# Server_CPU_DDR4.net
KiCad netlist of a schematic drawn in Altium Designer
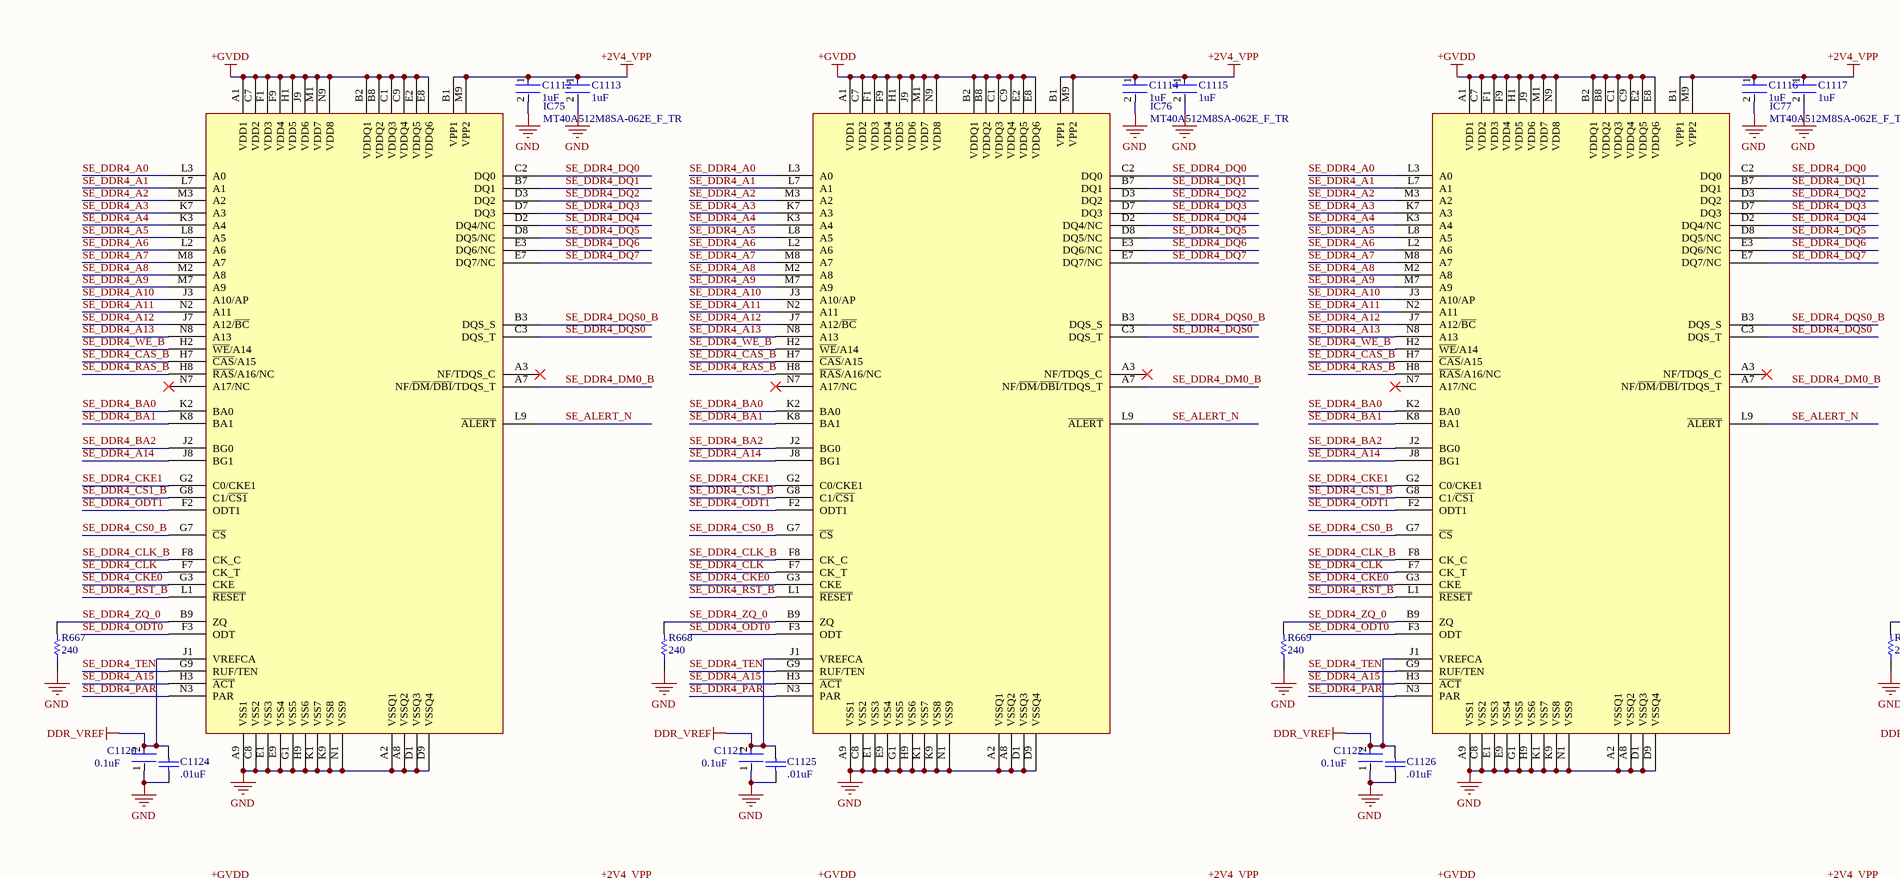
[diagram p0: Server_CPU_DDR4.SchDoc, top left]
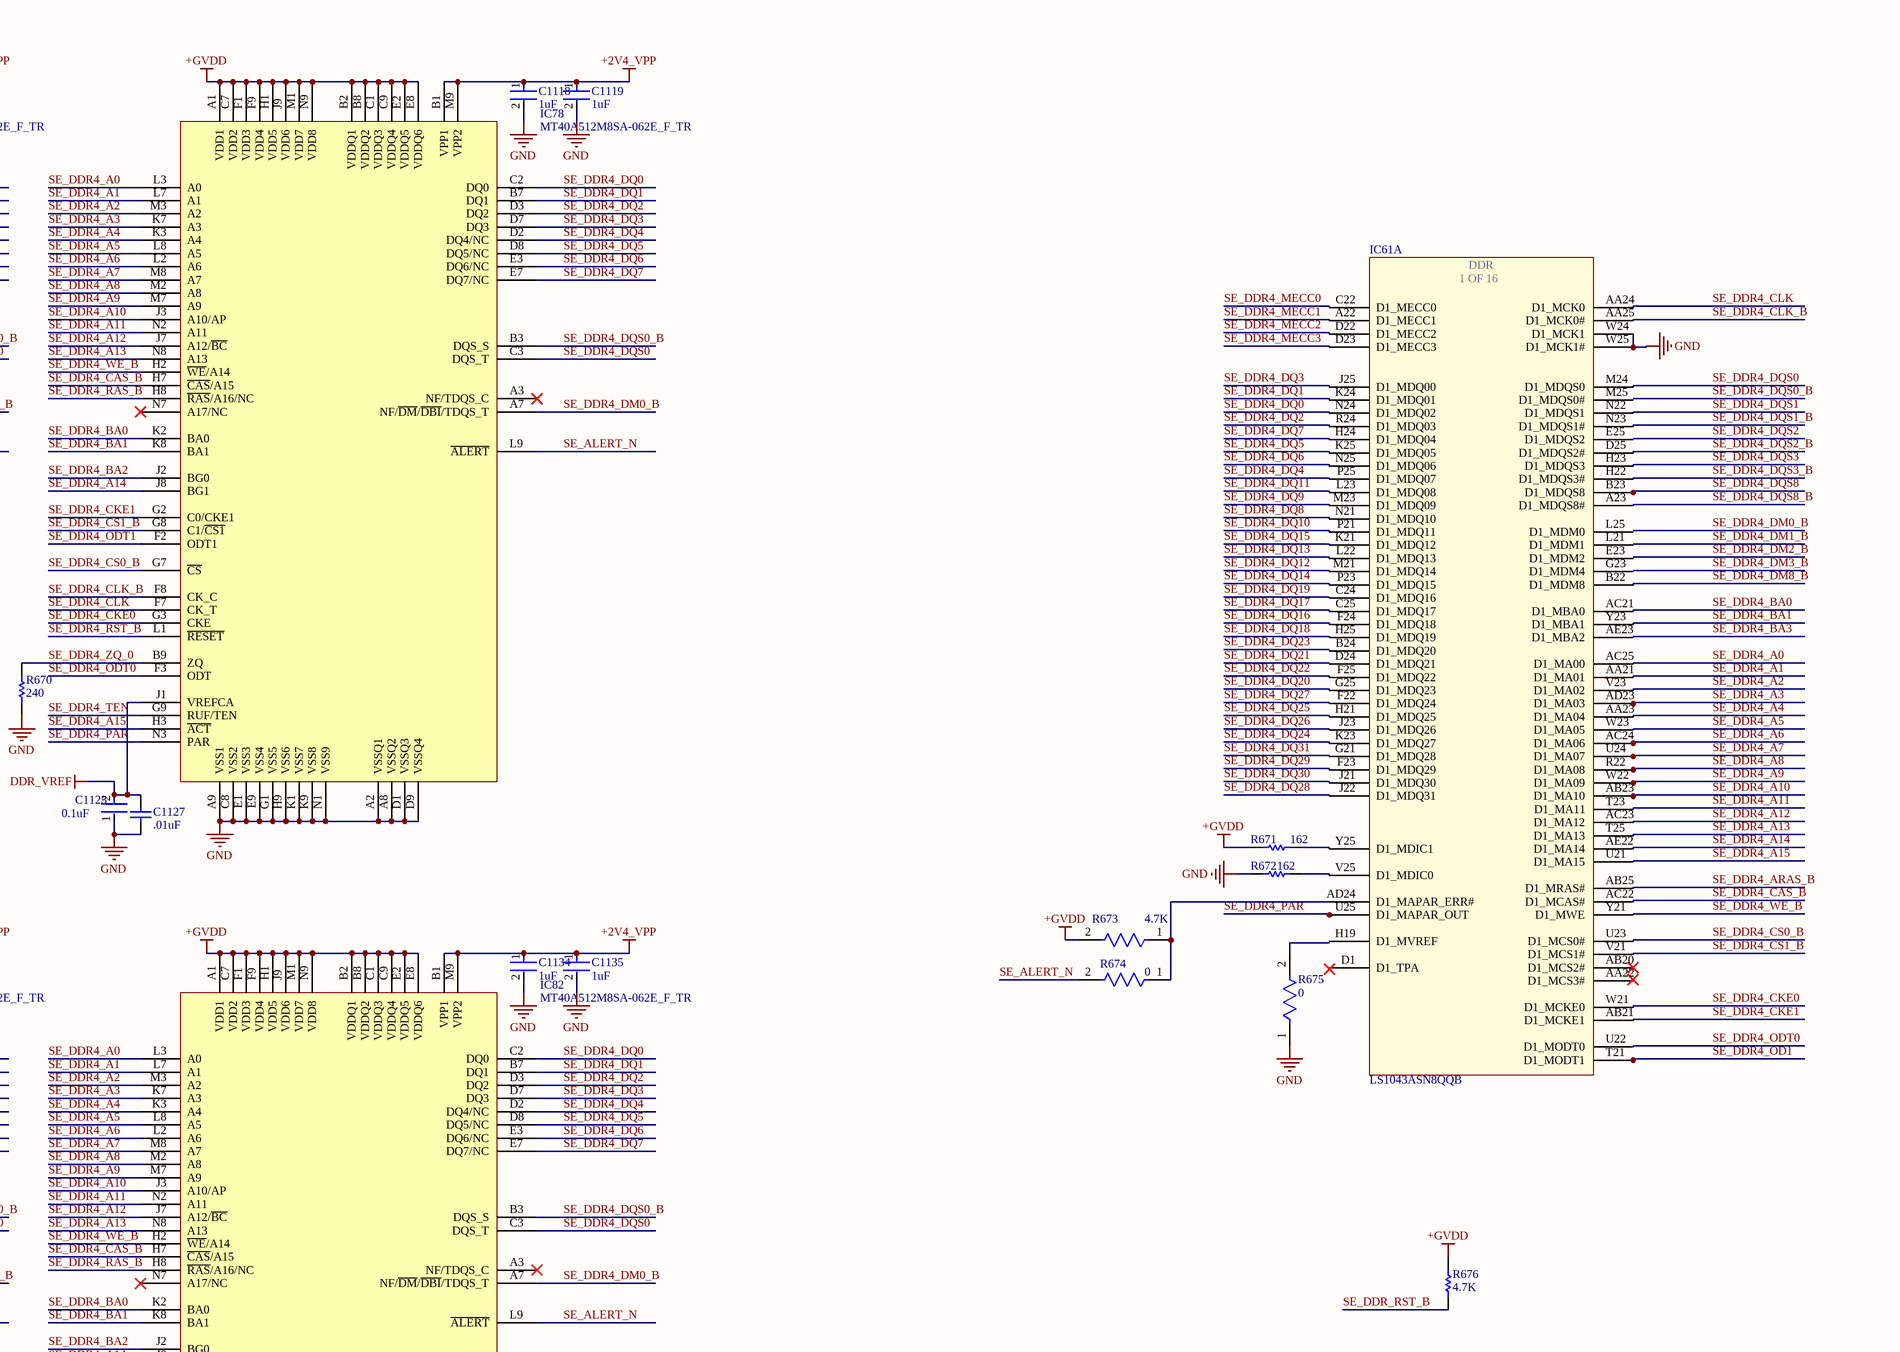
[diagram p1: Server_CPU_DDR4.SchDoc, top right]
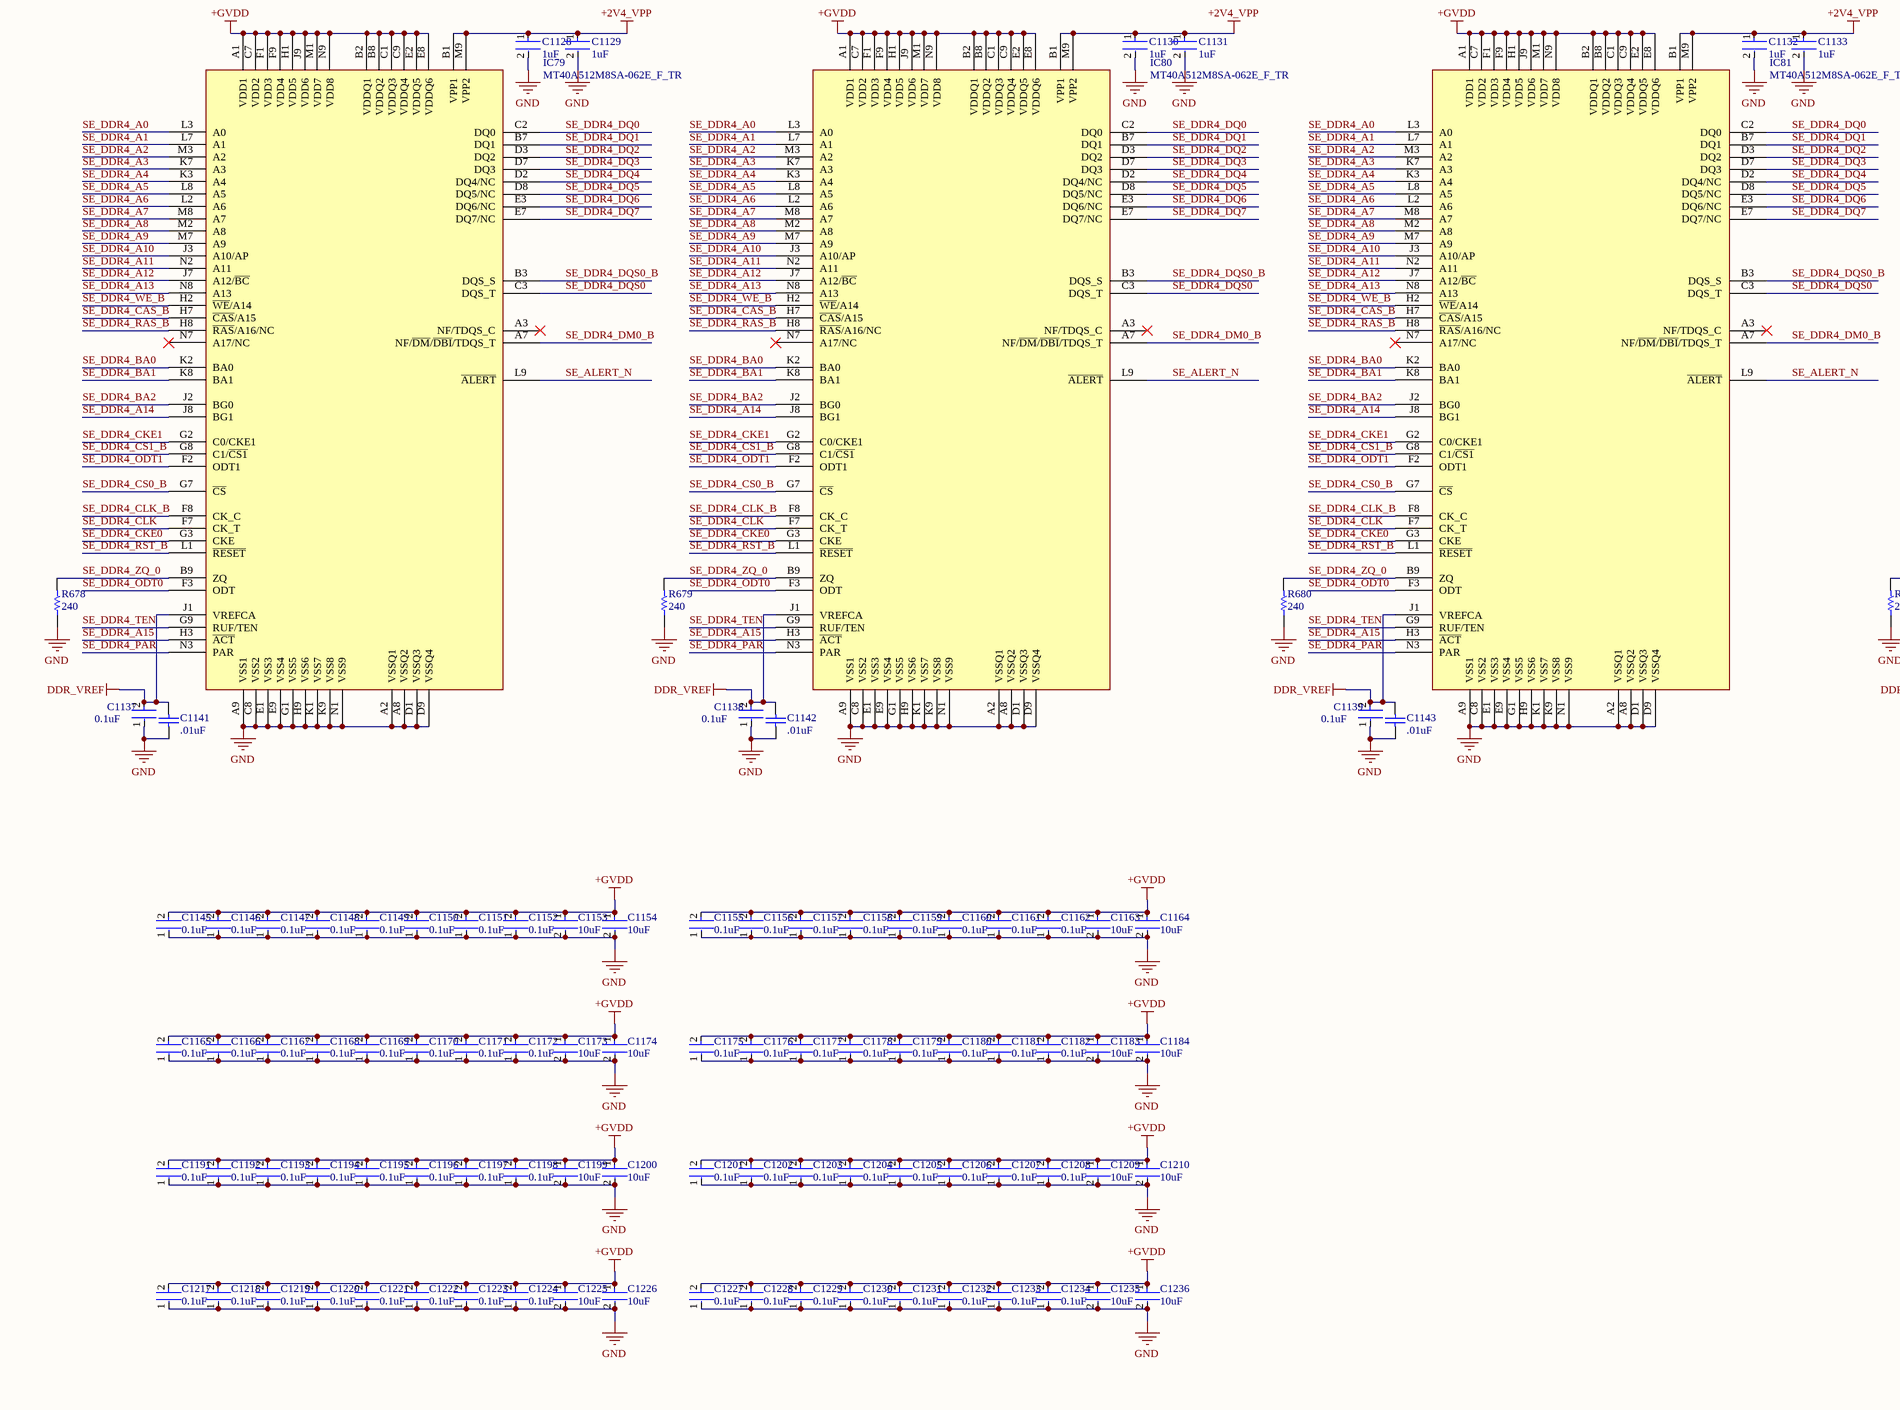
[diagram p2: Server_CPU_DDR4.SchDoc, bottom left]
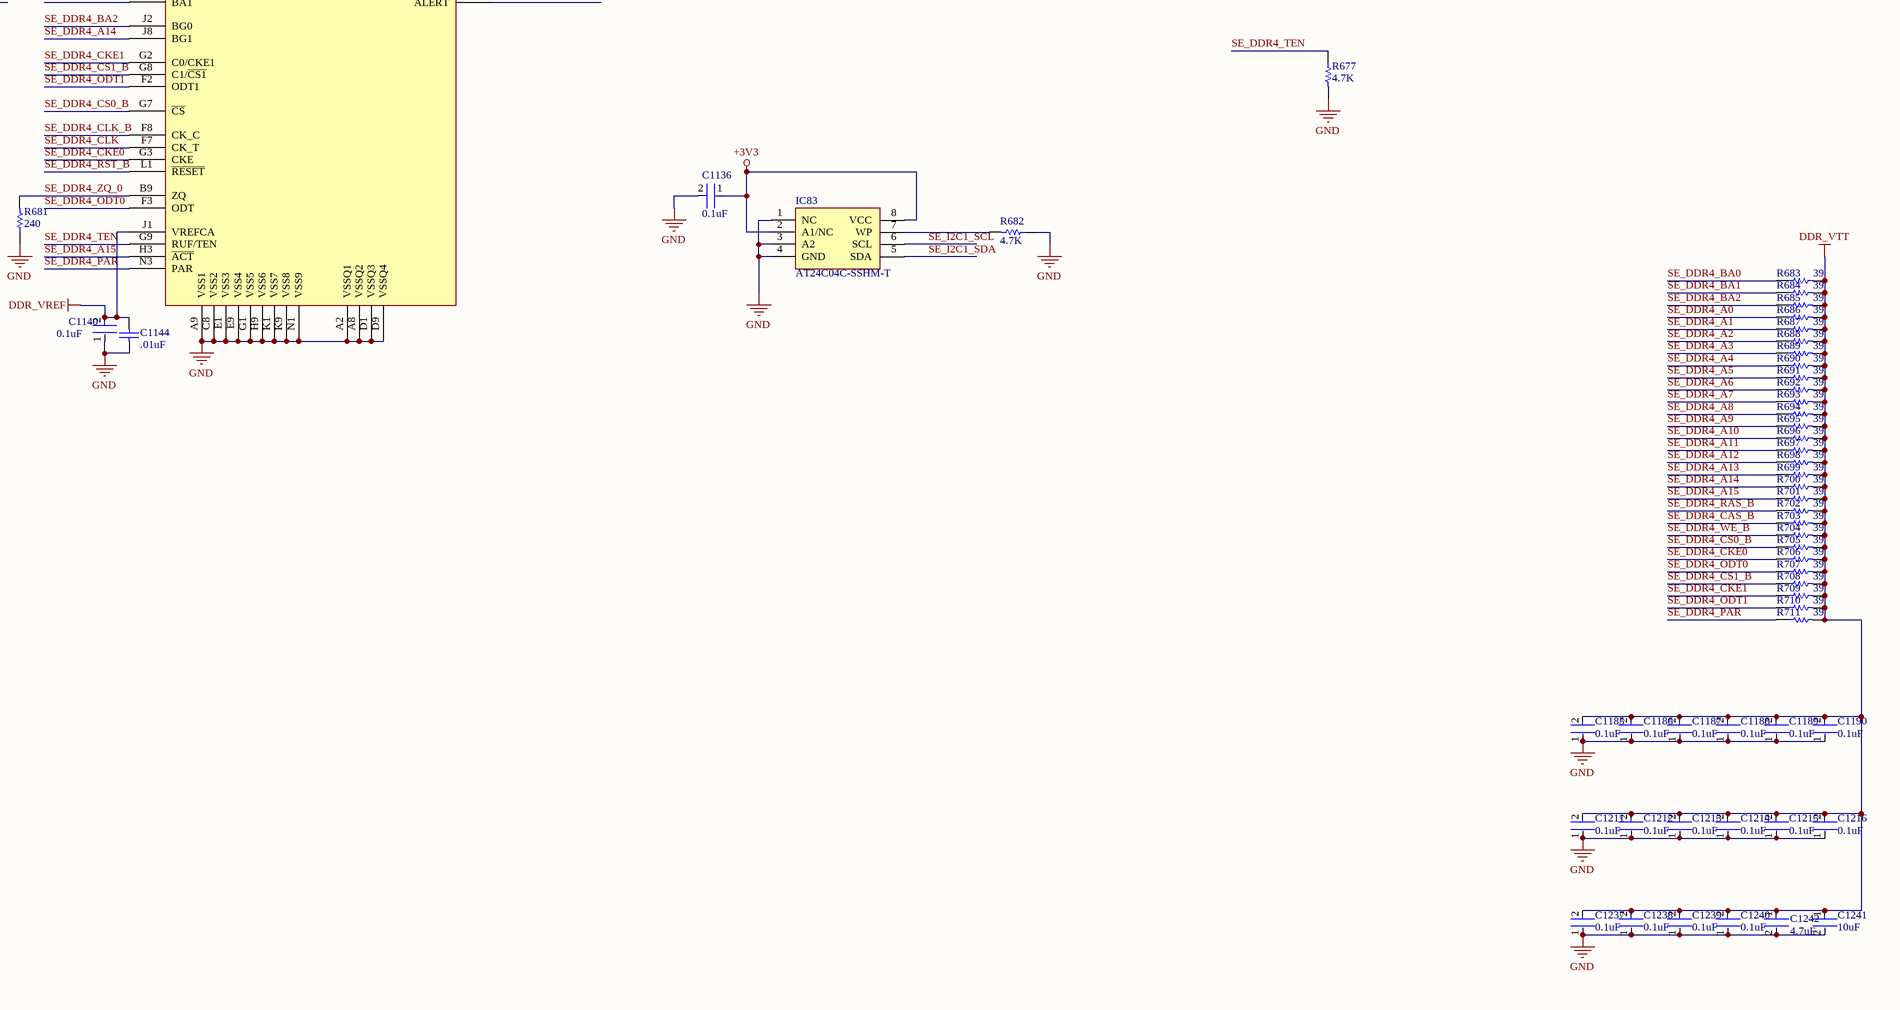
[diagram p3: Server_CPU_DDR4.SchDoc, bottom right]

(export (version "E")
  (design (tool "Eeschema 10.0.6"))
  (components
    (comp (ref "C1112")
      (value "1uF")
      (footprint "FP-GRM15-0_1-MFG")
      (description "CAP CER 1UF 10V X5R 0402")
      (fields
        (field (name "OCTOPART") "https://octopart.com/grm155r61a105ke15d-murata-197442")
        (field (name "MANUFACTURER PART NUMBER") "GRM155R61A105KE15D")
      )
      (libsource (lib "Altium Content Vault") (part "02cd4be3c70576c341d710602a673aa"))
    )
    (comp (ref "C1113")
      (value "1uF")
      (footprint "FP-GRM15-0_1-MFG")
      (description "CAP CER 1UF 10V X5R 0402")
      (fields
        (field (name "OCTOPART") "https://octopart.com/grm155r61a105ke15d-murata-197442")
        (field (name "MANUFACTURER PART NUMBER") "GRM155R61A105KE15D")
      )
      (libsource (lib "Altium Content Vault") (part "02cd4be3c70576c341d710602a673aa"))
    )
    (comp (ref "C1114")
      (value "1uF")
      (footprint "FP-GRM15-0_1-MFG")
      (description "CAP CER 1UF 10V X5R 0402")
      (fields
        (field (name "OCTOPART") "https://octopart.com/grm155r61a105ke15d-murata-197442")
        (field (name "MANUFACTURER PART NUMBER") "GRM155R61A105KE15D")
      )
      (libsource (lib "Altium Content Vault") (part "02cd4be3c70576c341d710602a673aa"))
    )
    (comp (ref "C1115")
      (value "1uF")
      (footprint "FP-GRM15-0_1-MFG")
      (description "CAP CER 1UF 10V X5R 0402")
      (fields
        (field (name "OCTOPART") "https://octopart.com/grm155r61a105ke15d-murata-197442")
        (field (name "MANUFACTURER PART NUMBER") "GRM155R61A105KE15D")
      )
      (libsource (lib "Altium Content Vault") (part "02cd4be3c70576c341d710602a673aa"))
    )
    (comp (ref "C1116")
      (value "1uF")
      (footprint "FP-GRM15-0_1-MFG")
      (description "CAP CER 1UF 10V X5R 0402")
      (fields
        (field (name "OCTOPART") "https://octopart.com/grm155r61a105ke15d-murata-197442")
        (field (name "MANUFACTURER PART NUMBER") "GRM155R61A105KE15D")
      )
      (libsource (lib "Altium Content Vault") (part "02cd4be3c70576c341d710602a673aa"))
    )
    (comp (ref "C1117")
      (value "1uF")
      (footprint "FP-GRM15-0_1-MFG")
      (description "CAP CER 1UF 10V X5R 0402")
      (fields
        (field (name "OCTOPART") "https://octopart.com/grm155r61a105ke15d-murata-197442")
        (field (name "MANUFACTURER PART NUMBER") "GRM155R61A105KE15D")
      )
      (libsource (lib "Altium Content Vault") (part "02cd4be3c70576c341d710602a673aa"))
    )
    (comp (ref "C1118")
      (value "1uF")
      (footprint "FP-GRM15-0_1-MFG")
      (description "CAP CER 1UF 10V X5R 0402")
      (fields
        (field (name "OCTOPART") "https://octopart.com/grm155r61a105ke15d-murata-197442")
        (field (name "MANUFACTURER PART NUMBER") "GRM155R61A105KE15D")
      )
      (libsource (lib "Altium Content Vault") (part "02cd4be3c70576c341d710602a673aa"))
    )
    (comp (ref "C1119")
      (value "1uF")
      (footprint "FP-GRM15-0_1-MFG")
      (description "CAP CER 1UF 10V X5R 0402")
      (fields
        (field (name "OCTOPART") "https://octopart.com/grm155r61a105ke15d-murata-197442")
        (field (name "MANUFACTURER PART NUMBER") "GRM155R61A105KE15D")
      )
      (libsource (lib "Altium Content Vault") (part "02cd4be3c70576c341d710602a673aa"))
    )
    (comp (ref "C1120")
      (value "0.1uF")
      (footprint "FP-GRM15-MFG")
      (description "CAP CER 0.1UF 16V X7R 0402")
      (fields (field (name "MANUFACTURER PART NUMBER") "GRM155R71C104KA88D") (field (name "TOLERANCE") "10%"))
      (libsource (lib "Altium Content Vault") (part "236180d848d6139a670b325ea6854c9"))
    )
    (comp (ref "C1121")
      (value "0.1uF")
      (footprint "FP-GRM15-MFG")
      (description "CAP CER 0.1UF 16V X7R 0402")
      (fields (field (name "MANUFACTURER PART NUMBER") "GRM155R71C104KA88D") (field (name "TOLERANCE") "10%"))
      (libsource (lib "Altium Content Vault") (part "236180d848d6139a670b325ea6854c9"))
    )
    (comp (ref "C1122")
      (value "0.1uF")
      (footprint "FP-GRM15-MFG")
      (description "CAP CER 0.1UF 16V X7R 0402")
      (fields (field (name "MANUFACTURER PART NUMBER") "GRM155R71C104KA88D") (field (name "TOLERANCE") "10%"))
      (libsource (lib "Altium Content Vault") (part "236180d848d6139a670b325ea6854c9"))
    )
    (comp (ref "C1123")
      (value "0.1uF")
      (footprint "FP-GRM15-MFG")
      (description "CAP CER 0.1UF 16V X7R 0402")
      (fields (field (name "MANUFACTURER PART NUMBER") "GRM155R71C104KA88D") (field (name "TOLERANCE") "10%"))
      (libsource (lib "Altium Content Vault") (part "236180d848d6139a670b325ea6854c9"))
    )
    (comp (ref "C1124")
      (value ".01uF")
      (footprint "CAPC1005X56X25LL10T15")
      (fields
        (field (name "MANUFACTURER") "AVX Interconnect / Elco")
        (field (name "PART NUMBER") "0402YC103JAT2A")
      )
      (libsource (lib "Altium Content Vault") (part "CAP"))
    )
    (comp (ref "C1125")
      (value ".01uF")
      (footprint "CAPC1005X56X25LL10T15")
      (fields
        (field (name "MANUFACTURER") "AVX Interconnect / Elco")
        (field (name "PART NUMBER") "0402YC103JAT2A")
      )
      (libsource (lib "Altium Content Vault") (part "CAP"))
    )
    (comp (ref "C1126")
      (value ".01uF")
      (footprint "CAPC1005X56X25LL10T15")
      (fields
        (field (name "MANUFACTURER") "AVX Interconnect / Elco")
        (field (name "PART NUMBER") "0402YC103JAT2A")
      )
      (libsource (lib "Altium Content Vault") (part "CAP"))
    )
    (comp (ref "C1127")
      (value ".01uF")
      (footprint "CAPC1005X56X25LL10T15")
      (fields
        (field (name "MANUFACTURER") "AVX Interconnect / Elco")
        (field (name "PART NUMBER") "0402YC103JAT2A")
      )
      (libsource (lib "Altium Content Vault") (part "CAP"))
    )
    (comp (ref "C1128")
      (value "1uF")
      (footprint "FP-GRM15-0_1-MFG")
      (description "CAP CER 1UF 10V X5R 0402")
      (fields
        (field (name "OCTOPART") "https://octopart.com/grm155r61a105ke15d-murata-197442")
        (field (name "MANUFACTURER PART NUMBER") "GRM155R61A105KE15D")
      )
      (libsource (lib "Altium Content Vault") (part "02cd4be3c70576c341d710602a673aa"))
    )
    (comp (ref "C1129")
      (value "1uF")
      (footprint "FP-GRM15-0_1-MFG")
      (description "CAP CER 1UF 10V X5R 0402")
      (fields
        (field (name "OCTOPART") "https://octopart.com/grm155r61a105ke15d-murata-197442")
        (field (name "MANUFACTURER PART NUMBER") "GRM155R61A105KE15D")
      )
      (libsource (lib "Altium Content Vault") (part "02cd4be3c70576c341d710602a673aa"))
    )
    (comp (ref "C1130")
      (value "1uF")
      (footprint "FP-GRM15-0_1-MFG")
      (description "CAP CER 1UF 10V X5R 0402")
      (fields
        (field (name "OCTOPART") "https://octopart.com/grm155r61a105ke15d-murata-197442")
        (field (name "MANUFACTURER PART NUMBER") "GRM155R61A105KE15D")
      )
      (libsource (lib "Altium Content Vault") (part "02cd4be3c70576c341d710602a673aa"))
    )
    (comp (ref "C1131")
      (value "1uF")
      (footprint "FP-GRM15-0_1-MFG")
      (description "CAP CER 1UF 10V X5R 0402")
      (fields
        (field (name "OCTOPART") "https://octopart.com/grm155r61a105ke15d-murata-197442")
        (field (name "MANUFACTURER PART NUMBER") "GRM155R61A105KE15D")
      )
      (libsource (lib "Altium Content Vault") (part "02cd4be3c70576c341d710602a673aa"))
    )
    (comp (ref "C1132")
      (value "1uF")
      (footprint "FP-GRM15-0_1-MFG")
      (description "CAP CER 1UF 10V X5R 0402")
      (fields
        (field (name "OCTOPART") "https://octopart.com/grm155r61a105ke15d-murata-197442")
        (field (name "MANUFACTURER PART NUMBER") "GRM155R61A105KE15D")
      )
      (libsource (lib "Altium Content Vault") (part "02cd4be3c70576c341d710602a673aa"))
    )
    (comp (ref "C1133")
      (value "1uF")
      (footprint "FP-GRM15-0_1-MFG")
      (description "CAP CER 1UF 10V X5R 0402")
      (fields
        (field (name "OCTOPART") "https://octopart.com/grm155r61a105ke15d-murata-197442")
        (field (name "MANUFACTURER PART NUMBER") "GRM155R61A105KE15D")
      )
      (libsource (lib "Altium Content Vault") (part "02cd4be3c70576c341d710602a673aa"))
    )
    (comp (ref "C1134")
      (value "1uF")
      (footprint "FP-GRM15-0_1-MFG")
      (description "CAP CER 1UF 10V X5R 0402")
      (fields
        (field (name "OCTOPART") "https://octopart.com/grm155r61a105ke15d-murata-197442")
        (field (name "MANUFACTURER PART NUMBER") "GRM155R61A105KE15D")
      )
      (libsource (lib "Altium Content Vault") (part "02cd4be3c70576c341d710602a673aa"))
    )
    (comp (ref "C1135")
      (value "1uF")
      (footprint "FP-GRM15-0_1-MFG")
      (description "CAP CER 1UF 10V X5R 0402")
      (fields
        (field (name "OCTOPART") "https://octopart.com/grm155r61a105ke15d-murata-197442")
        (field (name "MANUFACTURER PART NUMBER") "GRM155R61A105KE15D")
      )
      (libsource (lib "Altium Content Vault") (part "02cd4be3c70576c341d710602a673aa"))
    )
    (comp (ref "C1136")
      (value "0.1uF")
      (footprint "FP-GRM15-MFG")
      (description "CAP CER 0.1UF 16V X7R 0402")
      (fields (field (name "MANUFACTURER PART NUMBER") "GRM155R71C104KA88D") (field (name "TOLERANCE") "10%"))
      (libsource (lib "Altium Content Vault") (part "236180d848d6139a670b325ea6854c9"))
    )
    (comp (ref "C1137")
      (value "0.1uF")
      (footprint "FP-GRM15-MFG")
      (description "CAP CER 0.1UF 16V X7R 0402")
      (fields (field (name "MANUFACTURER PART NUMBER") "GRM155R71C104KA88D") (field (name "TOLERANCE") "10%"))
      (libsource (lib "Altium Content Vault") (part "236180d848d6139a670b325ea6854c9"))
    )
    (comp (ref "C1138")
      (value "0.1uF")
      (footprint "FP-GRM15-MFG")
      (description "CAP CER 0.1UF 16V X7R 0402")
      (fields (field (name "MANUFACTURER PART NUMBER") "GRM155R71C104KA88D") (field (name "TOLERANCE") "10%"))
      (libsource (lib "Altium Content Vault") (part "236180d848d6139a670b325ea6854c9"))
    )
    (comp (ref "C1139")
      (value "0.1uF")
      (footprint "FP-GRM15-MFG")
      (description "CAP CER 0.1UF 16V X7R 0402")
      (fields (field (name "MANUFACTURER PART NUMBER") "GRM155R71C104KA88D") (field (name "TOLERANCE") "10%"))
      (libsource (lib "Altium Content Vault") (part "236180d848d6139a670b325ea6854c9"))
    )
    (comp (ref "C1140")
      (value "0.1uF")
      (footprint "FP-GRM15-MFG")
      (description "CAP CER 0.1UF 16V X7R 0402")
      (fields (field (name "MANUFACTURER PART NUMBER") "GRM155R71C104KA88D") (field (name "TOLERANCE") "10%"))
      (libsource (lib "Altium Content Vault") (part "236180d848d6139a670b325ea6854c9"))
    )
    (comp (ref "C1141")
      (value ".01uF")
      (footprint "CAPC1005X56X25LL10T15")
      (fields
        (field (name "MANUFACTURER") "AVX Interconnect / Elco")
        (field (name "PART NUMBER") "0402YC103JAT2A")
      )
      (libsource (lib "Altium Content Vault") (part "CAP"))
    )
    (comp (ref "C1142")
      (value ".01uF")
      (footprint "CAPC1005X56X25LL10T15")
      (fields
        (field (name "MANUFACTURER") "AVX Interconnect / Elco")
        (field (name "PART NUMBER") "0402YC103JAT2A")
      )
      (libsource (lib "Altium Content Vault") (part "CAP"))
    )
    (comp (ref "C1143")
      (value ".01uF")
      (footprint "CAPC1005X56X25LL10T15")
      (fields
        (field (name "MANUFACTURER") "AVX Interconnect / Elco")
        (field (name "PART NUMBER") "0402YC103JAT2A")
      )
      (libsource (lib "Altium Content Vault") (part "CAP"))
    )
    (comp (ref "C1144")
      (value ".01uF")
      (footprint "CAPC1005X56X25LL10T15")
      (fields
        (field (name "MANUFACTURER") "AVX Interconnect / Elco")
        (field (name "PART NUMBER") "0402YC103JAT2A")
      )
      (libsource (lib "Altium Content Vault") (part "CAP"))
    )
    (comp (ref "C1145")
      (value "0.1uF")
      (footprint "FP-GRM15-MFG")
      (description "CAP CER 0.1UF 16V X7R 0402")
      (fields (field (name "MANUFACTURER PART NUMBER") "GRM155R71C104KA88D") (field (name "TOLERANCE") "10%"))
      (libsource (lib "Altium Content Vault") (part "236180d848d6139a670b325ea6854c9"))
    )
    (comp (ref "C1146")
      (value "0.1uF")
      (footprint "FP-GRM15-MFG")
      (description "CAP CER 0.1UF 16V X7R 0402")
      (fields (field (name "MANUFACTURER PART NUMBER") "GRM155R71C104KA88D") (field (name "TOLERANCE") "10%"))
      (libsource (lib "Altium Content Vault") (part "236180d848d6139a670b325ea6854c9"))
    )
    (comp (ref "C1147")
      (value "0.1uF")
      (footprint "FP-GRM15-MFG")
      (description "CAP CER 0.1UF 16V X7R 0402")
      (fields (field (name "MANUFACTURER PART NUMBER") "GRM155R71C104KA88D") (field (name "TOLERANCE") "10%"))
      (libsource (lib "Altium Content Vault") (part "236180d848d6139a670b325ea6854c9"))
    )
    (comp (ref "C1148")
      (value "0.1uF")
      (footprint "FP-GRM15-MFG")
      (description "CAP CER 0.1UF 16V X7R 0402")
      (fields (field (name "MANUFACTURER PART NUMBER") "GRM155R71C104KA88D") (field (name "TOLERANCE") "10%"))
      (libsource (lib "Altium Content Vault") (part "236180d848d6139a670b325ea6854c9"))
    )
    (comp (ref "C1149")
      (value "0.1uF")
      (footprint "FP-GRM15-MFG")
      (description "CAP CER 0.1UF 16V X7R 0402")
      (fields (field (name "MANUFACTURER PART NUMBER") "GRM155R71C104KA88D") (field (name "TOLERANCE") "10%"))
      (libsource (lib "Altium Content Vault") (part "236180d848d6139a670b325ea6854c9"))
    )
    (comp (ref "C1150")
      (value "0.1uF")
      (footprint "FP-GRM15-MFG")
      (description "CAP CER 0.1UF 16V X7R 0402")
      (fields (field (name "MANUFACTURER PART NUMBER") "GRM155R71C104KA88D") (field (name "TOLERANCE") "10%"))
      (libsource (lib "Altium Content Vault") (part "236180d848d6139a670b325ea6854c9"))
    )
    (comp (ref "C1151")
      (value "0.1uF")
      (footprint "FP-GRM15-MFG")
      (description "CAP CER 0.1UF 16V X7R 0402")
      (fields (field (name "MANUFACTURER PART NUMBER") "GRM155R71C104KA88D") (field (name "TOLERANCE") "10%"))
      (libsource (lib "Altium Content Vault") (part "236180d848d6139a670b325ea6854c9"))
    )
    (comp (ref "C1152")
      (value "0.1uF")
      (footprint "FP-GRM15-MFG")
      (description "CAP CER 0.1UF 16V X7R 0402")
      (fields (field (name "MANUFACTURER PART NUMBER") "GRM155R71C104KA88D") (field (name "TOLERANCE") "10%"))
      (libsource (lib "Altium Content Vault") (part "236180d848d6139a670b325ea6854c9"))
    )
    (comp (ref "C1153")
      (value "10uF")
      (footprint "FP-GRM21B-0_1-IPC_C")
      (description "Chip Multilayer Ceramic Capacitors for General Purpose, 0805, 10uF, X5R, 15%, 10%, 16V")
      (fields (field (name "TOLERANCE") "10%") (field (name "VOLTAGE") "16V"))
      (libsource (lib "Altium Content Vault") (part "b4654b650e69147ec39a6b967a45e02"))
    )
    (comp (ref "C1154")
      (value "10uF")
      (footprint "FP-GRM21B-0_1-IPC_C")
      (description "Chip Multilayer Ceramic Capacitors for General Purpose, 0805, 10uF, X5R, 15%, 10%, 16V")
      (fields (field (name "TOLERANCE") "10%") (field (name "VOLTAGE") "16V"))
      (libsource (lib "Altium Content Vault") (part "b4654b650e69147ec39a6b967a45e02"))
    )
    (comp (ref "C1155")
      (value "0.1uF")
      (footprint "FP-GRM15-MFG")
      (description "CAP CER 0.1UF 16V X7R 0402")
      (fields (field (name "MANUFACTURER PART NUMBER") "GRM155R71C104KA88D") (field (name "TOLERANCE") "10%"))
      (libsource (lib "Altium Content Vault") (part "236180d848d6139a670b325ea6854c9"))
    )
    (comp (ref "C1156")
      (value "0.1uF")
      (footprint "FP-GRM15-MFG")
      (description "CAP CER 0.1UF 16V X7R 0402")
      (fields (field (name "MANUFACTURER PART NUMBER") "GRM155R71C104KA88D") (field (name "TOLERANCE") "10%"))
      (libsource (lib "Altium Content Vault") (part "236180d848d6139a670b325ea6854c9"))
    )
    (comp (ref "C1157")
      (value "0.1uF")
      (footprint "FP-GRM15-MFG")
      (description "CAP CER 0.1UF 16V X7R 0402")
      (fields (field (name "MANUFACTURER PART NUMBER") "GRM155R71C104KA88D") (field (name "TOLERANCE") "10%"))
      (libsource (lib "Altium Content Vault") (part "236180d848d6139a670b325ea6854c9"))
    )
    (comp (ref "C1158")
      (value "0.1uF")
      (footprint "FP-GRM15-MFG")
      (description "CAP CER 0.1UF 16V X7R 0402")
      (fields (field (name "MANUFACTURER PART NUMBER") "GRM155R71C104KA88D") (field (name "TOLERANCE") "10%"))
      (libsource (lib "Altium Content Vault") (part "236180d848d6139a670b325ea6854c9"))
    )
    (comp (ref "C1159")
      (value "0.1uF")
      (footprint "FP-GRM15-MFG")
      (description "CAP CER 0.1UF 16V X7R 0402")
      (fields (field (name "MANUFACTURER PART NUMBER") "GRM155R71C104KA88D") (field (name "TOLERANCE") "10%"))
      (libsource (lib "Altium Content Vault") (part "236180d848d6139a670b325ea6854c9"))
    )
    (comp (ref "C1160")
      (value "0.1uF")
      (footprint "FP-GRM15-MFG")
      (description "CAP CER 0.1UF 16V X7R 0402")
      (fields (field (name "MANUFACTURER PART NUMBER") "GRM155R71C104KA88D") (field (name "TOLERANCE") "10%"))
      (libsource (lib "Altium Content Vault") (part "236180d848d6139a670b325ea6854c9"))
    )
    (comp (ref "C1161")
      (value "0.1uF")
      (footprint "FP-GRM15-MFG")
      (description "CAP CER 0.1UF 16V X7R 0402")
      (fields (field (name "MANUFACTURER PART NUMBER") "GRM155R71C104KA88D") (field (name "TOLERANCE") "10%"))
      (libsource (lib "Altium Content Vault") (part "236180d848d6139a670b325ea6854c9"))
    )
    (comp (ref "C1162")
      (value "0.1uF")
      (footprint "FP-GRM15-MFG")
      (description "CAP CER 0.1UF 16V X7R 0402")
      (fields (field (name "MANUFACTURER PART NUMBER") "GRM155R71C104KA88D") (field (name "TOLERANCE") "10%"))
      (libsource (lib "Altium Content Vault") (part "236180d848d6139a670b325ea6854c9"))
    )
    (comp (ref "C1163")
      (value "10uF")
      (footprint "FP-GRM21B-0_1-IPC_C")
      (description "Chip Multilayer Ceramic Capacitors for General Purpose, 0805, 10uF, X5R, 15%, 10%, 16V")
      (fields (field (name "TOLERANCE") "10%") (field (name "VOLTAGE") "16V"))
      (libsource (lib "Altium Content Vault") (part "b4654b650e69147ec39a6b967a45e02"))
    )
    (comp (ref "C1164")
      (value "10uF")
      (footprint "FP-GRM21B-0_1-IPC_C")
      (description "Chip Multilayer Ceramic Capacitors for General Purpose, 0805, 10uF, X5R, 15%, 10%, 16V")
      (fields (field (name "TOLERANCE") "10%") (field (name "VOLTAGE") "16V"))
      (libsource (lib "Altium Content Vault") (part "b4654b650e69147ec39a6b967a45e02"))
    )
    (comp (ref "C1165")
      (value "0.1uF")
      (footprint "FP-GRM15-MFG")
      (description "CAP CER 0.1UF 16V X7R 0402")
      (fields (field (name "MANUFACTURER PART NUMBER") "GRM155R71C104KA88D") (field (name "TOLERANCE") "10%"))
      (libsource (lib "Altium Content Vault") (part "236180d848d6139a670b325ea6854c9"))
    )
    (comp (ref "C1166")
      (value "0.1uF")
      (footprint "FP-GRM15-MFG")
      (description "CAP CER 0.1UF 16V X7R 0402")
      (fields (field (name "MANUFACTURER PART NUMBER") "GRM155R71C104KA88D") (field (name "TOLERANCE") "10%"))
      (libsource (lib "Altium Content Vault") (part "236180d848d6139a670b325ea6854c9"))
    )
    (comp (ref "C1167")
      (value "0.1uF")
      (footprint "FP-GRM15-MFG")
      (description "CAP CER 0.1UF 16V X7R 0402")
      (fields (field (name "MANUFACTURER PART NUMBER") "GRM155R71C104KA88D") (field (name "TOLERANCE") "10%"))
      (libsource (lib "Altium Content Vault") (part "236180d848d6139a670b325ea6854c9"))
    )
    (comp (ref "C1168")
      (value "0.1uF")
      (footprint "FP-GRM15-MFG")
      (description "CAP CER 0.1UF 16V X7R 0402")
      (fields (field (name "MANUFACTURER PART NUMBER") "GRM155R71C104KA88D") (field (name "TOLERANCE") "10%"))
      (libsource (lib "Altium Content Vault") (part "236180d848d6139a670b325ea6854c9"))
    )
    (comp (ref "C1169")
      (value "0.1uF")
      (footprint "FP-GRM15-MFG")
      (description "CAP CER 0.1UF 16V X7R 0402")
      (fields (field (name "MANUFACTURER PART NUMBER") "GRM155R71C104KA88D") (field (name "TOLERANCE") "10%"))
      (libsource (lib "Altium Content Vault") (part "236180d848d6139a670b325ea6854c9"))
    )
    (comp (ref "C1170")
      (value "0.1uF")
      (footprint "FP-GRM15-MFG")
      (description "CAP CER 0.1UF 16V X7R 0402")
      (fields (field (name "MANUFACTURER PART NUMBER") "GRM155R71C104KA88D") (field (name "TOLERANCE") "10%"))
      (libsource (lib "Altium Content Vault") (part "236180d848d6139a670b325ea6854c9"))
    )
    (comp (ref "C1171")
      (value "0.1uF")
      (footprint "FP-GRM15-MFG")
      (description "CAP CER 0.1UF 16V X7R 0402")
      (fields (field (name "MANUFACTURER PART NUMBER") "GRM155R71C104KA88D") (field (name "TOLERANCE") "10%"))
      (libsource (lib "Altium Content Vault") (part "236180d848d6139a670b325ea6854c9"))
    )
    (comp (ref "C1172")
      (value "0.1uF")
      (footprint "FP-GRM15-MFG")
      (description "CAP CER 0.1UF 16V X7R 0402")
      (fields (field (name "MANUFACTURER PART NUMBER") "GRM155R71C104KA88D") (field (name "TOLERANCE") "10%"))
      (libsource (lib "Altium Content Vault") (part "236180d848d6139a670b325ea6854c9"))
    )
    (comp (ref "C1173")
      (value "10uF")
      (footprint "FP-GRM21B-0_1-IPC_C")
      (description "Chip Multilayer Ceramic Capacitors for General Purpose, 0805, 10uF, X5R, 15%, 10%, 16V")
      (fields (field (name "TOLERANCE") "10%") (field (name "VOLTAGE") "16V"))
      (libsource (lib "Altium Content Vault") (part "b4654b650e69147ec39a6b967a45e02"))
    )
    (comp (ref "C1174")
      (value "10uF")
      (footprint "FP-GRM21B-0_1-IPC_C")
      (description "Chip Multilayer Ceramic Capacitors for General Purpose, 0805, 10uF, X5R, 15%, 10%, 16V")
      (fields (field (name "TOLERANCE") "10%") (field (name "VOLTAGE") "16V"))
      (libsource (lib "Altium Content Vault") (part "b4654b650e69147ec39a6b967a45e02"))
    )
    (comp (ref "C1175")
      (value "0.1uF")
      (footprint "FP-GRM15-MFG")
      (description "CAP CER 0.1UF 16V X7R 0402")
      (fields (field (name "MANUFACTURER PART NUMBER") "GRM155R71C104KA88D") (field (name "TOLERANCE") "10%"))
      (libsource (lib "Altium Content Vault") (part "236180d848d6139a670b325ea6854c9"))
    )
    (comp (ref "C1176")
      (value "0.1uF")
      (footprint "FP-GRM15-MFG")
      (description "CAP CER 0.1UF 16V X7R 0402")
      (fields (field (name "MANUFACTURER PART NUMBER") "GRM155R71C104KA88D") (field (name "TOLERANCE") "10%"))
      (libsource (lib "Altium Content Vault") (part "236180d848d6139a670b325ea6854c9"))
    )
    (comp (ref "C1177")
      (value "0.1uF")
      (footprint "FP-GRM15-MFG")
      (description "CAP CER 0.1UF 16V X7R 0402")
      (fields (field (name "MANUFACTURER PART NUMBER") "GRM155R71C104KA88D") (field (name "TOLERANCE") "10%"))
      (libsource (lib "Altium Content Vault") (part "236180d848d6139a670b325ea6854c9"))
    )
    (comp (ref "C1178")
      (value "0.1uF")
      (footprint "FP-GRM15-MFG")
      (description "CAP CER 0.1UF 16V X7R 0402")
      (fields (field (name "MANUFACTURER PART NUMBER") "GRM155R71C104KA88D") (field (name "TOLERANCE") "10%"))
      (libsource (lib "Altium Content Vault") (part "236180d848d6139a670b325ea6854c9"))
    )
    (comp (ref "C1179")
      (value "0.1uF")
      (footprint "FP-GRM15-MFG")
      (description "CAP CER 0.1UF 16V X7R 0402")
      (fields (field (name "MANUFACTURER PART NUMBER") "GRM155R71C104KA88D") (field (name "TOLERANCE") "10%"))
      (libsource (lib "Altium Content Vault") (part "236180d848d6139a670b325ea6854c9"))
    )
    (comp (ref "C1180")
      (value "0.1uF")
      (footprint "FP-GRM15-MFG")
      (description "CAP CER 0.1UF 16V X7R 0402")
      (fields (field (name "MANUFACTURER PART NUMBER") "GRM155R71C104KA88D") (field (name "TOLERANCE") "10%"))
      (libsource (lib "Altium Content Vault") (part "236180d848d6139a670b325ea6854c9"))
    )
    (comp (ref "C1181")
      (value "0.1uF")
      (footprint "FP-GRM15-MFG")
      (description "CAP CER 0.1UF 16V X7R 0402")
      (fields (field (name "MANUFACTURER PART NUMBER") "GRM155R71C104KA88D") (field (name "TOLERANCE") "10%"))
      (libsource (lib "Altium Content Vault") (part "236180d848d6139a670b325ea6854c9"))
    )
    (comp (ref "C1182")
      (value "0.1uF")
      (footprint "FP-GRM15-MFG")
      (description "CAP CER 0.1UF 16V X7R 0402")
      (fields (field (name "MANUFACTURER PART NUMBER") "GRM155R71C104KA88D") (field (name "TOLERANCE") "10%"))
      (libsource (lib "Altium Content Vault") (part "236180d848d6139a670b325ea6854c9"))
    )
    (comp (ref "C1183")
      (value "10uF")
      (footprint "FP-GRM21B-0_1-IPC_C")
      (description "Chip Multilayer Ceramic Capacitors for General Purpose, 0805, 10uF, X5R, 15%, 10%, 16V")
      (fields (field (name "TOLERANCE") "10%") (field (name "VOLTAGE") "16V"))
      (libsource (lib "Altium Content Vault") (part "b4654b650e69147ec39a6b967a45e02"))
    )
    (comp (ref "C1184")
      (value "10uF")
      (footprint "FP-GRM21B-0_1-IPC_C")
      (description "Chip Multilayer Ceramic Capacitors for General Purpose, 0805, 10uF, X5R, 15%, 10%, 16V")
      (fields (field (name "TOLERANCE") "10%") (field (name "VOLTAGE") "16V"))
      (libsource (lib "Altium Content Vault") (part "b4654b650e69147ec39a6b967a45e02"))
    )
    (comp (ref "C1185")
      (value "0.1uF")
      (footprint "FP-GRM15-MFG")
      (description "CAP CER 0.1UF 16V X7R 0402")
      (fields (field (name "MANUFACTURER PART NUMBER") "GRM155R71C104KA88D") (field (name "TOLERANCE") "10%"))
      (libsource (lib "Altium Content Vault") (part "236180d848d6139a670b325ea6854c9"))
    )
    (comp (ref "C1186")
      (value "0.1uF")
      (footprint "FP-GRM15-MFG")
      (description "CAP CER 0.1UF 16V X7R 0402")
      (fields (field (name "MANUFACTURER PART NUMBER") "GRM155R71C104KA88D") (field (name "TOLERANCE") "10%"))
      (libsource (lib "Altium Content Vault") (part "236180d848d6139a670b325ea6854c9"))
    )
    (comp (ref "C1187")
      (value "0.1uF")
      (footprint "FP-GRM15-MFG")
      (description "CAP CER 0.1UF 16V X7R 0402")
      (fields (field (name "MANUFACTURER PART NUMBER") "GRM155R71C104KA88D") (field (name "TOLERANCE") "10%"))
      (libsource (lib "Altium Content Vault") (part "236180d848d6139a670b325ea6854c9"))
    )
    (comp (ref "C1188")
      (value "0.1uF")
      (footprint "FP-GRM15-MFG")
      (description "CAP CER 0.1UF 16V X7R 0402")
      (fields (field (name "MANUFACTURER PART NUMBER") "GRM155R71C104KA88D") (field (name "TOLERANCE") "10%"))
      (libsource (lib "Altium Content Vault") (part "236180d848d6139a670b325ea6854c9"))
    )
    (comp (ref "C1189")
      (value "0.1uF")
      (footprint "FP-GRM15-MFG")
      (description "CAP CER 0.1UF 16V X7R 0402")
      (fields (field (name "MANUFACTURER PART NUMBER") "GRM155R71C104KA88D") (field (name "TOLERANCE") "10%"))
      (libsource (lib "Altium Content Vault") (part "236180d848d6139a670b325ea6854c9"))
    )
    (comp (ref "C1190")
      (value "0.1uF")
      (footprint "FP-GRM15-MFG")
      (description "CAP CER 0.1UF 16V X7R 0402")
      (fields (field (name "MANUFACTURER PART NUMBER") "GRM155R71C104KA88D") (field (name "TOLERANCE") "10%"))
      (libsource (lib "Altium Content Vault") (part "236180d848d6139a670b325ea6854c9"))
    )
    (comp (ref "C1191")
      (value "0.1uF")
      (footprint "FP-GRM15-MFG")
      (description "CAP CER 0.1UF 16V X7R 0402")
      (fields (field (name "MANUFACTURER PART NUMBER") "GRM155R71C104KA88D") (field (name "TOLERANCE") "10%"))
      (libsource (lib "Altium Content Vault") (part "236180d848d6139a670b325ea6854c9"))
    )
    (comp (ref "C1192")
      (value "0.1uF")
      (footprint "FP-GRM15-MFG")
      (description "CAP CER 0.1UF 16V X7R 0402")
      (fields (field (name "MANUFACTURER PART NUMBER") "GRM155R71C104KA88D") (field (name "TOLERANCE") "10%"))
      (libsource (lib "Altium Content Vault") (part "236180d848d6139a670b325ea6854c9"))
    )
    (comp (ref "C1193")
      (value "0.1uF")
      (footprint "FP-GRM15-MFG")
      (description "CAP CER 0.1UF 16V X7R 0402")
      (fields (field (name "MANUFACTURER PART NUMBER") "GRM155R71C104KA88D") (field (name "TOLERANCE") "10%"))
      (libsource (lib "Altium Content Vault") (part "236180d848d6139a670b325ea6854c9"))
    )
    (comp (ref "C1194")
      (value "0.1uF")
      (footprint "FP-GRM15-MFG")
      (description "CAP CER 0.1UF 16V X7R 0402")
      (fields (field (name "MANUFACTURER PART NUMBER") "GRM155R71C104KA88D") (field (name "TOLERANCE") "10%"))
      (libsource (lib "Altium Content Vault") (part "236180d848d6139a670b325ea6854c9"))
    )
    (comp (ref "C1195")
      (value "0.1uF")
      (footprint "FP-GRM15-MFG")
      (description "CAP CER 0.1UF 16V X7R 0402")
      (fields (field (name "MANUFACTURER PART NUMBER") "GRM155R71C104KA88D") (field (name "TOLERANCE") "10%"))
      (libsource (lib "Altium Content Vault") (part "236180d848d6139a670b325ea6854c9"))
    )
    (comp (ref "C1196")
      (value "0.1uF")
      (footprint "FP-GRM15-MFG")
      (description "CAP CER 0.1UF 16V X7R 0402")
      (fields (field (name "MANUFACTURER PART NUMBER") "GRM155R71C104KA88D") (field (name "TOLERANCE") "10%"))
      (libsource (lib "Altium Content Vault") (part "236180d848d6139a670b325ea6854c9"))
    )
    (comp (ref "C1197")
      (value "0.1uF")
      (footprint "FP-GRM15-MFG")
      (description "CAP CER 0.1UF 16V X7R 0402")
      (fields (field (name "MANUFACTURER PART NUMBER") "GRM155R71C104KA88D") (field (name "TOLERANCE") "10%"))
      (libsource (lib "Altium Content Vault") (part "236180d848d6139a670b325ea6854c9"))
    )
    (comp (ref "C1198")
      (value "0.1uF")
      (footprint "FP-GRM15-MFG")
      (description "CAP CER 0.1UF 16V X7R 0402")
      (fields (field (name "MANUFACTURER PART NUMBER") "GRM155R71C104KA88D") (field (name "TOLERANCE") "10%"))
      (libsource (lib "Altium Content Vault") (part "236180d848d6139a670b325ea6854c9"))
    )
    (comp (ref "C1199")
      (value "10uF")
      (footprint "FP-GRM21B-0_1-IPC_C")
      (description "Chip Multilayer Ceramic Capacitors for General Purpose, 0805, 10uF, X5R, 15%, 10%, 16V")
      (fields (field (name "TOLERANCE") "10%") (field (name "VOLTAGE") "16V"))
      (libsource (lib "Altium Content Vault") (part "b4654b650e69147ec39a6b967a45e02"))
    )
    (comp (ref "C1200")
      (value "10uF")
      (footprint "FP-GRM21B-0_1-IPC_C")
      (description "Chip Multilayer Ceramic Capacitors for General Purpose, 0805, 10uF, X5R, 15%, 10%, 16V")
      (fields (field (name "TOLERANCE") "10%") (field (name "VOLTAGE") "16V"))
      (libsource (lib "Altium Content Vault") (part "b4654b650e69147ec39a6b967a45e02"))
    )
    (comp (ref "C1201")
      (value "0.1uF")
      (footprint "FP-GRM15-MFG")
      (description "CAP CER 0.1UF 16V X7R 0402")
      (fields (field (name "MANUFACTURER PART NUMBER") "GRM155R71C104KA88D") (field (name "TOLERANCE") "10%"))
      (libsource (lib "Altium Content Vault") (part "236180d848d6139a670b325ea6854c9"))
    )
    (comp (ref "C1202")
      (value "0.1uF")
      (footprint "FP-GRM15-MFG")
      (description "CAP CER 0.1UF 16V X7R 0402")
      (fields (field (name "MANUFACTURER PART NUMBER") "GRM155R71C104KA88D") (field (name "TOLERANCE") "10%"))
      (libsource (lib "Altium Content Vault") (part "236180d848d6139a670b325ea6854c9"))
    )
    (comp (ref "C1203")
      (value "0.1uF")
      (footprint "FP-GRM15-MFG")
      (description "CAP CER 0.1UF 16V X7R 0402")
      (fields (field (name "MANUFACTURER PART NUMBER") "GRM155R71C104KA88D") (field (name "TOLERANCE") "10%"))
      (libsource (lib "Altium Content Vault") (part "236180d848d6139a670b325ea6854c9"))
    )
    (comp (ref "C1204")
      (value "0.1uF")
      (footprint "FP-GRM15-MFG")
      (description "CAP CER 0.1UF 16V X7R 0402")
      (fields (field (name "MANUFACTURER PART NUMBER") "GRM155R71C104KA88D") (field (name "TOLERANCE") "10%"))
      (libsource (lib "Altium Content Vault") (part "236180d848d6139a670b325ea6854c9"))
    )
    (comp (ref "C1205")
      (value "0.1uF")
      (footprint "FP-GRM15-MFG")
      (description "CAP CER 0.1UF 16V X7R 0402")
      (fields (field (name "MANUFACTURER PART NUMBER") "GRM155R71C104KA88D") (field (name "TOLERANCE") "10%"))
      (libsource (lib "Altium Content Vault") (part "236180d848d6139a670b325ea6854c9"))
    )
    (comp (ref "C1206")
      (value "0.1uF")
      (footprint "FP-GRM15-MFG")
      (description "CAP CER 0.1UF 16V X7R 0402")
      (fields (field (name "MANUFACTURER PART NUMBER") "GRM155R71C104KA88D") (field (name "TOLERANCE") "10%"))
      (libsource (lib "Altium Content Vault") (part "236180d848d6139a670b325ea6854c9"))
    )
    (comp (ref "C1207")
      (value "0.1uF")
      (footprint "FP-GRM15-MFG")
      (description "CAP CER 0.1UF 16V X7R 0402")
      (fields (field (name "MANUFACTURER PART NUMBER") "GRM155R71C104KA88D") (field (name "TOLERANCE") "10%"))
      (libsource (lib "Altium Content Vault") (part "236180d848d6139a670b325ea6854c9"))
    )
    (comp (ref "C1208")
      (value "0.1uF")
      (footprint "FP-GRM15-MFG")
      (description "CAP CER 0.1UF 16V X7R 0402")
      (fields (field (name "MANUFACTURER PART NUMBER") "GRM155R71C104KA88D") (field (name "TOLERANCE") "10%"))
      (libsource (lib "Altium Content Vault") (part "236180d848d6139a670b325ea6854c9"))
    )
    (comp (ref "C1209")
      (value "10uF")
      (footprint "FP-GRM21B-0_1-IPC_C")
      (description "Chip Multilayer Ceramic Capacitors for General Purpose, 0805, 10uF, X5R, 15%, 10%, 16V")
      (fields (field (name "TOLERANCE") "10%") (field (name "VOLTAGE") "16V"))
      (libsource (lib "Altium Content Vault") (part "b4654b650e69147ec39a6b967a45e02"))
    )
    (comp (ref "C1210")
      (value "10uF")
      (footprint "FP-GRM21B-0_1-IPC_C")
      (description "Chip Multilayer Ceramic Capacitors for General Purpose, 0805, 10uF, X5R, 15%, 10%, 16V")
      (fields (field (name "TOLERANCE") "10%") (field (name "VOLTAGE") "16V"))
      (libsource (lib "Altium Content Vault") (part "b4654b650e69147ec39a6b967a45e02"))
    )
    (comp (ref "C1211")
      (value "0.1uF")
      (footprint "FP-GRM15-MFG")
      (description "CAP CER 0.1UF 16V X7R 0402")
      (fields (field (name "MANUFACTURER PART NUMBER") "GRM155R71C104KA88D") (field (name "TOLERANCE") "10%"))
      (libsource (lib "Altium Content Vault") (part "236180d848d6139a670b325ea6854c9"))
    )
    (comp (ref "C1212")
      (value "0.1uF")
      (footprint "FP-GRM15-MFG")
      (description "CAP CER 0.1UF 16V X7R 0402")
      (fields (field (name "MANUFACTURER PART NUMBER") "GRM155R71C104KA88D") (field (name "TOLERANCE") "10%"))
      (libsource (lib "Altium Content Vault") (part "236180d848d6139a670b325ea6854c9"))
    )
    (comp (ref "C1213")
      (value "0.1uF")
      (footprint "FP-GRM15-MFG")
      (description "CAP CER 0.1UF 16V X7R 0402")
      (fields (field (name "MANUFACTURER PART NUMBER") "GRM155R71C104KA88D") (field (name "TOLERANCE") "10%"))
      (libsource (lib "Altium Content Vault") (part "236180d848d6139a670b325ea6854c9"))
    )
    (comp (ref "C1214")
      (value "0.1uF")
      (footprint "FP-GRM15-MFG")
      (description "CAP CER 0.1UF 16V X7R 0402")
      (fields (field (name "MANUFACTURER PART NUMBER") "GRM155R71C104KA88D") (field (name "TOLERANCE") "10%"))
      (libsource (lib "Altium Content Vault") (part "236180d848d6139a670b325ea6854c9"))
    )
    (comp (ref "C1215")
      (value "0.1uF")
      (footprint "FP-GRM15-MFG")
      (description "CAP CER 0.1UF 16V X7R 0402")
      (fields (field (name "MANUFACTURER PART NUMBER") "GRM155R71C104KA88D") (field (name "TOLERANCE") "10%"))
      (libsource (lib "Altium Content Vault") (part "236180d848d6139a670b325ea6854c9"))
    )
    (comp (ref "C1216")
      (value "0.1uF")
      (footprint "FP-GRM15-MFG")
      (description "CAP CER 0.1UF 16V X7R 0402")
      (fields (field (name "MANUFACTURER PART NUMBER") "GRM155R71C104KA88D") (field (name "TOLERANCE") "10%"))
      (libsource (lib "Altium Content Vault") (part "236180d848d6139a670b325ea6854c9"))
    )
    (comp (ref "C1217")
      (value "0.1uF")
      (footprint "FP-GRM15-MFG")
      (description "CAP CER 0.1UF 16V X7R 0402")
      (fields (field (name "MANUFACTURER PART NUMBER") "GRM155R71C104KA88D") (field (name "TOLERANCE") "10%"))
      (libsource (lib "Altium Content Vault") (part "236180d848d6139a670b325ea6854c9"))
    )
    (comp (ref "C1218")
      (value "0.1uF")
      (footprint "FP-GRM15-MFG")
      (description "CAP CER 0.1UF 16V X7R 0402")
      (fields (field (name "MANUFACTURER PART NUMBER") "GRM155R71C104KA88D") (field (name "TOLERANCE") "10%"))
      (libsource (lib "Altium Content Vault") (part "236180d848d6139a670b325ea6854c9"))
    )
    (comp (ref "C1219")
      (value "0.1uF")
      (footprint "FP-GRM15-MFG")
      (description "CAP CER 0.1UF 16V X7R 0402")
      (fields (field (name "MANUFACTURER PART NUMBER") "GRM155R71C104KA88D") (field (name "TOLERANCE") "10%"))
      (libsource (lib "Altium Content Vault") (part "236180d848d6139a670b325ea6854c9"))
    )
    (comp (ref "C1220")
      (value "0.1uF")
      (footprint "FP-GRM15-MFG")
      (description "CAP CER 0.1UF 16V X7R 0402")
      (fields (field (name "MANUFACTURER PART NUMBER") "GRM155R71C104KA88D") (field (name "TOLERANCE") "10%"))
      (libsource (lib "Altium Content Vault") (part "236180d848d6139a670b325ea6854c9"))
    )
    (comp (ref "C1221")
      (value "0.1uF")
      (footprint "FP-GRM15-MFG")
      (description "CAP CER 0.1UF 16V X7R 0402")
      (fields (field (name "MANUFACTURER PART NUMBER") "GRM155R71C104KA88D") (field (name "TOLERANCE") "10%"))
      (libsource (lib "Altium Content Vault") (part "236180d848d6139a670b325ea6854c9"))
    )
    (comp (ref "C1222")
      (value "0.1uF")
      (footprint "FP-GRM15-MFG")
      (description "CAP CER 0.1UF 16V X7R 0402")
      (fields (field (name "MANUFACTURER PART NUMBER") "GRM155R71C104KA88D") (field (name "TOLERANCE") "10%"))
      (libsource (lib "Altium Content Vault") (part "236180d848d6139a670b325ea6854c9"))
    )
    (comp (ref "C1223")
      (value "0.1uF")
      (footprint "FP-GRM15-MFG")
      (description "CAP CER 0.1UF 16V X7R 0402")
      (fields (field (name "MANUFACTURER PART NUMBER") "GRM155R71C104KA88D") (field (name "TOLERANCE") "10%"))
      (libsource (lib "Altium Content Vault") (part "236180d848d6139a670b325ea6854c9"))
    )
    (comp (ref "C1224")
      (value "0.1uF")
      (footprint "FP-GRM15-MFG")
      (description "CAP CER 0.1UF 16V X7R 0402")
      (fields (field (name "MANUFACTURER PART NUMBER") "GRM155R71C104KA88D") (field (name "TOLERANCE") "10%"))
      (libsource (lib "Altium Content Vault") (part "236180d848d6139a670b325ea6854c9"))
    )
    (comp (ref "C1225")
      (value "10uF")
      (footprint "FP-GRM21B-0_1-IPC_C")
      (description "Chip Multilayer Ceramic Capacitors for General Purpose, 0805, 10uF, X5R, 15%, 10%, 16V")
      (fields (field (name "TOLERANCE") "10%") (field (name "VOLTAGE") "16V"))
      (libsource (lib "Altium Content Vault") (part "b4654b650e69147ec39a6b967a45e02"))
    )
    (comp (ref "C1226")
      (value "10uF")
      (footprint "FP-GRM21B-0_1-IPC_C")
      (description "Chip Multilayer Ceramic Capacitors for General Purpose, 0805, 10uF, X5R, 15%, 10%, 16V")
      (fields (field (name "TOLERANCE") "10%") (field (name "VOLTAGE") "16V"))
      (libsource (lib "Altium Content Vault") (part "b4654b650e69147ec39a6b967a45e02"))
    )
    (comp (ref "C1227")
      (value "0.1uF")
      (footprint "FP-GRM15-MFG")
      (description "CAP CER 0.1UF 16V X7R 0402")
      (fields (field (name "MANUFACTURER PART NUMBER") "GRM155R71C104KA88D") (field (name "TOLERANCE") "10%"))
      (libsource (lib "Altium Content Vault") (part "236180d848d6139a670b325ea6854c9"))
    )
    (comp (ref "C1228")
      (value "0.1uF")
      (footprint "FP-GRM15-MFG")
      (description "CAP CER 0.1UF 16V X7R 0402")
      (fields (field (name "MANUFACTURER PART NUMBER") "GRM155R71C104KA88D") (field (name "TOLERANCE") "10%"))
      (libsource (lib "Altium Content Vault") (part "236180d848d6139a670b325ea6854c9"))
    )
    (comp (ref "C1229")
      (value "0.1uF")
      (footprint "FP-GRM15-MFG")
      (description "CAP CER 0.1UF 16V X7R 0402")
      (fields (field (name "MANUFACTURER PART NUMBER") "GRM155R71C104KA88D") (field (name "TOLERANCE") "10%"))
      (libsource (lib "Altium Content Vault") (part "236180d848d6139a670b325ea6854c9"))
    )
    (comp (ref "C1230")
      (value "0.1uF")
      (footprint "FP-GRM15-MFG")
      (description "CAP CER 0.1UF 16V X7R 0402")
      (fields (field (name "MANUFACTURER PART NUMBER") "GRM155R71C104KA88D") (field (name "TOLERANCE") "10%"))
      (libsource (lib "Altium Content Vault") (part "236180d848d6139a670b325ea6854c9"))
    )
    (comp (ref "C1231")
      (value "0.1uF")
      (footprint "FP-GRM15-MFG")
      (description "CAP CER 0.1UF 16V X7R 0402")
      (fields (field (name "MANUFACTURER PART NUMBER") "GRM155R71C104KA88D") (field (name "TOLERANCE") "10%"))
      (libsource (lib "Altium Content Vault") (part "236180d848d6139a670b325ea6854c9"))
    )
    (comp (ref "C1232")
      (value "0.1uF")
      (footprint "FP-GRM15-MFG")
      (description "CAP CER 0.1UF 16V X7R 0402")
      (fields (field (name "MANUFACTURER PART NUMBER") "GRM155R71C104KA88D") (field (name "TOLERANCE") "10%"))
      (libsource (lib "Altium Content Vault") (part "236180d848d6139a670b325ea6854c9"))
    )
    (comp (ref "C1233")
      (value "0.1uF")
      (footprint "FP-GRM15-MFG")
      (description "CAP CER 0.1UF 16V X7R 0402")
      (fields (field (name "MANUFACTURER PART NUMBER") "GRM155R71C104KA88D") (field (name "TOLERANCE") "10%"))
      (libsource (lib "Altium Content Vault") (part "236180d848d6139a670b325ea6854c9"))
    )
    (comp (ref "C1234")
      (value "0.1uF")
      (footprint "FP-GRM15-MFG")
      (description "CAP CER 0.1UF 16V X7R 0402")
      (fields (field (name "MANUFACTURER PART NUMBER") "GRM155R71C104KA88D") (field (name "TOLERANCE") "10%"))
      (libsource (lib "Altium Content Vault") (part "236180d848d6139a670b325ea6854c9"))
    )
    (comp (ref "C1235")
      (value "10uF")
      (footprint "FP-GRM21B-0_1-IPC_C")
      (description "Chip Multilayer Ceramic Capacitors for General Purpose, 0805, 10uF, X5R, 15%, 10%, 16V")
      (fields (field (name "TOLERANCE") "10%") (field (name "VOLTAGE") "16V"))
      (libsource (lib "Altium Content Vault") (part "b4654b650e69147ec39a6b967a45e02"))
    )
    (comp (ref "C1236")
      (value "10uF")
      (footprint "FP-GRM21B-0_1-IPC_C")
      (description "Chip Multilayer Ceramic Capacitors for General Purpose, 0805, 10uF, X5R, 15%, 10%, 16V")
      (fields (field (name "TOLERANCE") "10%") (field (name "VOLTAGE") "16V"))
      (libsource (lib "Altium Content Vault") (part "b4654b650e69147ec39a6b967a45e02"))
    )
    (comp (ref "C1237")
      (value "0.1uF")
      (footprint "FP-GRM15-MFG")
      (description "CAP CER 0.1UF 16V X7R 0402")
      (fields (field (name "MANUFACTURER PART NUMBER") "GRM155R71C104KA88D") (field (name "TOLERANCE") "10%"))
      (libsource (lib "Altium Content Vault") (part "236180d848d6139a670b325ea6854c9"))
    )
    (comp (ref "C1238")
      (value "0.1uF")
      (footprint "FP-GRM15-MFG")
      (description "CAP CER 0.1UF 16V X7R 0402")
      (fields (field (name "MANUFACTURER PART NUMBER") "GRM155R71C104KA88D") (field (name "TOLERANCE") "10%"))
      (libsource (lib "Altium Content Vault") (part "236180d848d6139a670b325ea6854c9"))
    )
    (comp (ref "C1239")
      (value "0.1uF")
      (footprint "FP-GRM15-MFG")
      (description "CAP CER 0.1UF 16V X7R 0402")
      (fields (field (name "MANUFACTURER PART NUMBER") "GRM155R71C104KA88D") (field (name "TOLERANCE") "10%"))
      (libsource (lib "Altium Content Vault") (part "236180d848d6139a670b325ea6854c9"))
    )
    (comp (ref "C1240")
      (value "0.1uF")
      (footprint "FP-GRM15-MFG")
      (description "CAP CER 0.1UF 16V X7R 0402")
      (fields (field (name "MANUFACTURER PART NUMBER") "GRM155R71C104KA88D") (field (name "TOLERANCE") "10%"))
      (libsource (lib "Altium Content Vault") (part "236180d848d6139a670b325ea6854c9"))
    )
    (comp (ref "C1241")
      (value "10uF")
      (footprint "FP-GRM21B-0_1-IPC_C")
      (description "Chip Multilayer Ceramic Capacitors for General Purpose, 0805, 10uF, X5R, 15%, 10%, 16V")
      (fields (field (name "TOLERANCE") "10%") (field (name "VOLTAGE") "16V"))
      (libsource (lib "Altium Content Vault") (part "b4654b650e69147ec39a6b967a45e02"))
    )
    (comp (ref "C1242")
      (value "4.7uF")
      (footprint "FP-GRM155-0_1-IPC_B")
      (description "Chip Multilayer Ceramic Capacitors for General Purpose, 0402, 4.7uF, X5R, 15%, 20%, 6.3V")
      (fields (field (name "VOLTAGE") "6.3V") (field (name "TOLERANCE") "20%"))
      (libsource (lib "Altium Content Vault") (part "11868f565c42a9108669ba33697ecf6"))
    )
    (comp (ref "IC61")
      (value "LS1043ASN8QQB")
      (footprint "SamacSys:BGA780C80P28X28_2300X2300X261")
      (description "Integrated Circuit")
      (fields (field (name "MOUSER PART NUMBER") "771-LS1043ASN8QQB"))
      (libsource (lib "SamacSys") (part "LS1043ASN8QQB"))
    )
    (comp (ref "IC75")
      (value "MT40A512M8SA-062E_F_TR")
      (footprint "SamacSys:BGA78C80P9X13_750X1100X120")
      (description "Integrated Circuit")
      (fields
        (field (name "MANUFACTURER_PART_NUMBER") "MT40A512M8SA-062E:F TR")
        (field (name "MOUSER PART NUMBER") "340-402508-REEL")
      )
      (libsource (lib "SamacSys") (part "MT40A512M8SA-062E_F_TR"))
    )
    (comp (ref "IC76")
      (value "MT40A512M8SA-062E_F_TR")
      (footprint "SamacSys:BGA78C80P9X13_750X1100X120")
      (description "Integrated Circuit")
      (fields
        (field (name "MANUFACTURER_PART_NUMBER") "MT40A512M8SA-062E:F TR")
        (field (name "MOUSER PART NUMBER") "340-402508-REEL")
      )
      (libsource (lib "SamacSys") (part "MT40A512M8SA-062E_F_TR"))
    )
    (comp (ref "IC77")
      (value "MT40A512M8SA-062E_F_TR")
      (footprint "SamacSys:BGA78C80P9X13_750X1100X120")
      (description "Integrated Circuit")
      (fields
        (field (name "MANUFACTURER_PART_NUMBER") "MT40A512M8SA-062E:F TR")
        (field (name "MOUSER PART NUMBER") "340-402508-REEL")
      )
      (libsource (lib "SamacSys") (part "MT40A512M8SA-062E_F_TR"))
    )
    (comp (ref "IC78")
      (value "MT40A512M8SA-062E_F_TR")
      (footprint "SamacSys:BGA78C80P9X13_750X1100X120")
      (description "Integrated Circuit")
      (fields
        (field (name "MANUFACTURER_PART_NUMBER") "MT40A512M8SA-062E:F TR")
        (field (name "MOUSER PART NUMBER") "340-402508-REEL")
      )
      (libsource (lib "SamacSys") (part "MT40A512M8SA-062E_F_TR"))
    )
    (comp (ref "IC79")
      (value "MT40A512M8SA-062E_F_TR")
      (footprint "SamacSys:BGA78C80P9X13_750X1100X120")
      (description "Integrated Circuit")
      (fields
        (field (name "MANUFACTURER_PART_NUMBER") "MT40A512M8SA-062E:F TR")
        (field (name "MOUSER PART NUMBER") "340-402508-REEL")
      )
      (libsource (lib "SamacSys") (part "MT40A512M8SA-062E_F_TR"))
    )
    (comp (ref "IC80")
      (value "MT40A512M8SA-062E_F_TR")
      (footprint "SamacSys:BGA78C80P9X13_750X1100X120")
      (description "Integrated Circuit")
      (fields
        (field (name "MANUFACTURER_PART_NUMBER") "MT40A512M8SA-062E:F TR")
        (field (name "MOUSER PART NUMBER") "340-402508-REEL")
      )
      (libsource (lib "SamacSys") (part "MT40A512M8SA-062E_F_TR"))
    )
    (comp (ref "IC81")
      (value "MT40A512M8SA-062E_F_TR")
      (footprint "SamacSys:BGA78C80P9X13_750X1100X120")
      (description "Integrated Circuit")
      (fields
        (field (name "MANUFACTURER_PART_NUMBER") "MT40A512M8SA-062E:F TR")
        (field (name "MOUSER PART NUMBER") "340-402508-REEL")
      )
      (libsource (lib "SamacSys") (part "MT40A512M8SA-062E_F_TR"))
    )
    (comp (ref "IC82")
      (value "MT40A512M8SA-062E_F_TR")
      (footprint "SamacSys:BGA78C80P9X13_750X1100X120")
      (description "Integrated Circuit")
      (fields
        (field (name "MANUFACTURER_PART_NUMBER") "MT40A512M8SA-062E:F TR")
        (field (name "MOUSER PART NUMBER") "340-402508-REEL")
      )
      (libsource (lib "SamacSys") (part "MT40A512M8SA-062E_F_TR"))
    )
    (comp (ref "IC83")
      (value "AT24C04C-SSHM-T")
      (footprint "SamacSys:SOIC127P600X175-8N")
      (description "Integrated Circuit")
      (fields (field (name "MOUSER PART NUMBER") "556-AT24C04C-SSHM-T"))
      (libsource (lib "*") (part "AT24C04C-SSHM-T"))
    )
    (comp (ref "R667")
      (value "240")
      (footprint "RESC1005X40X25ML05T05")
      (fields (field (name "MANUFACTURER") "Vishay Dale") (field (name "PART NUMBER") "CRCW0402240RFKED"))
      (libsource (lib "Altium Content Vault") (part "RES"))
    )
    (comp (ref "R668")
      (value "240")
      (footprint "RESC1005X40X25ML05T05")
      (fields (field (name "MANUFACTURER") "Vishay Dale") (field (name "PART NUMBER") "CRCW0402240RFKED"))
      (libsource (lib "Altium Content Vault") (part "RES"))
    )
    (comp (ref "R669")
      (value "240")
      (footprint "RESC1005X40X25ML05T05")
      (fields (field (name "MANUFACTURER") "Vishay Dale") (field (name "PART NUMBER") "CRCW0402240RFKED"))
      (libsource (lib "Altium Content Vault") (part "RES"))
    )
    (comp (ref "R670")
      (value "240")
      (footprint "RESC1005X40X25ML05T05")
      (fields (field (name "MANUFACTURER") "Vishay Dale") (field (name "PART NUMBER") "CRCW0402240RFKED"))
      (libsource (lib "Altium Content Vault") (part "RES"))
    )
    (comp (ref "R671")
      (value "162")
      (footprint "RESC1005X40X25LL05T05")
      (fields (field (name "PART NUMBER") "CRCW0402162RFKED") (field (name "MANUFACTURER") "Vishay Dale"))
      (libsource (lib "Altium Content Vault") (part "RES"))
    )
    (comp (ref "R672")
      (value "162")
      (footprint "RESC1005X40X25LL05T05")
      (fields (field (name "PART NUMBER") "CRCW0402162RFKED") (field (name "MANUFACTURER") "Vishay Dale"))
      (libsource (lib "Altium Content Vault") (part "RES"))
    )
    (comp (ref "R673")
      (value "4.7K")
      (footprint "FP-CRCW0402-e3-IPC_B")
      (description "RES Thick Film, 4.7kΩ, 1%, 0.063W, 100ppm/°C, 0402")
      (fields (field (name "TOLERANCE") "1%"))
      (libsource (lib "Altium Content Vault") (part "1029c3af85768c4190bb7ad29bc67b5"))
    )
    (comp (ref "R674")
      (value "0")
      (footprint "FP-CRCW0402-e3-IPC_C")
      (description "RES Thick Film, 0Ω, 0.063W, 0402")
      (fields (field (name "TOLERANCE") "5%"))
      (libsource (lib "Altium Content Vault") (part "1029c3af85768c4190bb7ad29bc67b5"))
    )
    (comp (ref "R675")
      (value "0")
      (footprint "FP-CRCW0402-e3-IPC_C")
      (description "RES Thick Film, 0Ω, 0.063W, 0402")
      (fields (field (name "TOLERANCE") "5%"))
      (libsource (lib "Altium Content Vault") (part "1029c3af85768c4190bb7ad29bc67b5"))
    )
    (comp (ref "R676")
      (value "4.7K")
      (footprint "RESC1005X40X25LL05T05")
      (description "Chip Resistor, 4.7 KOhm, +/- 1%, 0.1 W, -55 to 155 degC, 0402 (1005 Metric), RoHS, Tape and Reel")
      (fields (field (name "TOLERANCE") "1%") (field (name "PARTNUMBER") "ERJ-2RKF4701X"))
      (libsource (lib "Altium Content Vault") (part "RES-2"))
    )
    (comp (ref "R677")
      (value "4.7K")
      (footprint "RESC1005X40X25LL05T05")
      (description "Chip Resistor, 4.7 KOhm, +/- 1%, 0.1 W, -55 to 155 degC, 0402 (1005 Metric), RoHS, Tape and Reel")
      (fields (field (name "TOLERANCE") "1%") (field (name "PARTNUMBER") "ERJ-2RKF4701X"))
      (libsource (lib "Altium Content Vault") (part "RES-2"))
    )
    (comp (ref "R678")
      (value "240")
      (footprint "RESC1005X40X25ML05T05")
      (fields (field (name "MANUFACTURER") "Vishay Dale") (field (name "PART NUMBER") "CRCW0402240RFKED"))
      (libsource (lib "Altium Content Vault") (part "RES"))
    )
    (comp (ref "R679")
      (value "240")
      (footprint "RESC1005X40X25ML05T05")
      (fields (field (name "MANUFACTURER") "Vishay Dale") (field (name "PART NUMBER") "CRCW0402240RFKED"))
      (libsource (lib "Altium Content Vault") (part "RES"))
    )
    (comp (ref "R680")
      (value "240")
      (footprint "RESC1005X40X25ML05T05")
      (fields (field (name "MANUFACTURER") "Vishay Dale") (field (name "PART NUMBER") "CRCW0402240RFKED"))
      (libsource (lib "Altium Content Vault") (part "RES"))
    )
    (comp (ref "R681")
      (value "240")
      (footprint "RESC1005X40X25ML05T05")
      (fields (field (name "MANUFACTURER") "Vishay Dale") (field (name "PART NUMBER") "CRCW0402240RFKED"))
      (libsource (lib "Altium Content Vault") (part "RES"))
    )
    (comp (ref "R682")
      (value "4.7K")
      (footprint "RESC1005X40X25LL05T05")
      (description "Chip Resistor, 4.7 KOhm, +/- 1%, 0.1 W, -55 to 155 degC, 0402 (1005 Metric), RoHS, Tape and Reel")
      (fields (field (name "TOLERANCE") "1%") (field (name "PARTNUMBER") "ERJ-2RKF4701X"))
      (libsource (lib "Altium Content Vault") (part "RES-2"))
    )
    (comp (ref "R683")
      (value "39")
      (footprint "RESC1005X40X25LL05T05")
      (fields (field (name "PART NUMBER") "ERJ2RKF39R0X") (field (name "MANUFACTURER") "Panasonic"))
      (libsource (lib "Altium Content Vault") (part "RES"))
    )
    (comp (ref "R684")
      (value "39")
      (footprint "RESC1005X40X25LL05T05")
      (fields (field (name "PART NUMBER") "ERJ2RKF39R0X") (field (name "MANUFACTURER") "Panasonic"))
      (libsource (lib "Altium Content Vault") (part "RES"))
    )
    (comp (ref "R685")
      (value "39")
      (footprint "RESC1005X40X25LL05T05")
      (fields (field (name "PART NUMBER") "ERJ2RKF39R0X") (field (name "MANUFACTURER") "Panasonic"))
      (libsource (lib "Altium Content Vault") (part "RES"))
    )
    (comp (ref "R686")
      (value "39")
      (footprint "RESC1005X40X25LL05T05")
      (fields (field (name "PART NUMBER") "ERJ2RKF39R0X") (field (name "MANUFACTURER") "Panasonic"))
      (libsource (lib "Altium Content Vault") (part "RES"))
    )
    (comp (ref "R687")
      (value "39")
      (footprint "RESC1005X40X25LL05T05")
      (fields (field (name "PART NUMBER") "ERJ2RKF39R0X") (field (name "MANUFACTURER") "Panasonic"))
      (libsource (lib "Altium Content Vault") (part "RES"))
    )
    (comp (ref "R688")
      (value "39")
      (footprint "RESC1005X40X25LL05T05")
      (fields (field (name "PART NUMBER") "ERJ2RKF39R0X") (field (name "MANUFACTURER") "Panasonic"))
      (libsource (lib "Altium Content Vault") (part "RES"))
    )
    (comp (ref "R689")
      (value "39")
      (footprint "RESC1005X40X25LL05T05")
      (fields (field (name "PART NUMBER") "ERJ2RKF39R0X") (field (name "MANUFACTURER") "Panasonic"))
      (libsource (lib "Altium Content Vault") (part "RES"))
    )
    (comp (ref "R690")
      (value "39")
      (footprint "RESC1005X40X25LL05T05")
      (fields (field (name "PART NUMBER") "ERJ2RKF39R0X") (field (name "MANUFACTURER") "Panasonic"))
      (libsource (lib "Altium Content Vault") (part "RES"))
    )
    (comp (ref "R691")
      (value "39")
      (footprint "RESC1005X40X25LL05T05")
      (fields (field (name "PART NUMBER") "ERJ2RKF39R0X") (field (name "MANUFACTURER") "Panasonic"))
      (libsource (lib "Altium Content Vault") (part "RES"))
    )
    (comp (ref "R692")
      (value "39")
      (footprint "RESC1005X40X25LL05T05")
      (fields (field (name "PART NUMBER") "ERJ2RKF39R0X") (field (name "MANUFACTURER") "Panasonic"))
      (libsource (lib "Altium Content Vault") (part "RES"))
    )
    (comp (ref "R693")
      (value "39")
      (footprint "RESC1005X40X25LL05T05")
      (fields (field (name "PART NUMBER") "ERJ2RKF39R0X") (field (name "MANUFACTURER") "Panasonic"))
      (libsource (lib "Altium Content Vault") (part "RES"))
    )
    (comp (ref "R694")
      (value "39")
      (footprint "RESC1005X40X25LL05T05")
      (fields (field (name "PART NUMBER") "ERJ2RKF39R0X") (field (name "MANUFACTURER") "Panasonic"))
      (libsource (lib "Altium Content Vault") (part "RES"))
    )
    (comp (ref "R695")
      (value "39")
      (footprint "RESC1005X40X25LL05T05")
      (fields (field (name "PART NUMBER") "ERJ2RKF39R0X") (field (name "MANUFACTURER") "Panasonic"))
      (libsource (lib "Altium Content Vault") (part "RES"))
    )
    (comp (ref "R696")
      (value "39")
      (footprint "RESC1005X40X25LL05T05")
      (fields (field (name "PART NUMBER") "ERJ2RKF39R0X") (field (name "MANUFACTURER") "Panasonic"))
      (libsource (lib "Altium Content Vault") (part "RES"))
    )
    (comp (ref "R697")
      (value "39")
      (footprint "RESC1005X40X25LL05T05")
      (fields (field (name "PART NUMBER") "ERJ2RKF39R0X") (field (name "MANUFACTURER") "Panasonic"))
      (libsource (lib "Altium Content Vault") (part "RES"))
    )
    (comp (ref "R698")
      (value "39")
      (footprint "RESC1005X40X25LL05T05")
      (fields (field (name "PART NUMBER") "ERJ2RKF39R0X") (field (name "MANUFACTURER") "Panasonic"))
      (libsource (lib "Altium Content Vault") (part "RES"))
    )
    (comp (ref "R699")
      (value "39")
      (footprint "RESC1005X40X25LL05T05")
      (fields (field (name "PART NUMBER") "ERJ2RKF39R0X") (field (name "MANUFACTURER") "Panasonic"))
      (libsource (lib "Altium Content Vault") (part "RES"))
    )
    (comp (ref "R700")
      (value "39")
      (footprint "RESC1005X40X25LL05T05")
      (fields (field (name "PART NUMBER") "ERJ2RKF39R0X") (field (name "MANUFACTURER") "Panasonic"))
      (libsource (lib "Altium Content Vault") (part "RES"))
    )
    (comp (ref "R701")
      (value "39")
      (footprint "RESC1005X40X25LL05T05")
      (fields (field (name "PART NUMBER") "ERJ2RKF39R0X") (field (name "MANUFACTURER") "Panasonic"))
      (libsource (lib "Altium Content Vault") (part "RES"))
    )
    (comp (ref "R702")
      (value "39")
      (footprint "RESC1005X40X25LL05T05")
      (fields (field (name "PART NUMBER") "ERJ2RKF39R0X") (field (name "MANUFACTURER") "Panasonic"))
      (libsource (lib "Altium Content Vault") (part "RES"))
    )
    (comp (ref "R703")
      (value "39")
      (footprint "RESC1005X40X25LL05T05")
      (fields (field (name "PART NUMBER") "ERJ2RKF39R0X") (field (name "MANUFACTURER") "Panasonic"))
      (libsource (lib "Altium Content Vault") (part "RES"))
    )
    (comp (ref "R704")
      (value "39")
      (footprint "RESC1005X40X25LL05T05")
      (fields (field (name "PART NUMBER") "ERJ2RKF39R0X") (field (name "MANUFACTURER") "Panasonic"))
      (libsource (lib "Altium Content Vault") (part "RES"))
    )
    (comp (ref "R705")
      (value "39")
      (footprint "RESC1005X40X25LL05T05")
      (fields (field (name "PART NUMBER") "ERJ2RKF39R0X") (field (name "MANUFACTURER") "Panasonic"))
      (libsource (lib "Altium Content Vault") (part "RES"))
    )
    (comp (ref "R706")
      (value "39")
      (footprint "RESC1005X40X25LL05T05")
      (fields (field (name "PART NUMBER") "ERJ2RKF39R0X") (field (name "MANUFACTURER") "Panasonic"))
      (libsource (lib "Altium Content Vault") (part "RES"))
    )
    (comp (ref "R707")
      (value "39")
      (footprint "RESC1005X40X25LL05T05")
      (fields (field (name "PART NUMBER") "ERJ2RKF39R0X") (field (name "MANUFACTURER") "Panasonic"))
      (libsource (lib "Altium Content Vault") (part "RES"))
    )
    (comp (ref "R708")
      (value "39")
      (footprint "RESC1005X40X25LL05T05")
      (fields (field (name "PART NUMBER") "ERJ2RKF39R0X") (field (name "MANUFACTURER") "Panasonic"))
      (libsource (lib "Altium Content Vault") (part "RES"))
    )
    (comp (ref "R709")
      (value "39")
      (footprint "RESC1005X40X25LL05T05")
      (fields (field (name "PART NUMBER") "ERJ2RKF39R0X") (field (name "MANUFACTURER") "Panasonic"))
      (libsource (lib "Altium Content Vault") (part "RES"))
    )
    (comp (ref "R710")
      (value "39")
      (footprint "RESC1005X40X25LL05T05")
      (fields (field (name "PART NUMBER") "ERJ2RKF39R0X") (field (name "MANUFACTURER") "Panasonic"))
      (libsource (lib "Altium Content Vault") (part "RES"))
    )
    (comp (ref "R711")
      (value "39")
      (footprint "RESC1005X40X25LL05T05")
      (fields (field (name "PART NUMBER") "ERJ2RKF39R0X") (field (name "MANUFACTURER") "Panasonic"))
      (libsource (lib "Altium Content Vault") (part "RES"))
    )
  )
  (nets
    (net (code "1") (name "+2V4_VPP") (class "Default")
      (node (ref "C1112") (pin "1") (pinfunction "1_1") (pintype "passive"))
      (node (ref "C1113") (pin "1") (pinfunction "1_1") (pintype "passive"))
      (node (ref "C1114") (pin "1") (pinfunction "1_1") (pintype "passive"))
      (node (ref "C1115") (pin "1") (pinfunction "1_1") (pintype "passive"))
      (node (ref "C1116") (pin "1") (pinfunction "1_1") (pintype "passive"))
      (node (ref "C1117") (pin "1") (pinfunction "1_1") (pintype "passive"))
      (node (ref "C1118") (pin "1") (pinfunction "1_1") (pintype "passive"))
      (node (ref "C1119") (pin "1") (pinfunction "1_1") (pintype "passive"))
      (node (ref "C1128") (pin "1") (pinfunction "1_1") (pintype "passive"))
      (node (ref "C1129") (pin "1") (pinfunction "1_1") (pintype "passive"))
      (node (ref "C1130") (pin "1") (pinfunction "1_1") (pintype "passive"))
      (node (ref "C1131") (pin "1") (pinfunction "1_1") (pintype "passive"))
      (node (ref "C1132") (pin "1") (pinfunction "1_1") (pintype "passive"))
      (node (ref "C1133") (pin "1") (pinfunction "1_1") (pintype "passive"))
      (node (ref "C1134") (pin "1") (pinfunction "1_1") (pintype "passive"))
      (node (ref "C1135") (pin "1") (pinfunction "1_1") (pintype "passive"))
      (node (ref "IC75") (pin "B1") (pinfunction "VPP1_B1") (pintype "passive"))
      (node (ref "IC75") (pin "M9") (pinfunction "VPP2_M9") (pintype "passive"))
      (node (ref "IC76") (pin "B1") (pinfunction "VPP1_B1") (pintype "passive"))
      (node (ref "IC76") (pin "M9") (pinfunction "VPP2_M9") (pintype "passive"))
      (node (ref "IC77") (pin "B1") (pinfunction "VPP1_B1") (pintype "passive"))
      (node (ref "IC77") (pin "M9") (pinfunction "VPP2_M9") (pintype "passive"))
      (node (ref "IC78") (pin "B1") (pinfunction "VPP1_B1") (pintype "passive"))
      (node (ref "IC78") (pin "M9") (pinfunction "VPP2_M9") (pintype "passive"))
      (node (ref "IC79") (pin "B1") (pinfunction "VPP1_B1") (pintype "passive"))
      (node (ref "IC79") (pin "M9") (pinfunction "VPP2_M9") (pintype "passive"))
      (node (ref "IC80") (pin "B1") (pinfunction "VPP1_B1") (pintype "passive"))
      (node (ref "IC80") (pin "M9") (pinfunction "VPP2_M9") (pintype "passive"))
      (node (ref "IC81") (pin "B1") (pinfunction "VPP1_B1") (pintype "passive"))
      (node (ref "IC81") (pin "M9") (pinfunction "VPP2_M9") (pintype "passive"))
      (node (ref "IC82") (pin "B1") (pinfunction "VPP1_B1") (pintype "passive"))
      (node (ref "IC82") (pin "M9") (pinfunction "VPP2_M9") (pintype "passive"))
    )
    (net (code "2") (name "+3V3") (class "Default")
      (node (ref "C1136") (pin "1") (pinfunction "1_1") (pintype "passive"))
      (node (ref "IC83") (pin "2") (pinfunction "A1/NC_2") (pintype "passive"))
      (node (ref "IC83") (pin "8") (pinfunction "VCC_8") (pintype "passive"))
    )
    (net (code "3") (name "+GVDD") (class "Default")
      (node (ref "C1145") (pin "2") (pinfunction "2_2") (pintype "passive"))
      (node (ref "C1146") (pin "2") (pinfunction "2_2") (pintype "passive"))
      (node (ref "C1147") (pin "2") (pinfunction "2_2") (pintype "passive"))
      (node (ref "C1148") (pin "2") (pinfunction "2_2") (pintype "passive"))
      (node (ref "C1149") (pin "2") (pinfunction "2_2") (pintype "passive"))
      (node (ref "C1150") (pin "2") (pinfunction "2_2") (pintype "passive"))
      (node (ref "C1151") (pin "2") (pinfunction "2_2") (pintype "passive"))
      (node (ref "C1152") (pin "2") (pinfunction "2_2") (pintype "passive"))
      (node (ref "C1153") (pin "1") (pinfunction "1_1") (pintype "passive"))
      (node (ref "C1154") (pin "1") (pinfunction "1_1") (pintype "passive"))
      (node (ref "C1155") (pin "2") (pinfunction "2_2") (pintype "passive"))
      (node (ref "C1156") (pin "2") (pinfunction "2_2") (pintype "passive"))
      (node (ref "C1157") (pin "2") (pinfunction "2_2") (pintype "passive"))
      (node (ref "C1158") (pin "2") (pinfunction "2_2") (pintype "passive"))
      (node (ref "C1159") (pin "2") (pinfunction "2_2") (pintype "passive"))
      (node (ref "C1160") (pin "2") (pinfunction "2_2") (pintype "passive"))
      (node (ref "C1161") (pin "2") (pinfunction "2_2") (pintype "passive"))
      (node (ref "C1162") (pin "2") (pinfunction "2_2") (pintype "passive"))
      (node (ref "C1163") (pin "1") (pinfunction "1_1") (pintype "passive"))
      (node (ref "C1164") (pin "1") (pinfunction "1_1") (pintype "passive"))
      (node (ref "C1165") (pin "2") (pinfunction "2_2") (pintype "passive"))
      (node (ref "C1166") (pin "2") (pinfunction "2_2") (pintype "passive"))
      (node (ref "C1167") (pin "2") (pinfunction "2_2") (pintype "passive"))
      (node (ref "C1168") (pin "2") (pinfunction "2_2") (pintype "passive"))
      (node (ref "C1169") (pin "2") (pinfunction "2_2") (pintype "passive"))
      (node (ref "C1170") (pin "2") (pinfunction "2_2") (pintype "passive"))
      (node (ref "C1171") (pin "2") (pinfunction "2_2") (pintype "passive"))
      (node (ref "C1172") (pin "2") (pinfunction "2_2") (pintype "passive"))
      (node (ref "C1173") (pin "1") (pinfunction "1_1") (pintype "passive"))
      (node (ref "C1174") (pin "1") (pinfunction "1_1") (pintype "passive"))
      (node (ref "C1175") (pin "2") (pinfunction "2_2") (pintype "passive"))
      (node (ref "C1176") (pin "2") (pinfunction "2_2") (pintype "passive"))
      (node (ref "C1177") (pin "2") (pinfunction "2_2") (pintype "passive"))
      (node (ref "C1178") (pin "2") (pinfunction "2_2") (pintype "passive"))
      (node (ref "C1179") (pin "2") (pinfunction "2_2") (pintype "passive"))
      (node (ref "C1180") (pin "2") (pinfunction "2_2") (pintype "passive"))
      (node (ref "C1181") (pin "2") (pinfunction "2_2") (pintype "passive"))
      (node (ref "C1182") (pin "2") (pinfunction "2_2") (pintype "passive"))
      (node (ref "C1183") (pin "1") (pinfunction "1_1") (pintype "passive"))
      (node (ref "C1184") (pin "1") (pinfunction "1_1") (pintype "passive"))
      (node (ref "C1191") (pin "2") (pinfunction "2_2") (pintype "passive"))
      (node (ref "C1192") (pin "2") (pinfunction "2_2") (pintype "passive"))
      (node (ref "C1193") (pin "2") (pinfunction "2_2") (pintype "passive"))
      (node (ref "C1194") (pin "2") (pinfunction "2_2") (pintype "passive"))
      (node (ref "C1195") (pin "2") (pinfunction "2_2") (pintype "passive"))
      (node (ref "C1196") (pin "2") (pinfunction "2_2") (pintype "passive"))
      (node (ref "C1197") (pin "2") (pinfunction "2_2") (pintype "passive"))
      (node (ref "C1198") (pin "2") (pinfunction "2_2") (pintype "passive"))
      (node (ref "C1199") (pin "1") (pinfunction "1_1") (pintype "passive"))
      (node (ref "C1200") (pin "1") (pinfunction "1_1") (pintype "passive"))
      (node (ref "C1201") (pin "2") (pinfunction "2_2") (pintype "passive"))
      (node (ref "C1202") (pin "2") (pinfunction "2_2") (pintype "passive"))
      (node (ref "C1203") (pin "2") (pinfunction "2_2") (pintype "passive"))
      (node (ref "C1204") (pin "2") (pinfunction "2_2") (pintype "passive"))
      (node (ref "C1205") (pin "2") (pinfunction "2_2") (pintype "passive"))
      (node (ref "C1206") (pin "2") (pinfunction "2_2") (pintype "passive"))
      (node (ref "C1207") (pin "2") (pinfunction "2_2") (pintype "passive"))
      (node (ref "C1208") (pin "2") (pinfunction "2_2") (pintype "passive"))
      (node (ref "C1209") (pin "1") (pinfunction "1_1") (pintype "passive"))
      (node (ref "C1210") (pin "1") (pinfunction "1_1") (pintype "passive"))
      (node (ref "C1217") (pin "2") (pinfunction "2_2") (pintype "passive"))
      (node (ref "C1218") (pin "2") (pinfunction "2_2") (pintype "passive"))
      (node (ref "C1219") (pin "2") (pinfunction "2_2") (pintype "passive"))
      (node (ref "C1220") (pin "2") (pinfunction "2_2") (pintype "passive"))
      (node (ref "C1221") (pin "2") (pinfunction "2_2") (pintype "passive"))
      (node (ref "C1222") (pin "2") (pinfunction "2_2") (pintype "passive"))
      (node (ref "C1223") (pin "2") (pinfunction "2_2") (pintype "passive"))
      (node (ref "C1224") (pin "2") (pinfunction "2_2") (pintype "passive"))
      (node (ref "C1225") (pin "1") (pinfunction "1_1") (pintype "passive"))
      (node (ref "C1226") (pin "1") (pinfunction "1_1") (pintype "passive"))
      (node (ref "C1227") (pin "2") (pinfunction "2_2") (pintype "passive"))
      (node (ref "C1228") (pin "2") (pinfunction "2_2") (pintype "passive"))
      (node (ref "C1229") (pin "2") (pinfunction "2_2") (pintype "passive"))
      (node (ref "C1230") (pin "2") (pinfunction "2_2") (pintype "passive"))
      (node (ref "C1231") (pin "2") (pinfunction "2_2") (pintype "passive"))
      (node (ref "C1232") (pin "2") (pinfunction "2_2") (pintype "passive"))
      (node (ref "C1233") (pin "2") (pinfunction "2_2") (pintype "passive"))
      (node (ref "C1234") (pin "2") (pinfunction "2_2") (pintype "passive"))
      (node (ref "C1235") (pin "1") (pinfunction "1_1") (pintype "passive"))
      (node (ref "C1236") (pin "1") (pinfunction "1_1") (pintype "passive"))
      (node (ref "IC75") (pin "A1") (pinfunction "VDD1_A1") (pintype "passive"))
      (node (ref "IC75") (pin "B2") (pinfunction "VDDQ1_B2") (pintype "passive"))
      (node (ref "IC75") (pin "B8") (pinfunction "VDDQ2_B8") (pintype "passive"))
      (node (ref "IC75") (pin "C1") (pinfunction "VDDQ3_C1") (pintype "passive"))
      (node (ref "IC75") (pin "C7") (pinfunction "VDD2_C7") (pintype "passive"))
      (node (ref "IC75") (pin "C9") (pinfunction "VDDQ4_C9") (pintype "passive"))
      (node (ref "IC75") (pin "E2") (pinfunction "VDDQ5_E2") (pintype "passive"))
      (node (ref "IC75") (pin "E8") (pinfunction "VDDQ6_E8") (pintype "passive"))
      (node (ref "IC75") (pin "F1") (pinfunction "VDD3_F1") (pintype "passive"))
      (node (ref "IC75") (pin "F9") (pinfunction "VDD4_F9") (pintype "passive"))
      (node (ref "IC75") (pin "H1") (pinfunction "VDD5_H1") (pintype "passive"))
      (node (ref "IC75") (pin "J9") (pinfunction "VDD6_J9") (pintype "passive"))
      (node (ref "IC75") (pin "M1") (pinfunction "VDD7_M1") (pintype "passive"))
      (node (ref "IC75") (pin "N9") (pinfunction "VDD8_N9") (pintype "passive"))
      (node (ref "IC76") (pin "A1") (pinfunction "VDD1_A1") (pintype "passive"))
      (node (ref "IC76") (pin "B2") (pinfunction "VDDQ1_B2") (pintype "passive"))
      (node (ref "IC76") (pin "B8") (pinfunction "VDDQ2_B8") (pintype "passive"))
      (node (ref "IC76") (pin "C1") (pinfunction "VDDQ3_C1") (pintype "passive"))
      (node (ref "IC76") (pin "C7") (pinfunction "VDD2_C7") (pintype "passive"))
      (node (ref "IC76") (pin "C9") (pinfunction "VDDQ4_C9") (pintype "passive"))
      (node (ref "IC76") (pin "E2") (pinfunction "VDDQ5_E2") (pintype "passive"))
      (node (ref "IC76") (pin "E8") (pinfunction "VDDQ6_E8") (pintype "passive"))
      (node (ref "IC76") (pin "F1") (pinfunction "VDD3_F1") (pintype "passive"))
      (node (ref "IC76") (pin "F9") (pinfunction "VDD4_F9") (pintype "passive"))
      (node (ref "IC76") (pin "H1") (pinfunction "VDD5_H1") (pintype "passive"))
      (node (ref "IC76") (pin "J9") (pinfunction "VDD6_J9") (pintype "passive"))
      (node (ref "IC76") (pin "M1") (pinfunction "VDD7_M1") (pintype "passive"))
      (node (ref "IC76") (pin "N9") (pinfunction "VDD8_N9") (pintype "passive"))
      (node (ref "IC77") (pin "A1") (pinfunction "VDD1_A1") (pintype "passive"))
      (node (ref "IC77") (pin "B2") (pinfunction "VDDQ1_B2") (pintype "passive"))
      (node (ref "IC77") (pin "B8") (pinfunction "VDDQ2_B8") (pintype "passive"))
      (node (ref "IC77") (pin "C1") (pinfunction "VDDQ3_C1") (pintype "passive"))
      (node (ref "IC77") (pin "C7") (pinfunction "VDD2_C7") (pintype "passive"))
      (node (ref "IC77") (pin "C9") (pinfunction "VDDQ4_C9") (pintype "passive"))
      (node (ref "IC77") (pin "E2") (pinfunction "VDDQ5_E2") (pintype "passive"))
      (node (ref "IC77") (pin "E8") (pinfunction "VDDQ6_E8") (pintype "passive"))
      (node (ref "IC77") (pin "F1") (pinfunction "VDD3_F1") (pintype "passive"))
      (node (ref "IC77") (pin "F9") (pinfunction "VDD4_F9") (pintype "passive"))
      (node (ref "IC77") (pin "H1") (pinfunction "VDD5_H1") (pintype "passive"))
      (node (ref "IC77") (pin "J9") (pinfunction "VDD6_J9") (pintype "passive"))
      (node (ref "IC77") (pin "M1") (pinfunction "VDD7_M1") (pintype "passive"))
      (node (ref "IC77") (pin "N9") (pinfunction "VDD8_N9") (pintype "passive"))
      (node (ref "IC78") (pin "A1") (pinfunction "VDD1_A1") (pintype "passive"))
      (node (ref "IC78") (pin "B2") (pinfunction "VDDQ1_B2") (pintype "passive"))
      (node (ref "IC78") (pin "B8") (pinfunction "VDDQ2_B8") (pintype "passive"))
      (node (ref "IC78") (pin "C1") (pinfunction "VDDQ3_C1") (pintype "passive"))
      (node (ref "IC78") (pin "C7") (pinfunction "VDD2_C7") (pintype "passive"))
      (node (ref "IC78") (pin "C9") (pinfunction "VDDQ4_C9") (pintype "passive"))
      (node (ref "IC78") (pin "E2") (pinfunction "VDDQ5_E2") (pintype "passive"))
      (node (ref "IC78") (pin "E8") (pinfunction "VDDQ6_E8") (pintype "passive"))
      (node (ref "IC78") (pin "F1") (pinfunction "VDD3_F1") (pintype "passive"))
      (node (ref "IC78") (pin "F9") (pinfunction "VDD4_F9") (pintype "passive"))
      (node (ref "IC78") (pin "H1") (pinfunction "VDD5_H1") (pintype "passive"))
      (node (ref "IC78") (pin "J9") (pinfunction "VDD6_J9") (pintype "passive"))
      (node (ref "IC78") (pin "M1") (pinfunction "VDD7_M1") (pintype "passive"))
      (node (ref "IC78") (pin "N9") (pinfunction "VDD8_N9") (pintype "passive"))
      (node (ref "IC79") (pin "A1") (pinfunction "VDD1_A1") (pintype "passive"))
      (node (ref "IC79") (pin "B2") (pinfunction "VDDQ1_B2") (pintype "passive"))
      (node (ref "IC79") (pin "B8") (pinfunction "VDDQ2_B8") (pintype "passive"))
      (node (ref "IC79") (pin "C1") (pinfunction "VDDQ3_C1") (pintype "passive"))
      (node (ref "IC79") (pin "C7") (pinfunction "VDD2_C7") (pintype "passive"))
      (node (ref "IC79") (pin "C9") (pinfunction "VDDQ4_C9") (pintype "passive"))
      (node (ref "IC79") (pin "E2") (pinfunction "VDDQ5_E2") (pintype "passive"))
      (node (ref "IC79") (pin "E8") (pinfunction "VDDQ6_E8") (pintype "passive"))
      (node (ref "IC79") (pin "F1") (pinfunction "VDD3_F1") (pintype "passive"))
      (node (ref "IC79") (pin "F9") (pinfunction "VDD4_F9") (pintype "passive"))
      (node (ref "IC79") (pin "H1") (pinfunction "VDD5_H1") (pintype "passive"))
      (node (ref "IC79") (pin "J9") (pinfunction "VDD6_J9") (pintype "passive"))
      (node (ref "IC79") (pin "M1") (pinfunction "VDD7_M1") (pintype "passive"))
      (node (ref "IC79") (pin "N9") (pinfunction "VDD8_N9") (pintype "passive"))
      (node (ref "IC80") (pin "A1") (pinfunction "VDD1_A1") (pintype "passive"))
      (node (ref "IC80") (pin "B2") (pinfunction "VDDQ1_B2") (pintype "passive"))
      (node (ref "IC80") (pin "B8") (pinfunction "VDDQ2_B8") (pintype "passive"))
      (node (ref "IC80") (pin "C1") (pinfunction "VDDQ3_C1") (pintype "passive"))
      (node (ref "IC80") (pin "C7") (pinfunction "VDD2_C7") (pintype "passive"))
      (node (ref "IC80") (pin "C9") (pinfunction "VDDQ4_C9") (pintype "passive"))
      (node (ref "IC80") (pin "E2") (pinfunction "VDDQ5_E2") (pintype "passive"))
      (node (ref "IC80") (pin "E8") (pinfunction "VDDQ6_E8") (pintype "passive"))
      (node (ref "IC80") (pin "F1") (pinfunction "VDD3_F1") (pintype "passive"))
      (node (ref "IC80") (pin "F9") (pinfunction "VDD4_F9") (pintype "passive"))
      (node (ref "IC80") (pin "H1") (pinfunction "VDD5_H1") (pintype "passive"))
      (node (ref "IC80") (pin "J9") (pinfunction "VDD6_J9") (pintype "passive"))
      (node (ref "IC80") (pin "M1") (pinfunction "VDD7_M1") (pintype "passive"))
      (node (ref "IC80") (pin "N9") (pinfunction "VDD8_N9") (pintype "passive"))
      (node (ref "IC81") (pin "A1") (pinfunction "VDD1_A1") (pintype "passive"))
      (node (ref "IC81") (pin "B2") (pinfunction "VDDQ1_B2") (pintype "passive"))
      (node (ref "IC81") (pin "B8") (pinfunction "VDDQ2_B8") (pintype "passive"))
      (node (ref "IC81") (pin "C1") (pinfunction "VDDQ3_C1") (pintype "passive"))
      (node (ref "IC81") (pin "C7") (pinfunction "VDD2_C7") (pintype "passive"))
      (node (ref "IC81") (pin "C9") (pinfunction "VDDQ4_C9") (pintype "passive"))
      (node (ref "IC81") (pin "E2") (pinfunction "VDDQ5_E2") (pintype "passive"))
      (node (ref "IC81") (pin "E8") (pinfunction "VDDQ6_E8") (pintype "passive"))
      (node (ref "IC81") (pin "F1") (pinfunction "VDD3_F1") (pintype "passive"))
      (node (ref "IC81") (pin "F9") (pinfunction "VDD4_F9") (pintype "passive"))
      (node (ref "IC81") (pin "H1") (pinfunction "VDD5_H1") (pintype "passive"))
      (node (ref "IC81") (pin "J9") (pinfunction "VDD6_J9") (pintype "passive"))
      (node (ref "IC81") (pin "M1") (pinfunction "VDD7_M1") (pintype "passive"))
      (node (ref "IC81") (pin "N9") (pinfunction "VDD8_N9") (pintype "passive"))
      (node (ref "IC82") (pin "A1") (pinfunction "VDD1_A1") (pintype "passive"))
      (node (ref "IC82") (pin "B2") (pinfunction "VDDQ1_B2") (pintype "passive"))
      (node (ref "IC82") (pin "B8") (pinfunction "VDDQ2_B8") (pintype "passive"))
      (node (ref "IC82") (pin "C1") (pinfunction "VDDQ3_C1") (pintype "passive"))
      (node (ref "IC82") (pin "C7") (pinfunction "VDD2_C7") (pintype "passive"))
      (node (ref "IC82") (pin "C9") (pinfunction "VDDQ4_C9") (pintype "passive"))
      (node (ref "IC82") (pin "E2") (pinfunction "VDDQ5_E2") (pintype "passive"))
      (node (ref "IC82") (pin "E8") (pinfunction "VDDQ6_E8") (pintype "passive"))
      (node (ref "IC82") (pin "F1") (pinfunction "VDD3_F1") (pintype "passive"))
      (node (ref "IC82") (pin "F9") (pinfunction "VDD4_F9") (pintype "passive"))
      (node (ref "IC82") (pin "H1") (pinfunction "VDD5_H1") (pintype "passive"))
      (node (ref "IC82") (pin "J9") (pinfunction "VDD6_J9") (pintype "passive"))
      (node (ref "IC82") (pin "M1") (pinfunction "VDD7_M1") (pintype "passive"))
      (node (ref "IC82") (pin "N9") (pinfunction "VDD8_N9") (pintype "passive"))
      (node (ref "R671") (pin "1") (pinfunction "1_1") (pintype "passive"))
      (node (ref "R673") (pin "2") (pinfunction "2_2") (pintype "passive"))
      (node (ref "R676") (pin "1") (pinfunction "1_1") (pintype "passive"))
    )
    (net (code "4") (name "/SE_ALERT_N") (class "Default")
      (node (ref "IC75") (pin "L9") (pinfunction "~{ALERT}_L9") (pintype "passive"))
      (node (ref "IC76") (pin "L9") (pinfunction "~{ALERT}_L9") (pintype "passive"))
      (node (ref "IC77") (pin "L9") (pinfunction "~{ALERT}_L9") (pintype "passive"))
      (node (ref "IC78") (pin "L9") (pinfunction "~{ALERT}_L9") (pintype "passive"))
      (node (ref "IC79") (pin "L9") (pinfunction "~{ALERT}_L9") (pintype "passive"))
      (node (ref "IC80") (pin "L9") (pinfunction "~{ALERT}_L9") (pintype "passive"))
      (node (ref "IC81") (pin "L9") (pinfunction "~{ALERT}_L9") (pintype "passive"))
      (node (ref "IC82") (pin "L9") (pinfunction "~{ALERT}_L9") (pintype "passive"))
      (node (ref "R674") (pin "2") (pinfunction "2_2") (pintype "passive"))
    )
    (net (code "5") (name "/SE_DDR4_A0") (class "Default")
      (node (ref "IC75") (pin "L3") (pinfunction "A0_L3") (pintype "passive"))
      (node (ref "IC76") (pin "L3") (pinfunction "A0_L3") (pintype "passive"))
      (node (ref "IC77") (pin "L3") (pinfunction "A0_L3") (pintype "passive"))
      (node (ref "IC78") (pin "L3") (pinfunction "A0_L3") (pintype "passive"))
      (node (ref "IC79") (pin "L3") (pinfunction "A0_L3") (pintype "passive"))
      (node (ref "IC80") (pin "L3") (pinfunction "A0_L3") (pintype "passive"))
      (node (ref "IC81") (pin "L3") (pinfunction "A0_L3") (pintype "passive"))
      (node (ref "IC82") (pin "L3") (pinfunction "A0_L3") (pintype "passive"))
      (node (ref "R686") (pin "1") (pinfunction "1_1") (pintype "passive"))
    )
    (net (code "6") (name "/SE_DDR4_A1") (class "Default")
      (node (ref "IC61") (pin "AA21") (pinfunction "D1_MA01_AA21") (pintype "passive"))
      (node (ref "IC75") (pin "L7") (pinfunction "A1_L7") (pintype "passive"))
      (node (ref "IC76") (pin "L7") (pinfunction "A1_L7") (pintype "passive"))
      (node (ref "IC77") (pin "L7") (pinfunction "A1_L7") (pintype "passive"))
      (node (ref "IC78") (pin "L7") (pinfunction "A1_L7") (pintype "passive"))
      (node (ref "IC79") (pin "L7") (pinfunction "A1_L7") (pintype "passive"))
      (node (ref "IC80") (pin "L7") (pinfunction "A1_L7") (pintype "passive"))
      (node (ref "IC81") (pin "L7") (pinfunction "A1_L7") (pintype "passive"))
      (node (ref "IC82") (pin "L7") (pinfunction "A1_L7") (pintype "passive"))
      (node (ref "R687") (pin "1") (pinfunction "1_1") (pintype "passive"))
    )
    (net (code "7") (name "/SE_DDR4_A2") (class "Default")
      (node (ref "IC61") (pin "V23") (pinfunction "D1_MA02_V23") (pintype "passive"))
      (node (ref "IC75") (pin "M3") (pinfunction "A2_M3") (pintype "passive"))
      (node (ref "IC76") (pin "M3") (pinfunction "A2_M3") (pintype "passive"))
      (node (ref "IC77") (pin "M3") (pinfunction "A2_M3") (pintype "passive"))
      (node (ref "IC78") (pin "M3") (pinfunction "A2_M3") (pintype "passive"))
      (node (ref "IC79") (pin "M3") (pinfunction "A2_M3") (pintype "passive"))
      (node (ref "IC80") (pin "M3") (pinfunction "A2_M3") (pintype "passive"))
      (node (ref "IC81") (pin "M3") (pinfunction "A2_M3") (pintype "passive"))
      (node (ref "IC82") (pin "M3") (pinfunction "A2_M3") (pintype "passive"))
      (node (ref "R688") (pin "1") (pinfunction "1_1") (pintype "passive"))
    )
    (net (code "8") (name "/SE_DDR4_A3") (class "Default")
      (node (ref "IC61") (pin "AD23") (pinfunction "D1_MA03_AD23") (pintype "passive"))
      (node (ref "IC75") (pin "K7") (pinfunction "A3_K7") (pintype "passive"))
      (node (ref "IC76") (pin "K7") (pinfunction "A3_K7") (pintype "passive"))
      (node (ref "IC77") (pin "K7") (pinfunction "A3_K7") (pintype "passive"))
      (node (ref "IC78") (pin "K7") (pinfunction "A3_K7") (pintype "passive"))
      (node (ref "IC79") (pin "K7") (pinfunction "A3_K7") (pintype "passive"))
      (node (ref "IC80") (pin "K7") (pinfunction "A3_K7") (pintype "passive"))
      (node (ref "IC81") (pin "K7") (pinfunction "A3_K7") (pintype "passive"))
      (node (ref "IC82") (pin "K7") (pinfunction "A3_K7") (pintype "passive"))
      (node (ref "R689") (pin "1") (pinfunction "1_1") (pintype "passive"))
    )
    (net (code "9") (name "/SE_DDR4_A4") (class "Default")
      (node (ref "IC61") (pin "AA23") (pinfunction "D1_MA04_AA23") (pintype "passive"))
      (node (ref "IC75") (pin "K3") (pinfunction "A4_K3") (pintype "passive"))
      (node (ref "IC76") (pin "K3") (pinfunction "A4_K3") (pintype "passive"))
      (node (ref "IC77") (pin "K3") (pinfunction "A4_K3") (pintype "passive"))
      (node (ref "IC78") (pin "K3") (pinfunction "A4_K3") (pintype "passive"))
      (node (ref "IC79") (pin "K3") (pinfunction "A4_K3") (pintype "passive"))
      (node (ref "IC80") (pin "K3") (pinfunction "A4_K3") (pintype "passive"))
      (node (ref "IC81") (pin "K3") (pinfunction "A4_K3") (pintype "passive"))
      (node (ref "IC82") (pin "K3") (pinfunction "A4_K3") (pintype "passive"))
      (node (ref "R690") (pin "1") (pinfunction "1_1") (pintype "passive"))
    )
    (net (code "10") (name "/SE_DDR4_A5") (class "Default")
      (node (ref "IC61") (pin "W23") (pinfunction "D1_MA05_W23") (pintype "passive"))
      (node (ref "IC75") (pin "L8") (pinfunction "A5_L8") (pintype "passive"))
      (node (ref "IC76") (pin "L8") (pinfunction "A5_L8") (pintype "passive"))
      (node (ref "IC77") (pin "L8") (pinfunction "A5_L8") (pintype "passive"))
      (node (ref "IC78") (pin "L8") (pinfunction "A5_L8") (pintype "passive"))
      (node (ref "IC79") (pin "L8") (pinfunction "A5_L8") (pintype "passive"))
      (node (ref "IC80") (pin "L8") (pinfunction "A5_L8") (pintype "passive"))
      (node (ref "IC81") (pin "L8") (pinfunction "A5_L8") (pintype "passive"))
      (node (ref "IC82") (pin "L8") (pinfunction "A5_L8") (pintype "passive"))
      (node (ref "R691") (pin "1") (pinfunction "1_1") (pintype "passive"))
    )
    (net (code "11") (name "/SE_DDR4_A6") (class "Default")
      (node (ref "IC61") (pin "AC24") (pinfunction "D1_MA06_AC24") (pintype "passive"))
      (node (ref "IC75") (pin "L2") (pinfunction "A6_L2") (pintype "passive"))
      (node (ref "IC76") (pin "L2") (pinfunction "A6_L2") (pintype "passive"))
      (node (ref "IC77") (pin "L2") (pinfunction "A6_L2") (pintype "passive"))
      (node (ref "IC78") (pin "L2") (pinfunction "A6_L2") (pintype "passive"))
      (node (ref "IC79") (pin "L2") (pinfunction "A6_L2") (pintype "passive"))
      (node (ref "IC80") (pin "L2") (pinfunction "A6_L2") (pintype "passive"))
      (node (ref "IC81") (pin "L2") (pinfunction "A6_L2") (pintype "passive"))
      (node (ref "IC82") (pin "L2") (pinfunction "A6_L2") (pintype "passive"))
      (node (ref "R692") (pin "1") (pinfunction "1_1") (pintype "passive"))
    )
    (net (code "12") (name "/SE_DDR4_A7") (class "Default")
      (node (ref "IC61") (pin "U24") (pinfunction "D1_MA07_U24") (pintype "passive"))
      (node (ref "IC75") (pin "M8") (pinfunction "A7_M8") (pintype "passive"))
      (node (ref "IC76") (pin "M8") (pinfunction "A7_M8") (pintype "passive"))
      (node (ref "IC77") (pin "M8") (pinfunction "A7_M8") (pintype "passive"))
      (node (ref "IC78") (pin "M8") (pinfunction "A7_M8") (pintype "passive"))
      (node (ref "IC79") (pin "M8") (pinfunction "A7_M8") (pintype "passive"))
      (node (ref "IC80") (pin "M8") (pinfunction "A7_M8") (pintype "passive"))
      (node (ref "IC81") (pin "M8") (pinfunction "A7_M8") (pintype "passive"))
      (node (ref "IC82") (pin "M8") (pinfunction "A7_M8") (pintype "passive"))
      (node (ref "R693") (pin "1") (pinfunction "1_1") (pintype "passive"))
    )
    (net (code "13") (name "/SE_DDR4_A8") (class "Default")
      (node (ref "IC61") (pin "R22") (pinfunction "D1_MA08_R22") (pintype "passive"))
      (node (ref "IC75") (pin "M2") (pinfunction "A8_M2") (pintype "passive"))
      (node (ref "IC76") (pin "M2") (pinfunction "A8_M2") (pintype "passive"))
      (node (ref "IC77") (pin "M2") (pinfunction "A8_M2") (pintype "passive"))
      (node (ref "IC78") (pin "M2") (pinfunction "A8_M2") (pintype "passive"))
      (node (ref "IC79") (pin "M2") (pinfunction "A8_M2") (pintype "passive"))
      (node (ref "IC80") (pin "M2") (pinfunction "A8_M2") (pintype "passive"))
      (node (ref "IC81") (pin "M2") (pinfunction "A8_M2") (pintype "passive"))
      (node (ref "IC82") (pin "M2") (pinfunction "A8_M2") (pintype "passive"))
      (node (ref "R694") (pin "1") (pinfunction "1_1") (pintype "passive"))
    )
    (net (code "14") (name "/SE_DDR4_A9") (class "Default")
      (node (ref "IC61") (pin "W22") (pinfunction "D1_MA09_W22") (pintype "passive"))
      (node (ref "IC75") (pin "M7") (pinfunction "A9_M7") (pintype "passive"))
      (node (ref "IC76") (pin "M7") (pinfunction "A9_M7") (pintype "passive"))
      (node (ref "IC77") (pin "M7") (pinfunction "A9_M7") (pintype "passive"))
      (node (ref "IC78") (pin "M7") (pinfunction "A9_M7") (pintype "passive"))
      (node (ref "IC79") (pin "M7") (pinfunction "A9_M7") (pintype "passive"))
      (node (ref "IC80") (pin "M7") (pinfunction "A9_M7") (pintype "passive"))
      (node (ref "IC81") (pin "M7") (pinfunction "A9_M7") (pintype "passive"))
      (node (ref "IC82") (pin "M7") (pinfunction "A9_M7") (pintype "passive"))
      (node (ref "R695") (pin "1") (pinfunction "1_1") (pintype "passive"))
    )
    (net (code "15") (name "/SE_DDR4_A10") (class "Default")
      (node (ref "IC61") (pin "AB23") (pinfunction "D1_MA10_AB23") (pintype "passive"))
      (node (ref "IC75") (pin "J3") (pinfunction "A10/AP_J3") (pintype "passive"))
      (node (ref "IC76") (pin "J3") (pinfunction "A10/AP_J3") (pintype "passive"))
      (node (ref "IC77") (pin "J3") (pinfunction "A10/AP_J3") (pintype "passive"))
      (node (ref "IC78") (pin "J3") (pinfunction "A10/AP_J3") (pintype "passive"))
      (node (ref "IC79") (pin "J3") (pinfunction "A10/AP_J3") (pintype "passive"))
      (node (ref "IC80") (pin "J3") (pinfunction "A10/AP_J3") (pintype "passive"))
      (node (ref "IC81") (pin "J3") (pinfunction "A10/AP_J3") (pintype "passive"))
      (node (ref "IC82") (pin "J3") (pinfunction "A10/AP_J3") (pintype "passive"))
      (node (ref "R696") (pin "1") (pinfunction "1_1") (pintype "passive"))
    )
    (net (code "16") (name "/SE_DDR4_A11") (class "Default")
      (node (ref "IC61") (pin "T23") (pinfunction "D1_MA11_T23") (pintype "passive"))
      (node (ref "IC75") (pin "N2") (pinfunction "A11_N2") (pintype "passive"))
      (node (ref "IC76") (pin "N2") (pinfunction "A11_N2") (pintype "passive"))
      (node (ref "IC77") (pin "N2") (pinfunction "A11_N2") (pintype "passive"))
      (node (ref "IC78") (pin "N2") (pinfunction "A11_N2") (pintype "passive"))
      (node (ref "IC79") (pin "N2") (pinfunction "A11_N2") (pintype "passive"))
      (node (ref "IC80") (pin "N2") (pinfunction "A11_N2") (pintype "passive"))
      (node (ref "IC81") (pin "N2") (pinfunction "A11_N2") (pintype "passive"))
      (node (ref "IC82") (pin "N2") (pinfunction "A11_N2") (pintype "passive"))
      (node (ref "R697") (pin "1") (pinfunction "1_1") (pintype "passive"))
    )
    (net (code "17") (name "/SE_DDR4_A12") (class "Default")
      (node (ref "IC61") (pin "AC23") (pinfunction "D1_MA12_AC23") (pintype "passive"))
      (node (ref "IC75") (pin "J7") (pinfunction "A12/~{BC}_J7") (pintype "passive"))
      (node (ref "IC76") (pin "J7") (pinfunction "A12/~{BC}_J7") (pintype "passive"))
      (node (ref "IC77") (pin "J7") (pinfunction "A12/~{BC}_J7") (pintype "passive"))
      (node (ref "IC78") (pin "J7") (pinfunction "A12/~{BC}_J7") (pintype "passive"))
      (node (ref "IC79") (pin "J7") (pinfunction "A12/~{BC}_J7") (pintype "passive"))
      (node (ref "IC80") (pin "J7") (pinfunction "A12/~{BC}_J7") (pintype "passive"))
      (node (ref "IC81") (pin "J7") (pinfunction "A12/~{BC}_J7") (pintype "passive"))
      (node (ref "IC82") (pin "J7") (pinfunction "A12/~{BC}_J7") (pintype "passive"))
      (node (ref "R698") (pin "1") (pinfunction "1_1") (pintype "passive"))
    )
    (net (code "18") (name "/SE_DDR4_A13") (class "Default")
      (node (ref "IC61") (pin "T25") (pinfunction "D1_MA13_T25") (pintype "passive"))
      (node (ref "IC75") (pin "N8") (pinfunction "A13_N8") (pintype "passive"))
      (node (ref "IC76") (pin "N8") (pinfunction "A13_N8") (pintype "passive"))
      (node (ref "IC77") (pin "N8") (pinfunction "A13_N8") (pintype "passive"))
      (node (ref "IC78") (pin "N8") (pinfunction "A13_N8") (pintype "passive"))
      (node (ref "IC79") (pin "N8") (pinfunction "A13_N8") (pintype "passive"))
      (node (ref "IC80") (pin "N8") (pinfunction "A13_N8") (pintype "passive"))
      (node (ref "IC81") (pin "N8") (pinfunction "A13_N8") (pintype "passive"))
      (node (ref "IC82") (pin "N8") (pinfunction "A13_N8") (pintype "passive"))
      (node (ref "R699") (pin "1") (pinfunction "1_1") (pintype "passive"))
    )
    (net (code "19") (name "/SE_DDR4_A14") (class "Default")
      (node (ref "IC61") (pin "AE22") (pinfunction "D1_MA14_AE22") (pintype "passive"))
      (node (ref "IC75") (pin "J8") (pinfunction "BG1_J8") (pintype "passive"))
      (node (ref "IC76") (pin "J8") (pinfunction "BG1_J8") (pintype "passive"))
      (node (ref "IC77") (pin "J8") (pinfunction "BG1_J8") (pintype "passive"))
      (node (ref "IC78") (pin "J8") (pinfunction "BG1_J8") (pintype "passive"))
      (node (ref "IC79") (pin "J8") (pinfunction "BG1_J8") (pintype "passive"))
      (node (ref "IC80") (pin "J8") (pinfunction "BG1_J8") (pintype "passive"))
      (node (ref "IC81") (pin "J8") (pinfunction "BG1_J8") (pintype "passive"))
      (node (ref "IC82") (pin "J8") (pinfunction "BG1_J8") (pintype "passive"))
      (node (ref "R700") (pin "1") (pinfunction "1_1") (pintype "passive"))
    )
    (net (code "20") (name "/SE_DDR4_A15") (class "Default")
      (node (ref "IC61") (pin "U21") (pinfunction "D1_MA15_U21") (pintype "passive"))
      (node (ref "IC75") (pin "H3") (pinfunction "~{ACT}_H3") (pintype "passive"))
      (node (ref "IC76") (pin "H3") (pinfunction "~{ACT}_H3") (pintype "passive"))
      (node (ref "IC77") (pin "H3") (pinfunction "~{ACT}_H3") (pintype "passive"))
      (node (ref "IC78") (pin "H3") (pinfunction "~{ACT}_H3") (pintype "passive"))
      (node (ref "IC79") (pin "H3") (pinfunction "~{ACT}_H3") (pintype "passive"))
      (node (ref "IC80") (pin "H3") (pinfunction "~{ACT}_H3") (pintype "passive"))
      (node (ref "IC81") (pin "H3") (pinfunction "~{ACT}_H3") (pintype "passive"))
      (node (ref "IC82") (pin "H3") (pinfunction "~{ACT}_H3") (pintype "passive"))
      (node (ref "R701") (pin "1") (pinfunction "1_1") (pintype "passive"))
    )
    (net (code "21") (name "/SE_DDR4_ARAS_B") (class "Default")
      (node (ref "IC61") (pin "AB25") (pinfunction "D1_MRAS#_AB25") (pintype "passive"))
    )
    (net (code "22") (name "/SE_DDR4_BA0") (class "Default")
      (node (ref "IC61") (pin "AC21") (pinfunction "D1_MBA0_AC21") (pintype "passive"))
      (node (ref "IC75") (pin "K2") (pinfunction "BA0_K2") (pintype "passive"))
      (node (ref "IC76") (pin "K2") (pinfunction "BA0_K2") (pintype "passive"))
      (node (ref "IC77") (pin "K2") (pinfunction "BA0_K2") (pintype "passive"))
      (node (ref "IC78") (pin "K2") (pinfunction "BA0_K2") (pintype "passive"))
      (node (ref "IC79") (pin "K2") (pinfunction "BA0_K2") (pintype "passive"))
      (node (ref "IC80") (pin "K2") (pinfunction "BA0_K2") (pintype "passive"))
      (node (ref "IC81") (pin "K2") (pinfunction "BA0_K2") (pintype "passive"))
      (node (ref "IC82") (pin "K2") (pinfunction "BA0_K2") (pintype "passive"))
      (node (ref "R683") (pin "1") (pinfunction "1_1") (pintype "passive"))
    )
    (net (code "23") (name "/SE_DDR4_BA1") (class "Default")
      (node (ref "IC61") (pin "Y23") (pinfunction "D1_MBA1_Y23") (pintype "passive"))
      (node (ref "IC75") (pin "K8") (pinfunction "BA1_K8") (pintype "passive"))
      (node (ref "IC76") (pin "K8") (pinfunction "BA1_K8") (pintype "passive"))
      (node (ref "IC77") (pin "K8") (pinfunction "BA1_K8") (pintype "passive"))
      (node (ref "IC78") (pin "K8") (pinfunction "BA1_K8") (pintype "passive"))
      (node (ref "IC79") (pin "K8") (pinfunction "BA1_K8") (pintype "passive"))
      (node (ref "IC80") (pin "K8") (pinfunction "BA1_K8") (pintype "passive"))
      (node (ref "IC81") (pin "K8") (pinfunction "BA1_K8") (pintype "passive"))
      (node (ref "IC82") (pin "K8") (pinfunction "BA1_K8") (pintype "passive"))
      (node (ref "R684") (pin "1") (pinfunction "1_1") (pintype "passive"))
    )
    (net (code "24") (name "/SE_DDR4_BA2") (class "Default")
      (node (ref "IC75") (pin "J2") (pinfunction "BG0_J2") (pintype "passive"))
      (node (ref "IC76") (pin "J2") (pinfunction "BG0_J2") (pintype "passive"))
      (node (ref "IC77") (pin "J2") (pinfunction "BG0_J2") (pintype "passive"))
      (node (ref "IC78") (pin "J2") (pinfunction "BG0_J2") (pintype "passive"))
      (node (ref "IC79") (pin "J2") (pinfunction "BG0_J2") (pintype "passive"))
      (node (ref "IC80") (pin "J2") (pinfunction "BG0_J2") (pintype "passive"))
      (node (ref "IC81") (pin "J2") (pinfunction "BG0_J2") (pintype "passive"))
      (node (ref "IC82") (pin "J2") (pinfunction "BG0_J2") (pintype "passive"))
      (node (ref "R685") (pin "1") (pinfunction "1_1") (pintype "passive"))
    )
    (net (code "26") (name "/SE_DDR4_CAS_B") (class "Default")
      (node (ref "IC61") (pin "AC22") (pinfunction "D1_MCAS#_AC22") (pintype "passive"))
      (node (ref "IC75") (pin "H7") (pinfunction "~{CAS}/A15_H7") (pintype "passive"))
      (node (ref "IC76") (pin "H7") (pinfunction "~{CAS}/A15_H7") (pintype "passive"))
      (node (ref "IC77") (pin "H7") (pinfunction "~{CAS}/A15_H7") (pintype "passive"))
      (node (ref "IC78") (pin "H7") (pinfunction "~{CAS}/A15_H7") (pintype "passive"))
      (node (ref "IC79") (pin "H7") (pinfunction "~{CAS}/A15_H7") (pintype "passive"))
      (node (ref "IC80") (pin "H7") (pinfunction "~{CAS}/A15_H7") (pintype "passive"))
      (node (ref "IC81") (pin "H7") (pinfunction "~{CAS}/A15_H7") (pintype "passive"))
      (node (ref "IC82") (pin "H7") (pinfunction "~{CAS}/A15_H7") (pintype "passive"))
      (node (ref "R703") (pin "1") (pinfunction "1_1") (pintype "passive"))
    )
    (net (code "27") (name "/SE_DDR4_CKE0") (class "Default")
      (node (ref "IC61") (pin "W21") (pinfunction "D1_MCKE0_W21") (pintype "passive"))
      (node (ref "IC75") (pin "G3") (pinfunction "CKE_G3") (pintype "passive"))
      (node (ref "IC76") (pin "G3") (pinfunction "CKE_G3") (pintype "passive"))
      (node (ref "IC77") (pin "G3") (pinfunction "CKE_G3") (pintype "passive"))
      (node (ref "IC78") (pin "G3") (pinfunction "CKE_G3") (pintype "passive"))
      (node (ref "IC79") (pin "G3") (pinfunction "CKE_G3") (pintype "passive"))
      (node (ref "IC80") (pin "G3") (pinfunction "CKE_G3") (pintype "passive"))
      (node (ref "IC81") (pin "G3") (pinfunction "CKE_G3") (pintype "passive"))
      (node (ref "IC82") (pin "G3") (pinfunction "CKE_G3") (pintype "passive"))
      (node (ref "R706") (pin "1") (pinfunction "1_1") (pintype "passive"))
    )
    (net (code "28") (name "/SE_DDR4_CKE1") (class "Default")
      (node (ref "IC61") (pin "AB21") (pinfunction "D1_MCKE1_AB21") (pintype "passive"))
      (node (ref "IC75") (pin "G2") (pinfunction "C0/CKE1_G2") (pintype "passive"))
      (node (ref "IC76") (pin "G2") (pinfunction "C0/CKE1_G2") (pintype "passive"))
      (node (ref "IC77") (pin "G2") (pinfunction "C0/CKE1_G2") (pintype "passive"))
      (node (ref "IC78") (pin "G2") (pinfunction "C0/CKE1_G2") (pintype "passive"))
      (node (ref "IC79") (pin "G2") (pinfunction "C0/CKE1_G2") (pintype "passive"))
      (node (ref "IC80") (pin "G2") (pinfunction "C0/CKE1_G2") (pintype "passive"))
      (node (ref "IC81") (pin "G2") (pinfunction "C0/CKE1_G2") (pintype "passive"))
      (node (ref "IC82") (pin "G2") (pinfunction "C0/CKE1_G2") (pintype "passive"))
      (node (ref "R709") (pin "1") (pinfunction "1_1") (pintype "passive"))
    )
    (net (code "29") (name "/SE_DDR4_CLK") (class "Default")
      (node (ref "IC61") (pin "AA24") (pinfunction "D1_MCK0_AA24") (pintype "passive"))
      (node (ref "IC75") (pin "F7") (pinfunction "CK_T_F7") (pintype "passive"))
      (node (ref "IC76") (pin "F7") (pinfunction "CK_T_F7") (pintype "passive"))
      (node (ref "IC77") (pin "F7") (pinfunction "CK_T_F7") (pintype "passive"))
      (node (ref "IC78") (pin "F7") (pinfunction "CK_T_F7") (pintype "passive"))
      (node (ref "IC79") (pin "F7") (pinfunction "CK_T_F7") (pintype "passive"))
      (node (ref "IC80") (pin "F7") (pinfunction "CK_T_F7") (pintype "passive"))
      (node (ref "IC81") (pin "F7") (pinfunction "CK_T_F7") (pintype "passive"))
      (node (ref "IC82") (pin "F7") (pinfunction "CK_T_F7") (pintype "passive"))
    )
    (net (code "30") (name "/SE_DDR4_CLK_B") (class "Default")
      (node (ref "IC61") (pin "AA25") (pinfunction "D1_MCK0#_AA25") (pintype "passive"))
      (node (ref "IC75") (pin "F8") (pinfunction "CK_C_F8") (pintype "passive"))
      (node (ref "IC76") (pin "F8") (pinfunction "CK_C_F8") (pintype "passive"))
      (node (ref "IC77") (pin "F8") (pinfunction "CK_C_F8") (pintype "passive"))
      (node (ref "IC78") (pin "F8") (pinfunction "CK_C_F8") (pintype "passive"))
      (node (ref "IC79") (pin "F8") (pinfunction "CK_C_F8") (pintype "passive"))
      (node (ref "IC80") (pin "F8") (pinfunction "CK_C_F8") (pintype "passive"))
      (node (ref "IC81") (pin "F8") (pinfunction "CK_C_F8") (pintype "passive"))
      (node (ref "IC82") (pin "F8") (pinfunction "CK_C_F8") (pintype "passive"))
    )
    (net (code "31") (name "/SE_DDR4_CS0_B") (class "Default")
      (node (ref "IC61") (pin "U23") (pinfunction "D1_MCS0#_U23") (pintype "passive"))
      (node (ref "IC75") (pin "G7") (pinfunction "~{CS}_G7") (pintype "passive"))
      (node (ref "IC76") (pin "G7") (pinfunction "~{CS}_G7") (pintype "passive"))
      (node (ref "IC77") (pin "G7") (pinfunction "~{CS}_G7") (pintype "passive"))
      (node (ref "IC78") (pin "G7") (pinfunction "~{CS}_G7") (pintype "passive"))
      (node (ref "IC79") (pin "G7") (pinfunction "~{CS}_G7") (pintype "passive"))
      (node (ref "IC80") (pin "G7") (pinfunction "~{CS}_G7") (pintype "passive"))
      (node (ref "IC81") (pin "G7") (pinfunction "~{CS}_G7") (pintype "passive"))
      (node (ref "IC82") (pin "G7") (pinfunction "~{CS}_G7") (pintype "passive"))
      (node (ref "R705") (pin "1") (pinfunction "1_1") (pintype "passive"))
    )
    (net (code "32") (name "/SE_DDR4_CS1_B") (class "Default")
      (node (ref "IC61") (pin "V21") (pinfunction "D1_MCS1#_V21") (pintype "passive"))
      (node (ref "IC75") (pin "G8") (pinfunction "C1/~{CS1}_G8") (pintype "passive"))
      (node (ref "IC76") (pin "G8") (pinfunction "C1/~{CS1}_G8") (pintype "passive"))
      (node (ref "IC77") (pin "G8") (pinfunction "C1/~{CS1}_G8") (pintype "passive"))
      (node (ref "IC78") (pin "G8") (pinfunction "C1/~{CS1}_G8") (pintype "passive"))
      (node (ref "IC79") (pin "G8") (pinfunction "C1/~{CS1}_G8") (pintype "passive"))
      (node (ref "IC80") (pin "G8") (pinfunction "C1/~{CS1}_G8") (pintype "passive"))
      (node (ref "IC81") (pin "G8") (pinfunction "C1/~{CS1}_G8") (pintype "passive"))
      (node (ref "IC82") (pin "G8") (pinfunction "C1/~{CS1}_G8") (pintype "passive"))
      (node (ref "R708") (pin "1") (pinfunction "1_1") (pintype "passive"))
    )
    (net (code "33") (name "/SE_DDR4_DM0_B") (class "Default")
      (node (ref "IC75") (pin "A7") (pinfunction "NF/~{DM}/~{DBI}/TDQS_T_A7") (pintype "passive"))
      (node (ref "IC76") (pin "A7") (pinfunction "NF/~{DM}/~{DBI}/TDQS_T_A7") (pintype "passive"))
      (node (ref "IC77") (pin "A7") (pinfunction "NF/~{DM}/~{DBI}/TDQS_T_A7") (pintype "passive"))
      (node (ref "IC78") (pin "A7") (pinfunction "NF/~{DM}/~{DBI}/TDQS_T_A7") (pintype "passive"))
      (node (ref "IC79") (pin "A7") (pinfunction "NF/~{DM}/~{DBI}/TDQS_T_A7") (pintype "passive"))
      (node (ref "IC80") (pin "A7") (pinfunction "NF/~{DM}/~{DBI}/TDQS_T_A7") (pintype "passive"))
      (node (ref "IC81") (pin "A7") (pinfunction "NF/~{DM}/~{DBI}/TDQS_T_A7") (pintype "passive"))
      (node (ref "IC82") (pin "A7") (pinfunction "NF/~{DM}/~{DBI}/TDQS_T_A7") (pintype "passive"))
    )
    (net (code "37") (name "/SE_DDR4_DM8_B") (class "Default")
      (node (ref "IC61") (pin "B22") (pinfunction "D1_MDM8_B22") (pintype "passive"))
    )
    (net (code "38") (name "/SE_DDR4_DQ0") (class "Default")
      (node (ref "IC61") (pin "N24") (pinfunction "D1_MDQ02_N24") (pintype "passive"))
      (node (ref "IC75") (pin "C2") (pinfunction "DQ0_C2") (pintype "passive"))
      (node (ref "IC76") (pin "C2") (pinfunction "DQ0_C2") (pintype "passive"))
      (node (ref "IC77") (pin "C2") (pinfunction "DQ0_C2") (pintype "passive"))
      (node (ref "IC78") (pin "C2") (pinfunction "DQ0_C2") (pintype "passive"))
      (node (ref "IC79") (pin "C2") (pinfunction "DQ0_C2") (pintype "passive"))
      (node (ref "IC80") (pin "C2") (pinfunction "DQ0_C2") (pintype "passive"))
      (node (ref "IC81") (pin "C2") (pinfunction "DQ0_C2") (pintype "passive"))
      (node (ref "IC82") (pin "C2") (pinfunction "DQ0_C2") (pintype "passive"))
    )
    (net (code "39") (name "/SE_DDR4_DQ1") (class "Default")
      (node (ref "IC61") (pin "K24") (pinfunction "D1_MDQ01_K24") (pintype "passive"))
      (node (ref "IC75") (pin "B7") (pinfunction "DQ1_B7") (pintype "passive"))
      (node (ref "IC76") (pin "B7") (pinfunction "DQ1_B7") (pintype "passive"))
      (node (ref "IC77") (pin "B7") (pinfunction "DQ1_B7") (pintype "passive"))
      (node (ref "IC78") (pin "B7") (pinfunction "DQ1_B7") (pintype "passive"))
      (node (ref "IC79") (pin "B7") (pinfunction "DQ1_B7") (pintype "passive"))
      (node (ref "IC80") (pin "B7") (pinfunction "DQ1_B7") (pintype "passive"))
      (node (ref "IC81") (pin "B7") (pinfunction "DQ1_B7") (pintype "passive"))
      (node (ref "IC82") (pin "B7") (pinfunction "DQ1_B7") (pintype "passive"))
    )
    (net (code "40") (name "/SE_DDR4_DQ2") (class "Default")
      (node (ref "IC61") (pin "R24") (pinfunction "D1_MDQ03_R24") (pintype "passive"))
      (node (ref "IC75") (pin "D3") (pinfunction "DQ2_D3") (pintype "passive"))
      (node (ref "IC76") (pin "D3") (pinfunction "DQ2_D3") (pintype "passive"))
      (node (ref "IC77") (pin "D3") (pinfunction "DQ2_D3") (pintype "passive"))
      (node (ref "IC78") (pin "D3") (pinfunction "DQ2_D3") (pintype "passive"))
      (node (ref "IC79") (pin "D3") (pinfunction "DQ2_D3") (pintype "passive"))
      (node (ref "IC80") (pin "D3") (pinfunction "DQ2_D3") (pintype "passive"))
      (node (ref "IC81") (pin "D3") (pinfunction "DQ2_D3") (pintype "passive"))
      (node (ref "IC82") (pin "D3") (pinfunction "DQ2_D3") (pintype "passive"))
    )
    (net (code "41") (name "/SE_DDR4_DQ3") (class "Default")
      (node (ref "IC61") (pin "J25") (pinfunction "D1_MDQ00_J25") (pintype "passive"))
      (node (ref "IC75") (pin "D7") (pinfunction "DQ3_D7") (pintype "passive"))
      (node (ref "IC76") (pin "D7") (pinfunction "DQ3_D7") (pintype "passive"))
      (node (ref "IC77") (pin "D7") (pinfunction "DQ3_D7") (pintype "passive"))
      (node (ref "IC78") (pin "D7") (pinfunction "DQ3_D7") (pintype "passive"))
      (node (ref "IC79") (pin "D7") (pinfunction "DQ3_D7") (pintype "passive"))
      (node (ref "IC80") (pin "D7") (pinfunction "DQ3_D7") (pintype "passive"))
      (node (ref "IC81") (pin "D7") (pinfunction "DQ3_D7") (pintype "passive"))
      (node (ref "IC82") (pin "D7") (pinfunction "DQ3_D7") (pintype "passive"))
    )
    (net (code "42") (name "/SE_DDR4_DQ4") (class "Default")
      (node (ref "IC61") (pin "P25") (pinfunction "D1_MDQ07_P25") (pintype "passive"))
      (node (ref "IC75") (pin "D2") (pinfunction "DQ4/NC_D2") (pintype "passive"))
      (node (ref "IC76") (pin "D2") (pinfunction "DQ4/NC_D2") (pintype "passive"))
      (node (ref "IC77") (pin "D2") (pinfunction "DQ4/NC_D2") (pintype "passive"))
      (node (ref "IC78") (pin "D2") (pinfunction "DQ4/NC_D2") (pintype "passive"))
      (node (ref "IC79") (pin "D2") (pinfunction "DQ4/NC_D2") (pintype "passive"))
      (node (ref "IC80") (pin "D2") (pinfunction "DQ4/NC_D2") (pintype "passive"))
      (node (ref "IC81") (pin "D2") (pinfunction "DQ4/NC_D2") (pintype "passive"))
      (node (ref "IC82") (pin "D2") (pinfunction "DQ4/NC_D2") (pintype "passive"))
    )
    (net (code "43") (name "/SE_DDR4_DQ5") (class "Default")
      (node (ref "IC61") (pin "K25") (pinfunction "D1_MDQ05_K25") (pintype "passive"))
      (node (ref "IC75") (pin "D8") (pinfunction "DQ5/NC_D8") (pintype "passive"))
      (node (ref "IC76") (pin "D8") (pinfunction "DQ5/NC_D8") (pintype "passive"))
      (node (ref "IC77") (pin "D8") (pinfunction "DQ5/NC_D8") (pintype "passive"))
      (node (ref "IC78") (pin "D8") (pinfunction "DQ5/NC_D8") (pintype "passive"))
      (node (ref "IC79") (pin "D8") (pinfunction "DQ5/NC_D8") (pintype "passive"))
      (node (ref "IC80") (pin "D8") (pinfunction "DQ5/NC_D8") (pintype "passive"))
      (node (ref "IC81") (pin "D8") (pinfunction "DQ5/NC_D8") (pintype "passive"))
      (node (ref "IC82") (pin "D8") (pinfunction "DQ5/NC_D8") (pintype "passive"))
    )
    (net (code "44") (name "/SE_DDR4_DQ6") (class "Default")
      (node (ref "IC61") (pin "N25") (pinfunction "D1_MDQ06_N25") (pintype "passive"))
      (node (ref "IC75") (pin "E3") (pinfunction "DQ6/NC_E3") (pintype "passive"))
      (node (ref "IC76") (pin "E3") (pinfunction "DQ6/NC_E3") (pintype "passive"))
      (node (ref "IC77") (pin "E3") (pinfunction "DQ6/NC_E3") (pintype "passive"))
      (node (ref "IC78") (pin "E3") (pinfunction "DQ6/NC_E3") (pintype "passive"))
      (node (ref "IC79") (pin "E3") (pinfunction "DQ6/NC_E3") (pintype "passive"))
      (node (ref "IC80") (pin "E3") (pinfunction "DQ6/NC_E3") (pintype "passive"))
      (node (ref "IC81") (pin "E3") (pinfunction "DQ6/NC_E3") (pintype "passive"))
      (node (ref "IC82") (pin "E3") (pinfunction "DQ6/NC_E3") (pintype "passive"))
    )
    (net (code "45") (name "/SE_DDR4_DQ7") (class "Default")
      (node (ref "IC61") (pin "H24") (pinfunction "D1_MDQ04_H24") (pintype "passive"))
      (node (ref "IC75") (pin "E7") (pinfunction "DQ7/NC_E7") (pintype "passive"))
      (node (ref "IC76") (pin "E7") (pinfunction "DQ7/NC_E7") (pintype "passive"))
      (node (ref "IC77") (pin "E7") (pinfunction "DQ7/NC_E7") (pintype "passive"))
      (node (ref "IC78") (pin "E7") (pinfunction "DQ7/NC_E7") (pintype "passive"))
      (node (ref "IC79") (pin "E7") (pinfunction "DQ7/NC_E7") (pintype "passive"))
      (node (ref "IC80") (pin "E7") (pinfunction "DQ7/NC_E7") (pintype "passive"))
      (node (ref "IC81") (pin "E7") (pinfunction "DQ7/NC_E7") (pintype "passive"))
      (node (ref "IC82") (pin "E7") (pinfunction "DQ7/NC_E7") (pintype "passive"))
    )
    (net (code "46") (name "/SE_DDR4_DQ8") (class "Default")
      (node (ref "IC61") (pin "N21") (pinfunction "D1_MDQ10_N21") (pintype "passive"))
    )
    (net (code "47") (name "/SE_DDR4_DQ9") (class "Default")
      (node (ref "IC61") (pin "M23") (pinfunction "D1_MDQ09_M23") (pintype "passive"))
    )
    (net (code "48") (name "/SE_DDR4_DQ10") (class "Default")
      (node (ref "IC61") (pin "P21") (pinfunction "D1_MDQ11_P21") (pintype "passive"))
    )
    (net (code "49") (name "/SE_DDR4_DQ11") (class "Default")
      (node (ref "IC61") (pin "L23") (pinfunction "D1_MDQ08_L23") (pintype "passive"))
    )
    (net (code "50") (name "/SE_DDR4_DQ12") (class "Default")
      (node (ref "IC61") (pin "M21") (pinfunction "D1_MDQ14_M21") (pintype "passive"))
    )
    (net (code "51") (name "/SE_DDR4_DQ13") (class "Default")
      (node (ref "IC61") (pin "L22") (pinfunction "D1_MDQ13_L22") (pintype "passive"))
    )
    (net (code "52") (name "/SE_DDR4_DQ14") (class "Default")
      (node (ref "IC61") (pin "P23") (pinfunction "D1_MDQ15_P23") (pintype "passive"))
    )
    (net (code "53") (name "/SE_DDR4_DQ15") (class "Default")
      (node (ref "IC61") (pin "K21") (pinfunction "D1_MDQ12_K21") (pintype "passive"))
    )
    (net (code "54") (name "/SE_DDR4_DQ16") (class "Default")
      (node (ref "IC61") (pin "F24") (pinfunction "D1_MDQ18_F24") (pintype "passive"))
    )
    (net (code "55") (name "/SE_DDR4_DQ17") (class "Default")
      (node (ref "IC61") (pin "C25") (pinfunction "D1_MDQ17_C25") (pintype "passive"))
    )
    (net (code "56") (name "/SE_DDR4_DQ18") (class "Default")
      (node (ref "IC61") (pin "H25") (pinfunction "D1_MDQ19_H25") (pintype "passive"))
    )
    (net (code "57") (name "/SE_DDR4_DQ19") (class "Default")
      (node (ref "IC61") (pin "C24") (pinfunction "D1_MDQ16_C24") (pintype "passive"))
    )
    (net (code "58") (name "/SE_DDR4_DQ20") (class "Default")
      (node (ref "IC61") (pin "G25") (pinfunction "D1_MDQ23_G25") (pintype "passive"))
    )
    (net (code "60") (name "/SE_DDR4_DQ22") (class "Default")
      (node (ref "IC61") (pin "F25") (pinfunction "D1_MDQ22_F25") (pintype "passive"))
    )
    (net (code "62") (name "/SE_DDR4_DQ24") (class "Default")
      (node (ref "IC61") (pin "K23") (pinfunction "D1_MDQ27_K23") (pintype "passive"))
    )
    (net (code "63") (name "/SE_DDR4_DQ25") (class "Default")
      (node (ref "IC61") (pin "H21") (pinfunction "D1_MDQ25_H21") (pintype "passive"))
    )
    (net (code "64") (name "/SE_DDR4_DQ26") (class "Default")
      (node (ref "IC61") (pin "J23") (pinfunction "D1_MDQ26_J23") (pintype "passive"))
    )
    (net (code "65") (name "/SE_DDR4_DQ27") (class "Default")
      (node (ref "IC61") (pin "F22") (pinfunction "D1_MDQ24_F22") (pintype "passive"))
    )
    (net (code "66") (name "/SE_DDR4_DQ28") (class "Default")
      (node (ref "IC61") (pin "J22") (pinfunction "D1_MDQ31_J22") (pintype "passive"))
    )
    (net (code "67") (name "/SE_DDR4_DQ29") (class "Default")
      (node (ref "IC61") (pin "F23") (pinfunction "D1_MDQ29_F23") (pintype "passive"))
    )
    (net (code "68") (name "/SE_DDR4_DQ30") (class "Default")
      (node (ref "IC61") (pin "J21") (pinfunction "D1_MDQ30_J21") (pintype "passive"))
    )
    (net (code "69") (name "/SE_DDR4_DQ31") (class "Default")
      (node (ref "IC61") (pin "G21") (pinfunction "D1_MDQ28_G21") (pintype "passive"))
    )
    (net (code "70") (name "/SE_DDR4_DQS0") (class "Default")
      (node (ref "IC61") (pin "M24") (pinfunction "D1_MDQS0_M24") (pintype "passive"))
      (node (ref "IC75") (pin "C3") (pinfunction "DQS_T_C3") (pintype "passive"))
      (node (ref "IC76") (pin "C3") (pinfunction "DQS_T_C3") (pintype "passive"))
      (node (ref "IC77") (pin "C3") (pinfunction "DQS_T_C3") (pintype "passive"))
      (node (ref "IC78") (pin "C3") (pinfunction "DQS_T_C3") (pintype "passive"))
      (node (ref "IC79") (pin "C3") (pinfunction "DQS_T_C3") (pintype "passive"))
      (node (ref "IC80") (pin "C3") (pinfunction "DQS_T_C3") (pintype "passive"))
      (node (ref "IC81") (pin "C3") (pinfunction "DQS_T_C3") (pintype "passive"))
      (node (ref "IC82") (pin "C3") (pinfunction "DQS_T_C3") (pintype "passive"))
    )
    (net (code "71") (name "/SE_DDR4_DQS0_B") (class "Default")
      (node (ref "IC75") (pin "B3") (pinfunction "DQS_S_B3") (pintype "passive"))
      (node (ref "IC76") (pin "B3") (pinfunction "DQS_S_B3") (pintype "passive"))
      (node (ref "IC77") (pin "B3") (pinfunction "DQS_S_B3") (pintype "passive"))
      (node (ref "IC78") (pin "B3") (pinfunction "DQS_S_B3") (pintype "passive"))
      (node (ref "IC79") (pin "B3") (pinfunction "DQS_S_B3") (pintype "passive"))
      (node (ref "IC80") (pin "B3") (pinfunction "DQS_S_B3") (pintype "passive"))
      (node (ref "IC81") (pin "B3") (pinfunction "DQS_S_B3") (pintype "passive"))
      (node (ref "IC82") (pin "B3") (pinfunction "DQS_S_B3") (pintype "passive"))
    )
    (net (code "72") (name "/SE_DDR4_DQS1") (class "Default")
      (node (ref "IC61") (pin "N22") (pinfunction "D1_MDQS1_N22") (pintype "passive"))
    )
    (net (code "73") (name "/SE_DDR4_DQS1_B") (class "Default")
      (node (ref "IC61") (pin "N23") (pinfunction "D1_MDQS1#_N23") (pintype "passive"))
    )
    (net (code "75") (name "/SE_DDR4_DQS2_B") (class "Default")
      (node (ref "IC61") (pin "D25") (pinfunction "D1_MDQS2#_D25") (pintype "passive"))
    )
    (net (code "76") (name "/SE_DDR4_DQS3") (class "Default")
      (node (ref "IC61") (pin "H23") (pinfunction "D1_MDQS3_H23") (pintype "passive"))
    )
    (net (code "77") (name "/SE_DDR4_DQS3_B") (class "Default")
      (node (ref "IC61") (pin "H22") (pinfunction "D1_MDQS3#_H22") (pintype "passive"))
    )
    (net (code "78") (name "/SE_DDR4_DQS8") (class "Default")
      (node (ref "IC61") (pin "B23") (pinfunction "D1_MDQS8_B23") (pintype "passive"))
    )
    (net (code "79") (name "/SE_DDR4_DQS8_B") (class "Default")
      (node (ref "IC61") (pin "A23") (pinfunction "D1_MDQS8#_A23") (pintype "passive"))
    )
    (net (code "80") (name "/SE_DDR4_MECC0") (class "Default")
      (node (ref "IC61") (pin "C22") (pinfunction "D1_MECC0_C22") (pintype "passive"))
    )
    (net (code "81") (name "/SE_DDR4_MECC1") (class "Default")
      (node (ref "IC61") (pin "A22") (pinfunction "D1_MECC1_A22") (pintype "passive"))
    )
    (net (code "82") (name "/SE_DDR4_MECC2") (class "Default")
      (node (ref "IC61") (pin "D22") (pinfunction "D1_MECC2_D22") (pintype "passive"))
    )
    (net (code "83") (name "/SE_DDR4_MECC3") (class "Default")
      (node (ref "IC61") (pin "D23") (pinfunction "D1_MECC3_D23") (pintype "passive"))
    )
    (net (code "84") (name "/SE_DDR4_OD1") (class "Default")
      (node (ref "IC61") (pin "T21") (pinfunction "D1_MODT1_T21") (pintype "passive"))
    )
    (net (code "85") (name "/SE_DDR4_ODT0") (class "Default")
      (node (ref "IC61") (pin "U22") (pinfunction "D1_MODT0_U22") (pintype "passive"))
      (node (ref "IC75") (pin "F3") (pinfunction "ODT_F3") (pintype "passive"))
      (node (ref "IC76") (pin "F3") (pinfunction "ODT_F3") (pintype "passive"))
      (node (ref "IC77") (pin "F3") (pinfunction "ODT_F3") (pintype "passive"))
      (node (ref "IC78") (pin "F3") (pinfunction "ODT_F3") (pintype "passive"))
      (node (ref "IC79") (pin "F3") (pinfunction "ODT_F3") (pintype "passive"))
      (node (ref "IC80") (pin "F3") (pinfunction "ODT_F3") (pintype "passive"))
      (node (ref "IC81") (pin "F3") (pinfunction "ODT_F3") (pintype "passive"))
      (node (ref "IC82") (pin "F3") (pinfunction "ODT_F3") (pintype "passive"))
      (node (ref "R707") (pin "1") (pinfunction "1_1") (pintype "passive"))
    )
    (net (code "86") (name "/SE_DDR4_ODT1") (class "Default")
      (node (ref "IC75") (pin "F2") (pinfunction "ODT1_F2") (pintype "passive"))
      (node (ref "IC76") (pin "F2") (pinfunction "ODT1_F2") (pintype "passive"))
      (node (ref "IC77") (pin "F2") (pinfunction "ODT1_F2") (pintype "passive"))
      (node (ref "IC78") (pin "F2") (pinfunction "ODT1_F2") (pintype "passive"))
      (node (ref "IC79") (pin "F2") (pinfunction "ODT1_F2") (pintype "passive"))
      (node (ref "IC80") (pin "F2") (pinfunction "ODT1_F2") (pintype "passive"))
      (node (ref "IC81") (pin "F2") (pinfunction "ODT1_F2") (pintype "passive"))
      (node (ref "IC82") (pin "F2") (pinfunction "ODT1_F2") (pintype "passive"))
      (node (ref "R710") (pin "1") (pinfunction "1_1") (pintype "passive"))
    )
    (net (code "87") (name "/SE_DDR4_PAR") (class "Default")
      (node (ref "IC61") (pin "U25") (pinfunction "D1_MAPAR_OUT_U25") (pintype "passive"))
      (node (ref "IC75") (pin "N3") (pinfunction "PAR_N3") (pintype "passive"))
      (node (ref "IC76") (pin "N3") (pinfunction "PAR_N3") (pintype "passive"))
      (node (ref "IC77") (pin "N3") (pinfunction "PAR_N3") (pintype "passive"))
      (node (ref "IC78") (pin "N3") (pinfunction "PAR_N3") (pintype "passive"))
      (node (ref "IC79") (pin "N3") (pinfunction "PAR_N3") (pintype "passive"))
      (node (ref "IC80") (pin "N3") (pinfunction "PAR_N3") (pintype "passive"))
      (node (ref "IC81") (pin "N3") (pinfunction "PAR_N3") (pintype "passive"))
      (node (ref "IC82") (pin "N3") (pinfunction "PAR_N3") (pintype "passive"))
      (node (ref "R711") (pin "1") (pinfunction "1_1") (pintype "passive"))
    )
    (net (code "88") (name "/SE_DDR4_RAS_B") (class "Default")
      (node (ref "IC75") (pin "H8") (pinfunction "~{RAS}/A16/NC_H8") (pintype "passive"))
      (node (ref "IC76") (pin "H8") (pinfunction "~{RAS}/A16/NC_H8") (pintype "passive"))
      (node (ref "IC77") (pin "H8") (pinfunction "~{RAS}/A16/NC_H8") (pintype "passive"))
      (node (ref "IC78") (pin "H8") (pinfunction "~{RAS}/A16/NC_H8") (pintype "passive"))
      (node (ref "IC79") (pin "H8") (pinfunction "~{RAS}/A16/NC_H8") (pintype "passive"))
      (node (ref "IC80") (pin "H8") (pinfunction "~{RAS}/A16/NC_H8") (pintype "passive"))
      (node (ref "IC81") (pin "H8") (pinfunction "~{RAS}/A16/NC_H8") (pintype "passive"))
      (node (ref "IC82") (pin "H8") (pinfunction "~{RAS}/A16/NC_H8") (pintype "passive"))
      (node (ref "R702") (pin "1") (pinfunction "1_1") (pintype "passive"))
    )
    (net (code "89") (name "/SE_DDR4_RST_B") (class "Default")
      (node (ref "IC75") (pin "L1") (pinfunction "~{RESET}_L1") (pintype "passive"))
      (node (ref "IC76") (pin "L1") (pinfunction "~{RESET}_L1") (pintype "passive"))
      (node (ref "IC77") (pin "L1") (pinfunction "~{RESET}_L1") (pintype "passive"))
      (node (ref "IC78") (pin "L1") (pinfunction "~{RESET}_L1") (pintype "passive"))
      (node (ref "IC79") (pin "L1") (pinfunction "~{RESET}_L1") (pintype "passive"))
      (node (ref "IC80") (pin "L1") (pinfunction "~{RESET}_L1") (pintype "passive"))
      (node (ref "IC81") (pin "L1") (pinfunction "~{RESET}_L1") (pintype "passive"))
      (node (ref "IC82") (pin "L1") (pinfunction "~{RESET}_L1") (pintype "passive"))
    )
    (net (code "90") (name "/SE_DDR4_TEN") (class "Default")
      (node (ref "IC75") (pin "G9") (pinfunction "RUF/TEN_G9") (pintype "passive"))
      (node (ref "IC76") (pin "G9") (pinfunction "RUF/TEN_G9") (pintype "passive"))
      (node (ref "IC77") (pin "G9") (pinfunction "RUF/TEN_G9") (pintype "passive"))
      (node (ref "IC78") (pin "G9") (pinfunction "RUF/TEN_G9") (pintype "passive"))
      (node (ref "IC79") (pin "G9") (pinfunction "RUF/TEN_G9") (pintype "passive"))
      (node (ref "IC80") (pin "G9") (pinfunction "RUF/TEN_G9") (pintype "passive"))
      (node (ref "IC81") (pin "G9") (pinfunction "RUF/TEN_G9") (pintype "passive"))
      (node (ref "IC82") (pin "G9") (pinfunction "RUF/TEN_G9") (pintype "passive"))
      (node (ref "R677") (pin "1") (pinfunction "1_1") (pintype "passive"))
    )
    (net (code "91") (name "/SE_DDR4_WE_B") (class "Default")
      (node (ref "IC75") (pin "H2") (pinfunction "~{WE}/A14_H2") (pintype "passive"))
      (node (ref "IC76") (pin "H2") (pinfunction "~{WE}/A14_H2") (pintype "passive"))
      (node (ref "IC77") (pin "H2") (pinfunction "~{WE}/A14_H2") (pintype "passive"))
      (node (ref "IC78") (pin "H2") (pinfunction "~{WE}/A14_H2") (pintype "passive"))
      (node (ref "IC79") (pin "H2") (pinfunction "~{WE}/A14_H2") (pintype "passive"))
      (node (ref "IC80") (pin "H2") (pinfunction "~{WE}/A14_H2") (pintype "passive"))
      (node (ref "IC81") (pin "H2") (pinfunction "~{WE}/A14_H2") (pintype "passive"))
      (node (ref "IC82") (pin "H2") (pinfunction "~{WE}/A14_H2") (pintype "passive"))
      (node (ref "R704") (pin "1") (pinfunction "1_1") (pintype "passive"))
    )
    (net (code "92") (name "/SE_DDR4_ZQ_0") (class "Default")
      (node (ref "IC75") (pin "B9") (pinfunction "ZQ_B9") (pintype "passive"))
      (node (ref "IC76") (pin "B9") (pinfunction "ZQ_B9") (pintype "passive"))
      (node (ref "IC77") (pin "B9") (pinfunction "ZQ_B9") (pintype "passive"))
      (node (ref "IC78") (pin "B9") (pinfunction "ZQ_B9") (pintype "passive"))
      (node (ref "IC79") (pin "B9") (pinfunction "ZQ_B9") (pintype "passive"))
      (node (ref "IC80") (pin "B9") (pinfunction "ZQ_B9") (pintype "passive"))
      (node (ref "IC81") (pin "B9") (pinfunction "ZQ_B9") (pintype "passive"))
      (node (ref "IC82") (pin "B9") (pinfunction "ZQ_B9") (pintype "passive"))
      (node (ref "R667") (pin "2") (pinfunction "2_2") (pintype "passive"))
      (node (ref "R668") (pin "2") (pinfunction "2_2") (pintype "passive"))
      (node (ref "R669") (pin "2") (pinfunction "2_2") (pintype "passive"))
      (node (ref "R670") (pin "2") (pinfunction "2_2") (pintype "passive"))
      (node (ref "R678") (pin "2") (pinfunction "2_2") (pintype "passive"))
      (node (ref "R679") (pin "2") (pinfunction "2_2") (pintype "passive"))
      (node (ref "R680") (pin "2") (pinfunction "2_2") (pintype "passive"))
      (node (ref "R681") (pin "2") (pinfunction "2_2") (pintype "passive"))
    )
    (net (code "93") (name "/SE_DDR_RST_B") (class "Default")
      (node (ref "R676") (pin "2") (pinfunction "2_2") (pintype "passive"))
    )
    (net (code "94") (name "/SE_I2C1_SCL") (class "Default")
      (node (ref "IC83") (pin "6") (pinfunction "SCL_6") (pintype "passive"))
    )
    (net (code "95") (name "/SE_I2C1_SDA") (class "Default")
      (node (ref "IC83") (pin "5") (pinfunction "SDA_5") (pintype "passive"))
    )
    (net (code "96") (name "DDR_VREF") (class "Default")
      (node (ref "C1120") (pin "2") (pinfunction "2_2") (pintype "passive"))
      (node (ref "C1121") (pin "2") (pinfunction "2_2") (pintype "passive"))
      (node (ref "C1122") (pin "2") (pinfunction "2_2") (pintype "passive"))
      (node (ref "C1123") (pin "2") (pinfunction "2_2") (pintype "passive"))
      (node (ref "C1124") (pin "2") (pinfunction "2_2") (pintype "passive"))
      (node (ref "C1125") (pin "2") (pinfunction "2_2") (pintype "passive"))
      (node (ref "C1126") (pin "2") (pinfunction "2_2") (pintype "passive"))
      (node (ref "C1127") (pin "2") (pinfunction "2_2") (pintype "passive"))
      (node (ref "C1137") (pin "2") (pinfunction "2_2") (pintype "passive"))
      (node (ref "C1138") (pin "2") (pinfunction "2_2") (pintype "passive"))
      (node (ref "C1139") (pin "2") (pinfunction "2_2") (pintype "passive"))
      (node (ref "C1140") (pin "2") (pinfunction "2_2") (pintype "passive"))
      (node (ref "C1141") (pin "2") (pinfunction "2_2") (pintype "passive"))
      (node (ref "C1142") (pin "2") (pinfunction "2_2") (pintype "passive"))
      (node (ref "C1143") (pin "2") (pinfunction "2_2") (pintype "passive"))
      (node (ref "C1144") (pin "2") (pinfunction "2_2") (pintype "passive"))
      (node (ref "IC75") (pin "J1") (pinfunction "VREFCA_J1") (pintype "passive"))
      (node (ref "IC76") (pin "J1") (pinfunction "VREFCA_J1") (pintype "passive"))
      (node (ref "IC77") (pin "J1") (pinfunction "VREFCA_J1") (pintype "passive"))
      (node (ref "IC78") (pin "J1") (pinfunction "VREFCA_J1") (pintype "passive"))
      (node (ref "IC79") (pin "J1") (pinfunction "VREFCA_J1") (pintype "passive"))
      (node (ref "IC80") (pin "J1") (pinfunction "VREFCA_J1") (pintype "passive"))
      (node (ref "IC81") (pin "J1") (pinfunction "VREFCA_J1") (pintype "passive"))
      (node (ref "IC82") (pin "J1") (pinfunction "VREFCA_J1") (pintype "passive"))
    )
    (net (code "97") (name "DDR_VTT") (class "Default")
      (node (ref "C1185") (pin "2") (pinfunction "2_2") (pintype "passive"))
      (node (ref "C1186") (pin "2") (pinfunction "2_2") (pintype "passive"))
      (node (ref "C1187") (pin "2") (pinfunction "2_2") (pintype "passive"))
      (node (ref "C1188") (pin "2") (pinfunction "2_2") (pintype "passive"))
      (node (ref "C1189") (pin "2") (pinfunction "2_2") (pintype "passive"))
      (node (ref "C1190") (pin "2") (pinfunction "2_2") (pintype "passive"))
      (node (ref "C1211") (pin "2") (pinfunction "2_2") (pintype "passive"))
      (node (ref "C1212") (pin "2") (pinfunction "2_2") (pintype "passive"))
      (node (ref "C1213") (pin "2") (pinfunction "2_2") (pintype "passive"))
      (node (ref "C1214") (pin "2") (pinfunction "2_2") (pintype "passive"))
      (node (ref "C1215") (pin "2") (pinfunction "2_2") (pintype "passive"))
      (node (ref "C1216") (pin "2") (pinfunction "2_2") (pintype "passive"))
      (node (ref "C1237") (pin "2") (pinfunction "2_2") (pintype "passive"))
      (node (ref "C1238") (pin "2") (pinfunction "2_2") (pintype "passive"))
      (node (ref "C1239") (pin "2") (pinfunction "2_2") (pintype "passive"))
      (node (ref "C1240") (pin "2") (pinfunction "2_2") (pintype "passive"))
      (node (ref "C1241") (pin "1") (pinfunction "1_1") (pintype "passive"))
      (node (ref "C1242") (pin "1") (pinfunction "1_1") (pintype "passive"))
      (node (ref "R683") (pin "2") (pinfunction "2_2") (pintype "passive"))
      (node (ref "R684") (pin "2") (pinfunction "2_2") (pintype "passive"))
      (node (ref "R685") (pin "2") (pinfunction "2_2") (pintype "passive"))
      (node (ref "R686") (pin "2") (pinfunction "2_2") (pintype "passive"))
      (node (ref "R687") (pin "2") (pinfunction "2_2") (pintype "passive"))
      (node (ref "R688") (pin "2") (pinfunction "2_2") (pintype "passive"))
      (node (ref "R689") (pin "2") (pinfunction "2_2") (pintype "passive"))
      (node (ref "R690") (pin "2") (pinfunction "2_2") (pintype "passive"))
      (node (ref "R691") (pin "2") (pinfunction "2_2") (pintype "passive"))
      (node (ref "R692") (pin "2") (pinfunction "2_2") (pintype "passive"))
      (node (ref "R693") (pin "2") (pinfunction "2_2") (pintype "passive"))
      (node (ref "R694") (pin "2") (pinfunction "2_2") (pintype "passive"))
      (node (ref "R695") (pin "2") (pinfunction "2_2") (pintype "passive"))
      (node (ref "R696") (pin "2") (pinfunction "2_2") (pintype "passive"))
      (node (ref "R697") (pin "2") (pinfunction "2_2") (pintype "passive"))
      (node (ref "R698") (pin "2") (pinfunction "2_2") (pintype "passive"))
      (node (ref "R699") (pin "2") (pinfunction "2_2") (pintype "passive"))
      (node (ref "R700") (pin "2") (pinfunction "2_2") (pintype "passive"))
      (node (ref "R701") (pin "2") (pinfunction "2_2") (pintype "passive"))
      (node (ref "R702") (pin "2") (pinfunction "2_2") (pintype "passive"))
      (node (ref "R703") (pin "2") (pinfunction "2_2") (pintype "passive"))
      (node (ref "R704") (pin "2") (pinfunction "2_2") (pintype "passive"))
      (node (ref "R705") (pin "2") (pinfunction "2_2") (pintype "passive"))
      (node (ref "R706") (pin "2") (pinfunction "2_2") (pintype "passive"))
      (node (ref "R707") (pin "2") (pinfunction "2_2") (pintype "passive"))
      (node (ref "R708") (pin "2") (pinfunction "2_2") (pintype "passive"))
      (node (ref "R709") (pin "2") (pinfunction "2_2") (pintype "passive"))
      (node (ref "R710") (pin "2") (pinfunction "2_2") (pintype "passive"))
      (node (ref "R711") (pin "2") (pinfunction "2_2") (pintype "passive"))
    )
    (net (code "98") (name "GND") (class "Default")
      (node (ref "C1112") (pin "2") (pinfunction "2_2") (pintype "passive"))
      (node (ref "C1113") (pin "2") (pinfunction "2_2") (pintype "passive"))
      (node (ref "C1114") (pin "2") (pinfunction "2_2") (pintype "passive"))
      (node (ref "C1115") (pin "2") (pinfunction "2_2") (pintype "passive"))
      (node (ref "C1116") (pin "2") (pinfunction "2_2") (pintype "passive"))
      (node (ref "C1117") (pin "2") (pinfunction "2_2") (pintype "passive"))
      (node (ref "C1118") (pin "2") (pinfunction "2_2") (pintype "passive"))
      (node (ref "C1119") (pin "2") (pinfunction "2_2") (pintype "passive"))
      (node (ref "C1120") (pin "1") (pinfunction "1_1") (pintype "passive"))
      (node (ref "C1121") (pin "1") (pinfunction "1_1") (pintype "passive"))
      (node (ref "C1122") (pin "1") (pinfunction "1_1") (pintype "passive"))
      (node (ref "C1123") (pin "1") (pinfunction "1_1") (pintype "passive"))
      (node (ref "C1124") (pin "1") (pinfunction "1_1") (pintype "passive"))
      (node (ref "C1125") (pin "1") (pinfunction "1_1") (pintype "passive"))
      (node (ref "C1126") (pin "1") (pinfunction "1_1") (pintype "passive"))
      (node (ref "C1127") (pin "1") (pinfunction "1_1") (pintype "passive"))
      (node (ref "C1128") (pin "2") (pinfunction "2_2") (pintype "passive"))
      (node (ref "C1129") (pin "2") (pinfunction "2_2") (pintype "passive"))
      (node (ref "C1130") (pin "2") (pinfunction "2_2") (pintype "passive"))
      (node (ref "C1131") (pin "2") (pinfunction "2_2") (pintype "passive"))
      (node (ref "C1132") (pin "2") (pinfunction "2_2") (pintype "passive"))
      (node (ref "C1133") (pin "2") (pinfunction "2_2") (pintype "passive"))
      (node (ref "C1134") (pin "2") (pinfunction "2_2") (pintype "passive"))
      (node (ref "C1135") (pin "2") (pinfunction "2_2") (pintype "passive"))
      (node (ref "C1136") (pin "2") (pinfunction "2_2") (pintype "passive"))
      (node (ref "C1137") (pin "1") (pinfunction "1_1") (pintype "passive"))
      (node (ref "C1138") (pin "1") (pinfunction "1_1") (pintype "passive"))
      (node (ref "C1139") (pin "1") (pinfunction "1_1") (pintype "passive"))
      (node (ref "C1140") (pin "1") (pinfunction "1_1") (pintype "passive"))
      (node (ref "C1141") (pin "1") (pinfunction "1_1") (pintype "passive"))
      (node (ref "C1142") (pin "1") (pinfunction "1_1") (pintype "passive"))
      (node (ref "C1143") (pin "1") (pinfunction "1_1") (pintype "passive"))
      (node (ref "C1144") (pin "1") (pinfunction "1_1") (pintype "passive"))
      (node (ref "C1145") (pin "1") (pinfunction "1_1") (pintype "passive"))
      (node (ref "C1146") (pin "1") (pinfunction "1_1") (pintype "passive"))
      (node (ref "C1147") (pin "1") (pinfunction "1_1") (pintype "passive"))
      (node (ref "C1148") (pin "1") (pinfunction "1_1") (pintype "passive"))
      (node (ref "C1149") (pin "1") (pinfunction "1_1") (pintype "passive"))
      (node (ref "C1150") (pin "1") (pinfunction "1_1") (pintype "passive"))
      (node (ref "C1151") (pin "1") (pinfunction "1_1") (pintype "passive"))
      (node (ref "C1152") (pin "1") (pinfunction "1_1") (pintype "passive"))
      (node (ref "C1153") (pin "2") (pinfunction "2_2") (pintype "passive"))
      (node (ref "C1154") (pin "2") (pinfunction "2_2") (pintype "passive"))
      (node (ref "C1155") (pin "1") (pinfunction "1_1") (pintype "passive"))
      (node (ref "C1156") (pin "1") (pinfunction "1_1") (pintype "passive"))
      (node (ref "C1157") (pin "1") (pinfunction "1_1") (pintype "passive"))
      (node (ref "C1158") (pin "1") (pinfunction "1_1") (pintype "passive"))
      (node (ref "C1159") (pin "1") (pinfunction "1_1") (pintype "passive"))
      (node (ref "C1160") (pin "1") (pinfunction "1_1") (pintype "passive"))
      (node (ref "C1161") (pin "1") (pinfunction "1_1") (pintype "passive"))
      (node (ref "C1162") (pin "1") (pinfunction "1_1") (pintype "passive"))
      (node (ref "C1163") (pin "2") (pinfunction "2_2") (pintype "passive"))
      (node (ref "C1164") (pin "2") (pinfunction "2_2") (pintype "passive"))
      (node (ref "C1165") (pin "1") (pinfunction "1_1") (pintype "passive"))
      (node (ref "C1166") (pin "1") (pinfunction "1_1") (pintype "passive"))
      (node (ref "C1167") (pin "1") (pinfunction "1_1") (pintype "passive"))
      (node (ref "C1168") (pin "1") (pinfunction "1_1") (pintype "passive"))
      (node (ref "C1169") (pin "1") (pinfunction "1_1") (pintype "passive"))
      (node (ref "C1170") (pin "1") (pinfunction "1_1") (pintype "passive"))
      (node (ref "C1171") (pin "1") (pinfunction "1_1") (pintype "passive"))
      (node (ref "C1172") (pin "1") (pinfunction "1_1") (pintype "passive"))
      (node (ref "C1173") (pin "2") (pinfunction "2_2") (pintype "passive"))
      (node (ref "C1174") (pin "2") (pinfunction "2_2") (pintype "passive"))
      (node (ref "C1175") (pin "1") (pinfunction "1_1") (pintype "passive"))
      (node (ref "C1176") (pin "1") (pinfunction "1_1") (pintype "passive"))
      (node (ref "C1177") (pin "1") (pinfunction "1_1") (pintype "passive"))
      (node (ref "C1178") (pin "1") (pinfunction "1_1") (pintype "passive"))
      (node (ref "C1179") (pin "1") (pinfunction "1_1") (pintype "passive"))
      (node (ref "C1180") (pin "1") (pinfunction "1_1") (pintype "passive"))
      (node (ref "C1181") (pin "1") (pinfunction "1_1") (pintype "passive"))
      (node (ref "C1182") (pin "1") (pinfunction "1_1") (pintype "passive"))
      (node (ref "C1183") (pin "2") (pinfunction "2_2") (pintype "passive"))
      (node (ref "C1184") (pin "2") (pinfunction "2_2") (pintype "passive"))
      (node (ref "C1185") (pin "1") (pinfunction "1_1") (pintype "passive"))
      (node (ref "C1186") (pin "1") (pinfunction "1_1") (pintype "passive"))
      (node (ref "C1187") (pin "1") (pinfunction "1_1") (pintype "passive"))
      (node (ref "C1188") (pin "1") (pinfunction "1_1") (pintype "passive"))
      (node (ref "C1189") (pin "1") (pinfunction "1_1") (pintype "passive"))
      (node (ref "C1190") (pin "1") (pinfunction "1_1") (pintype "passive"))
      (node (ref "C1191") (pin "1") (pinfunction "1_1") (pintype "passive"))
      (node (ref "C1192") (pin "1") (pinfunction "1_1") (pintype "passive"))
      (node (ref "C1193") (pin "1") (pinfunction "1_1") (pintype "passive"))
      (node (ref "C1194") (pin "1") (pinfunction "1_1") (pintype "passive"))
      (node (ref "C1195") (pin "1") (pinfunction "1_1") (pintype "passive"))
      (node (ref "C1196") (pin "1") (pinfunction "1_1") (pintype "passive"))
      (node (ref "C1197") (pin "1") (pinfunction "1_1") (pintype "passive"))
      (node (ref "C1198") (pin "1") (pinfunction "1_1") (pintype "passive"))
      (node (ref "C1199") (pin "2") (pinfunction "2_2") (pintype "passive"))
      (node (ref "C1200") (pin "2") (pinfunction "2_2") (pintype "passive"))
      (node (ref "C1201") (pin "1") (pinfunction "1_1") (pintype "passive"))
      (node (ref "C1202") (pin "1") (pinfunction "1_1") (pintype "passive"))
      (node (ref "C1203") (pin "1") (pinfunction "1_1") (pintype "passive"))
      (node (ref "C1204") (pin "1") (pinfunction "1_1") (pintype "passive"))
      (node (ref "C1205") (pin "1") (pinfunction "1_1") (pintype "passive"))
      (node (ref "C1206") (pin "1") (pinfunction "1_1") (pintype "passive"))
      (node (ref "C1207") (pin "1") (pinfunction "1_1") (pintype "passive"))
      (node (ref "C1208") (pin "1") (pinfunction "1_1") (pintype "passive"))
      (node (ref "C1209") (pin "2") (pinfunction "2_2") (pintype "passive"))
      (node (ref "C1210") (pin "2") (pinfunction "2_2") (pintype "passive"))
      (node (ref "C1211") (pin "1") (pinfunction "1_1") (pintype "passive"))
      (node (ref "C1212") (pin "1") (pinfunction "1_1") (pintype "passive"))
      (node (ref "C1213") (pin "1") (pinfunction "1_1") (pintype "passive"))
      (node (ref "C1214") (pin "1") (pinfunction "1_1") (pintype "passive"))
      (node (ref "C1215") (pin "1") (pinfunction "1_1") (pintype "passive"))
      (node (ref "C1216") (pin "1") (pinfunction "1_1") (pintype "passive"))
      (node (ref "C1217") (pin "1") (pinfunction "1_1") (pintype "passive"))
      (node (ref "C1218") (pin "1") (pinfunction "1_1") (pintype "passive"))
      (node (ref "C1219") (pin "1") (pinfunction "1_1") (pintype "passive"))
      (node (ref "C1220") (pin "1") (pinfunction "1_1") (pintype "passive"))
      (node (ref "C1221") (pin "1") (pinfunction "1_1") (pintype "passive"))
      (node (ref "C1222") (pin "1") (pinfunction "1_1") (pintype "passive"))
      (node (ref "C1223") (pin "1") (pinfunction "1_1") (pintype "passive"))
      (node (ref "C1224") (pin "1") (pinfunction "1_1") (pintype "passive"))
      (node (ref "C1225") (pin "2") (pinfunction "2_2") (pintype "passive"))
      (node (ref "C1226") (pin "2") (pinfunction "2_2") (pintype "passive"))
      (node (ref "C1227") (pin "1") (pinfunction "1_1") (pintype "passive"))
      (node (ref "C1228") (pin "1") (pinfunction "1_1") (pintype "passive"))
      (node (ref "C1229") (pin "1") (pinfunction "1_1") (pintype "passive"))
      (node (ref "C1230") (pin "1") (pinfunction "1_1") (pintype "passive"))
      (node (ref "C1231") (pin "1") (pinfunction "1_1") (pintype "passive"))
      (node (ref "C1232") (pin "1") (pinfunction "1_1") (pintype "passive"))
      (node (ref "C1233") (pin "1") (pinfunction "1_1") (pintype "passive"))
      (node (ref "C1234") (pin "1") (pinfunction "1_1") (pintype "passive"))
      (node (ref "C1235") (pin "2") (pinfunction "2_2") (pintype "passive"))
      (node (ref "C1236") (pin "2") (pinfunction "2_2") (pintype "passive"))
      (node (ref "C1237") (pin "1") (pinfunction "1_1") (pintype "passive"))
      (node (ref "C1238") (pin "1") (pinfunction "1_1") (pintype "passive"))
      (node (ref "C1239") (pin "1") (pinfunction "1_1") (pintype "passive"))
      (node (ref "C1240") (pin "1") (pinfunction "1_1") (pintype "passive"))
      (node (ref "C1241") (pin "2") (pinfunction "2_2") (pintype "passive"))
      (node (ref "C1242") (pin "2") (pinfunction "2_2") (pintype "passive"))
      (node (ref "IC61") (pin "W24") (pinfunction "D1_MCK1_W24") (pintype "passive"))
      (node (ref "IC61") (pin "W25") (pinfunction "D1_MCK1#_W25") (pintype "passive"))
      (node (ref "IC75") (pin "A2") (pinfunction "VSSQ1_A2") (pintype "passive"))
      (node (ref "IC75") (pin "A8") (pinfunction "VSSQ2_A8") (pintype "passive"))
      (node (ref "IC75") (pin "A9") (pinfunction "VSS1_A9") (pintype "passive"))
      (node (ref "IC75") (pin "C8") (pinfunction "VSS2_C8") (pintype "passive"))
      (node (ref "IC75") (pin "D1") (pinfunction "VSSQ3_D1") (pintype "passive"))
      (node (ref "IC75") (pin "D9") (pinfunction "VSSQ4_D9") (pintype "passive"))
      (node (ref "IC75") (pin "E1") (pinfunction "VSS3_E1") (pintype "passive"))
      (node (ref "IC75") (pin "E9") (pinfunction "VSS4_E9") (pintype "passive"))
      (node (ref "IC75") (pin "G1") (pinfunction "VSS5_G1") (pintype "passive"))
      (node (ref "IC75") (pin "H9") (pinfunction "VSS6_H9") (pintype "passive"))
      (node (ref "IC75") (pin "K1") (pinfunction "VSS7_K1") (pintype "passive"))
      (node (ref "IC75") (pin "K9") (pinfunction "VSS8_K9") (pintype "passive"))
      (node (ref "IC75") (pin "N1") (pinfunction "VSS9_N1") (pintype "passive"))
      (node (ref "IC76") (pin "A2") (pinfunction "VSSQ1_A2") (pintype "passive"))
      (node (ref "IC76") (pin "A8") (pinfunction "VSSQ2_A8") (pintype "passive"))
      (node (ref "IC76") (pin "A9") (pinfunction "VSS1_A9") (pintype "passive"))
      (node (ref "IC76") (pin "C8") (pinfunction "VSS2_C8") (pintype "passive"))
      (node (ref "IC76") (pin "D1") (pinfunction "VSSQ3_D1") (pintype "passive"))
      (node (ref "IC76") (pin "D9") (pinfunction "VSSQ4_D9") (pintype "passive"))
      (node (ref "IC76") (pin "E1") (pinfunction "VSS3_E1") (pintype "passive"))
      (node (ref "IC76") (pin "E9") (pinfunction "VSS4_E9") (pintype "passive"))
      (node (ref "IC76") (pin "G1") (pinfunction "VSS5_G1") (pintype "passive"))
      (node (ref "IC76") (pin "H9") (pinfunction "VSS6_H9") (pintype "passive"))
      (node (ref "IC76") (pin "K1") (pinfunction "VSS7_K1") (pintype "passive"))
      (node (ref "IC76") (pin "K9") (pinfunction "VSS8_K9") (pintype "passive"))
      (node (ref "IC76") (pin "N1") (pinfunction "VSS9_N1") (pintype "passive"))
      (node (ref "IC77") (pin "A2") (pinfunction "VSSQ1_A2") (pintype "passive"))
      (node (ref "IC77") (pin "A8") (pinfunction "VSSQ2_A8") (pintype "passive"))
      (node (ref "IC77") (pin "A9") (pinfunction "VSS1_A9") (pintype "passive"))
      (node (ref "IC77") (pin "C8") (pinfunction "VSS2_C8") (pintype "passive"))
      (node (ref "IC77") (pin "D1") (pinfunction "VSSQ3_D1") (pintype "passive"))
      (node (ref "IC77") (pin "D9") (pinfunction "VSSQ4_D9") (pintype "passive"))
      (node (ref "IC77") (pin "E1") (pinfunction "VSS3_E1") (pintype "passive"))
      (node (ref "IC77") (pin "E9") (pinfunction "VSS4_E9") (pintype "passive"))
      (node (ref "IC77") (pin "G1") (pinfunction "VSS5_G1") (pintype "passive"))
      (node (ref "IC77") (pin "H9") (pinfunction "VSS6_H9") (pintype "passive"))
      (node (ref "IC77") (pin "K1") (pinfunction "VSS7_K1") (pintype "passive"))
      (node (ref "IC77") (pin "K9") (pinfunction "VSS8_K9") (pintype "passive"))
      (node (ref "IC77") (pin "N1") (pinfunction "VSS9_N1") (pintype "passive"))
      (node (ref "IC78") (pin "A2") (pinfunction "VSSQ1_A2") (pintype "passive"))
      (node (ref "IC78") (pin "A8") (pinfunction "VSSQ2_A8") (pintype "passive"))
      (node (ref "IC78") (pin "A9") (pinfunction "VSS1_A9") (pintype "passive"))
      (node (ref "IC78") (pin "C8") (pinfunction "VSS2_C8") (pintype "passive"))
      (node (ref "IC78") (pin "D1") (pinfunction "VSSQ3_D1") (pintype "passive"))
      (node (ref "IC78") (pin "D9") (pinfunction "VSSQ4_D9") (pintype "passive"))
      (node (ref "IC78") (pin "E1") (pinfunction "VSS3_E1") (pintype "passive"))
      (node (ref "IC78") (pin "E9") (pinfunction "VSS4_E9") (pintype "passive"))
      (node (ref "IC78") (pin "G1") (pinfunction "VSS5_G1") (pintype "passive"))
      (node (ref "IC78") (pin "H9") (pinfunction "VSS6_H9") (pintype "passive"))
      (node (ref "IC78") (pin "K1") (pinfunction "VSS7_K1") (pintype "passive"))
      (node (ref "IC78") (pin "K9") (pinfunction "VSS8_K9") (pintype "passive"))
      (node (ref "IC78") (pin "N1") (pinfunction "VSS9_N1") (pintype "passive"))
      (node (ref "IC79") (pin "A2") (pinfunction "VSSQ1_A2") (pintype "passive"))
      (node (ref "IC79") (pin "A8") (pinfunction "VSSQ2_A8") (pintype "passive"))
      (node (ref "IC79") (pin "A9") (pinfunction "VSS1_A9") (pintype "passive"))
      (node (ref "IC79") (pin "C8") (pinfunction "VSS2_C8") (pintype "passive"))
      (node (ref "IC79") (pin "D1") (pinfunction "VSSQ3_D1") (pintype "passive"))
      (node (ref "IC79") (pin "D9") (pinfunction "VSSQ4_D9") (pintype "passive"))
      (node (ref "IC79") (pin "E1") (pinfunction "VSS3_E1") (pintype "passive"))
      (node (ref "IC79") (pin "E9") (pinfunction "VSS4_E9") (pintype "passive"))
      (node (ref "IC79") (pin "G1") (pinfunction "VSS5_G1") (pintype "passive"))
      (node (ref "IC79") (pin "H9") (pinfunction "VSS6_H9") (pintype "passive"))
      (node (ref "IC79") (pin "K1") (pinfunction "VSS7_K1") (pintype "passive"))
      (node (ref "IC79") (pin "K9") (pinfunction "VSS8_K9") (pintype "passive"))
      (node (ref "IC79") (pin "N1") (pinfunction "VSS9_N1") (pintype "passive"))
      (node (ref "IC80") (pin "A2") (pinfunction "VSSQ1_A2") (pintype "passive"))
      (node (ref "IC80") (pin "A8") (pinfunction "VSSQ2_A8") (pintype "passive"))
      (node (ref "IC80") (pin "A9") (pinfunction "VSS1_A9") (pintype "passive"))
      (node (ref "IC80") (pin "C8") (pinfunction "VSS2_C8") (pintype "passive"))
      (node (ref "IC80") (pin "D1") (pinfunction "VSSQ3_D1") (pintype "passive"))
      (node (ref "IC80") (pin "D9") (pinfunction "VSSQ4_D9") (pintype "passive"))
      (node (ref "IC80") (pin "E1") (pinfunction "VSS3_E1") (pintype "passive"))
      (node (ref "IC80") (pin "E9") (pinfunction "VSS4_E9") (pintype "passive"))
      (node (ref "IC80") (pin "G1") (pinfunction "VSS5_G1") (pintype "passive"))
      (node (ref "IC80") (pin "H9") (pinfunction "VSS6_H9") (pintype "passive"))
      (node (ref "IC80") (pin "K1") (pinfunction "VSS7_K1") (pintype "passive"))
      (node (ref "IC80") (pin "K9") (pinfunction "VSS8_K9") (pintype "passive"))
      (node (ref "IC80") (pin "N1") (pinfunction "VSS9_N1") (pintype "passive"))
      (node (ref "IC81") (pin "A2") (pinfunction "VSSQ1_A2") (pintype "passive"))
      (node (ref "IC81") (pin "A8") (pinfunction "VSSQ2_A8") (pintype "passive"))
      (node (ref "IC81") (pin "A9") (pinfunction "VSS1_A9") (pintype "passive"))
      (node (ref "IC81") (pin "C8") (pinfunction "VSS2_C8") (pintype "passive"))
      (node (ref "IC81") (pin "D1") (pinfunction "VSSQ3_D1") (pintype "passive"))
      (node (ref "IC81") (pin "D9") (pinfunction "VSSQ4_D9") (pintype "passive"))
      (node (ref "IC81") (pin "E1") (pinfunction "VSS3_E1") (pintype "passive"))
      (node (ref "IC81") (pin "E9") (pinfunction "VSS4_E9") (pintype "passive"))
      (node (ref "IC81") (pin "G1") (pinfunction "VSS5_G1") (pintype "passive"))
      (node (ref "IC81") (pin "H9") (pinfunction "VSS6_H9") (pintype "passive"))
      (node (ref "IC81") (pin "K1") (pinfunction "VSS7_K1") (pintype "passive"))
      (node (ref "IC81") (pin "K9") (pinfunction "VSS8_K9") (pintype "passive"))
      (node (ref "IC81") (pin "N1") (pinfunction "VSS9_N1") (pintype "passive"))
      (node (ref "IC82") (pin "A2") (pinfunction "VSSQ1_A2") (pintype "passive"))
      (node (ref "IC82") (pin "A8") (pinfunction "VSSQ2_A8") (pintype "passive"))
      (node (ref "IC82") (pin "A9") (pinfunction "VSS1_A9") (pintype "passive"))
      (node (ref "IC82") (pin "C8") (pinfunction "VSS2_C8") (pintype "passive"))
      (node (ref "IC82") (pin "D1") (pinfunction "VSSQ3_D1") (pintype "passive"))
      (node (ref "IC82") (pin "D9") (pinfunction "VSSQ4_D9") (pintype "passive"))
      (node (ref "IC82") (pin "E1") (pinfunction "VSS3_E1") (pintype "passive"))
      (node (ref "IC82") (pin "E9") (pinfunction "VSS4_E9") (pintype "passive"))
      (node (ref "IC82") (pin "G1") (pinfunction "VSS5_G1") (pintype "passive"))
      (node (ref "IC82") (pin "H9") (pinfunction "VSS6_H9") (pintype "passive"))
      (node (ref "IC82") (pin "K1") (pinfunction "VSS7_K1") (pintype "passive"))
      (node (ref "IC82") (pin "K9") (pinfunction "VSS8_K9") (pintype "passive"))
      (node (ref "IC82") (pin "N1") (pinfunction "VSS9_N1") (pintype "passive"))
      (node (ref "IC83") (pin "1") (pinfunction "NC_1") (pintype "passive"))
      (node (ref "IC83") (pin "3") (pinfunction "A2_3") (pintype "passive"))
      (node (ref "IC83") (pin "4") (pinfunction "GND_4") (pintype "passive"))
      (node (ref "R667") (pin "1") (pinfunction "1_1") (pintype "passive"))
      (node (ref "R668") (pin "1") (pinfunction "1_1") (pintype "passive"))
      (node (ref "R669") (pin "1") (pinfunction "1_1") (pintype "passive"))
      (node (ref "R670") (pin "1") (pinfunction "1_1") (pintype "passive"))
      (node (ref "R672") (pin "1") (pinfunction "1_1") (pintype "passive"))
      (node (ref "R675") (pin "1") (pinfunction "1_1") (pintype "passive"))
      (node (ref "R677") (pin "2") (pinfunction "2_2") (pintype "passive"))
      (node (ref "R678") (pin "1") (pinfunction "1_1") (pintype "passive"))
      (node (ref "R679") (pin "1") (pinfunction "1_1") (pintype "passive"))
      (node (ref "R680") (pin "1") (pinfunction "1_1") (pintype "passive"))
      (node (ref "R681") (pin "1") (pinfunction "1_1") (pintype "passive"))
      (node (ref "R682") (pin "1") (pinfunction "1_1") (pintype "passive"))
    )
    (net (code "99") (name "Net-(IC61A-D1_MAPAR_ERR#)") (class "Default")
      (node (ref "IC61") (pin "AD24") (pinfunction "D1_MAPAR_ERR#_AD24") (pintype "passive"))
      (node (ref "R673") (pin "1") (pinfunction "1_1") (pintype "passive"))
      (node (ref "R674") (pin "1") (pinfunction "1_1") (pintype "passive"))
    )
    (net (code "100") (name "Net-(IC61A-D1_MDIC0)") (class "Default")
      (node (ref "IC61") (pin "V25") (pinfunction "D1_MDIC0_V25") (pintype "passive"))
      (node (ref "R672") (pin "2") (pinfunction "2_2") (pintype "passive"))
    )
    (net (code "101") (name "Net-(IC61A-D1_MDIC1)") (class "Default")
      (node (ref "IC61") (pin "Y25") (pinfunction "D1_MDIC1_Y25") (pintype "passive"))
      (node (ref "R671") (pin "2") (pinfunction "2_2") (pintype "passive"))
    )
    (net (code "102") (name "Net-(IC83-WP)") (class "Default")
      (node (ref "IC83") (pin "7") (pinfunction "WP_7") (pintype "passive"))
      (node (ref "R682") (pin "2") (pinfunction "2_2") (pintype "passive"))
    )
    (net (code "103") (name "unconnected-(IC61A-D1_MA00-PadAC25)") (class "Default")
      (node (ref "IC61") (pin "AC25") (pinfunction "D1_MA00_AC25") (pintype "passive"))
    )
    (net (code "104") (name "unconnected-(IC61A-D1_MBA2-PadAE23)") (class "Default")
      (node (ref "IC61") (pin "AE23") (pinfunction "D1_MBA2_AE23") (pintype "passive"))
    )
    (net (code "105") (name "unconnected-(IC61A-D1_MCS2#-PadAB20)") (class "Default")
      (node (ref "IC61") (pin "AB20") (pinfunction "D1_MCS2#_AB20") (pintype "passive+no_connect"))
    )
    (net (code "106") (name "unconnected-(IC61A-D1_MCS3#-PadAA22)") (class "Default")
      (node (ref "IC61") (pin "AA22") (pinfunction "D1_MCS3#_AA22") (pintype "passive"))
    )
    (net (code "107") (name "unconnected-(IC61A-D1_MDM0-PadL25)") (class "Default")
      (node (ref "IC61") (pin "L25") (pinfunction "D1_MDM0_L25") (pintype "passive"))
    )
    (net (code "108") (name "unconnected-(IC61A-D1_MDM1-PadL21)") (class "Default")
      (node (ref "IC61") (pin "L21") (pinfunction "D1_MDM1_L21") (pintype "passive"))
    )
    (net (code "109") (name "unconnected-(IC61A-D1_MDM2-PadE23)") (class "Default")
      (node (ref "IC61") (pin "E23") (pinfunction "D1_MDM2_E23") (pintype "passive"))
    )
    (net (code "110") (name "unconnected-(IC61A-D1_MDM4-PadG23)") (class "Default")
      (node (ref "IC61") (pin "G23") (pinfunction "D1_MDM4_G23") (pintype "passive"))
    )
    (net (code "111") (name "unconnected-(IC61A-D1_MDQ20-PadB24)") (class "Default")
      (node (ref "IC61") (pin "B24") (pinfunction "D1_MDQ20_B24") (pintype "passive"))
    )
    (net (code "112") (name "unconnected-(IC61A-D1_MDQ21-PadD24)") (class "Default")
      (node (ref "IC61") (pin "D24") (pinfunction "D1_MDQ21_D24") (pintype "passive"))
    )
    (net (code "113") (name "unconnected-(IC61A-D1_MDQS0#-PadM25)") (class "Default")
      (node (ref "IC61") (pin "M25") (pinfunction "D1_MDQS0#_M25") (pintype "passive"))
    )
    (net (code "114") (name "unconnected-(IC61A-D1_MDQS2-PadE25)") (class "Default")
      (node (ref "IC61") (pin "E25") (pinfunction "D1_MDQS2_E25") (pintype "passive"))
    )
    (net (code "115") (name "unconnected-(IC61A-D1_MVREF-PadH19)") (class "Default")
      (node (ref "IC61") (pin "H19") (pinfunction "D1_MVREF_H19") (pintype "passive"))
    )
    (net (code "116") (name "unconnected-(IC61A-D1_MWE-PadY21)") (class "Default")
      (node (ref "IC61") (pin "Y21") (pinfunction "D1_MWE_Y21") (pintype "passive"))
    )
    (net (code "117") (name "unconnected-(IC61A-D1_TPA-PadD1)") (class "Default")
      (node (ref "IC61") (pin "D1") (pinfunction "D1_TPA_D1") (pintype "passive"))
    )
    (net (code "118") (name "unconnected-(IC75-A17{slash}NC-PadN7)") (class "Default")
      (node (ref "IC75") (pin "N7") (pinfunction "A17/NC_N7") (pintype "passive+no_connect"))
    )
    (net (code "119") (name "unconnected-(IC75-NF{slash}TDQS_C-PadA3)") (class "Default")
      (node (ref "IC75") (pin "A3") (pinfunction "NF/TDQS_C_A3") (pintype "passive+no_connect"))
    )
    (net (code "120") (name "unconnected-(IC76-A17{slash}NC-PadN7)") (class "Default")
      (node (ref "IC76") (pin "N7") (pinfunction "A17/NC_N7") (pintype "passive+no_connect"))
    )
    (net (code "121") (name "unconnected-(IC76-NF{slash}TDQS_C-PadA3)") (class "Default")
      (node (ref "IC76") (pin "A3") (pinfunction "NF/TDQS_C_A3") (pintype "passive+no_connect"))
    )
    (net (code "122") (name "unconnected-(IC77-A17{slash}NC-PadN7)") (class "Default")
      (node (ref "IC77") (pin "N7") (pinfunction "A17/NC_N7") (pintype "passive+no_connect"))
    )
    (net (code "123") (name "unconnected-(IC77-NF{slash}TDQS_C-PadA3)") (class "Default")
      (node (ref "IC77") (pin "A3") (pinfunction "NF/TDQS_C_A3") (pintype "passive+no_connect"))
    )
    (net (code "124") (name "unconnected-(IC78-A17{slash}NC-PadN7)") (class "Default")
      (node (ref "IC78") (pin "N7") (pinfunction "A17/NC_N7") (pintype "passive+no_connect"))
    )
    (net (code "125") (name "unconnected-(IC78-NF{slash}TDQS_C-PadA3)") (class "Default")
      (node (ref "IC78") (pin "A3") (pinfunction "NF/TDQS_C_A3") (pintype "passive+no_connect"))
    )
    (net (code "126") (name "unconnected-(IC79-A17{slash}NC-PadN7)") (class "Default")
      (node (ref "IC79") (pin "N7") (pinfunction "A17/NC_N7") (pintype "passive+no_connect"))
    )
    (net (code "127") (name "unconnected-(IC79-NF{slash}TDQS_C-PadA3)") (class "Default")
      (node (ref "IC79") (pin "A3") (pinfunction "NF/TDQS_C_A3") (pintype "passive+no_connect"))
    )
    (net (code "128") (name "unconnected-(IC80-A17{slash}NC-PadN7)") (class "Default")
      (node (ref "IC80") (pin "N7") (pinfunction "A17/NC_N7") (pintype "passive+no_connect"))
    )
    (net (code "129") (name "unconnected-(IC80-NF{slash}TDQS_C-PadA3)") (class "Default")
      (node (ref "IC80") (pin "A3") (pinfunction "NF/TDQS_C_A3") (pintype "passive+no_connect"))
    )
    (net (code "130") (name "unconnected-(IC81-A17{slash}NC-PadN7)") (class "Default")
      (node (ref "IC81") (pin "N7") (pinfunction "A17/NC_N7") (pintype "passive+no_connect"))
    )
    (net (code "131") (name "unconnected-(IC81-NF{slash}TDQS_C-PadA3)") (class "Default")
      (node (ref "IC81") (pin "A3") (pinfunction "NF/TDQS_C_A3") (pintype "passive+no_connect"))
    )
    (net (code "132") (name "unconnected-(IC82-A17{slash}NC-PadN7)") (class "Default")
      (node (ref "IC82") (pin "N7") (pinfunction "A17/NC_N7") (pintype "passive+no_connect"))
    )
    (net (code "133") (name "unconnected-(IC82-NF{slash}TDQS_C-PadA3)") (class "Default")
      (node (ref "IC82") (pin "A3") (pinfunction "NF/TDQS_C_A3") (pintype "passive+no_connect"))
    )
    (net (code "134") (name "unconnected-(R675-Pad2)") (class "Default")
      (node (ref "R675") (pin "2") (pinfunction "2_2") (pintype "passive"))
    )
  )
)
